# ScreenRGB.net
KiCad netlist of a schematic drawn in Altium Designer
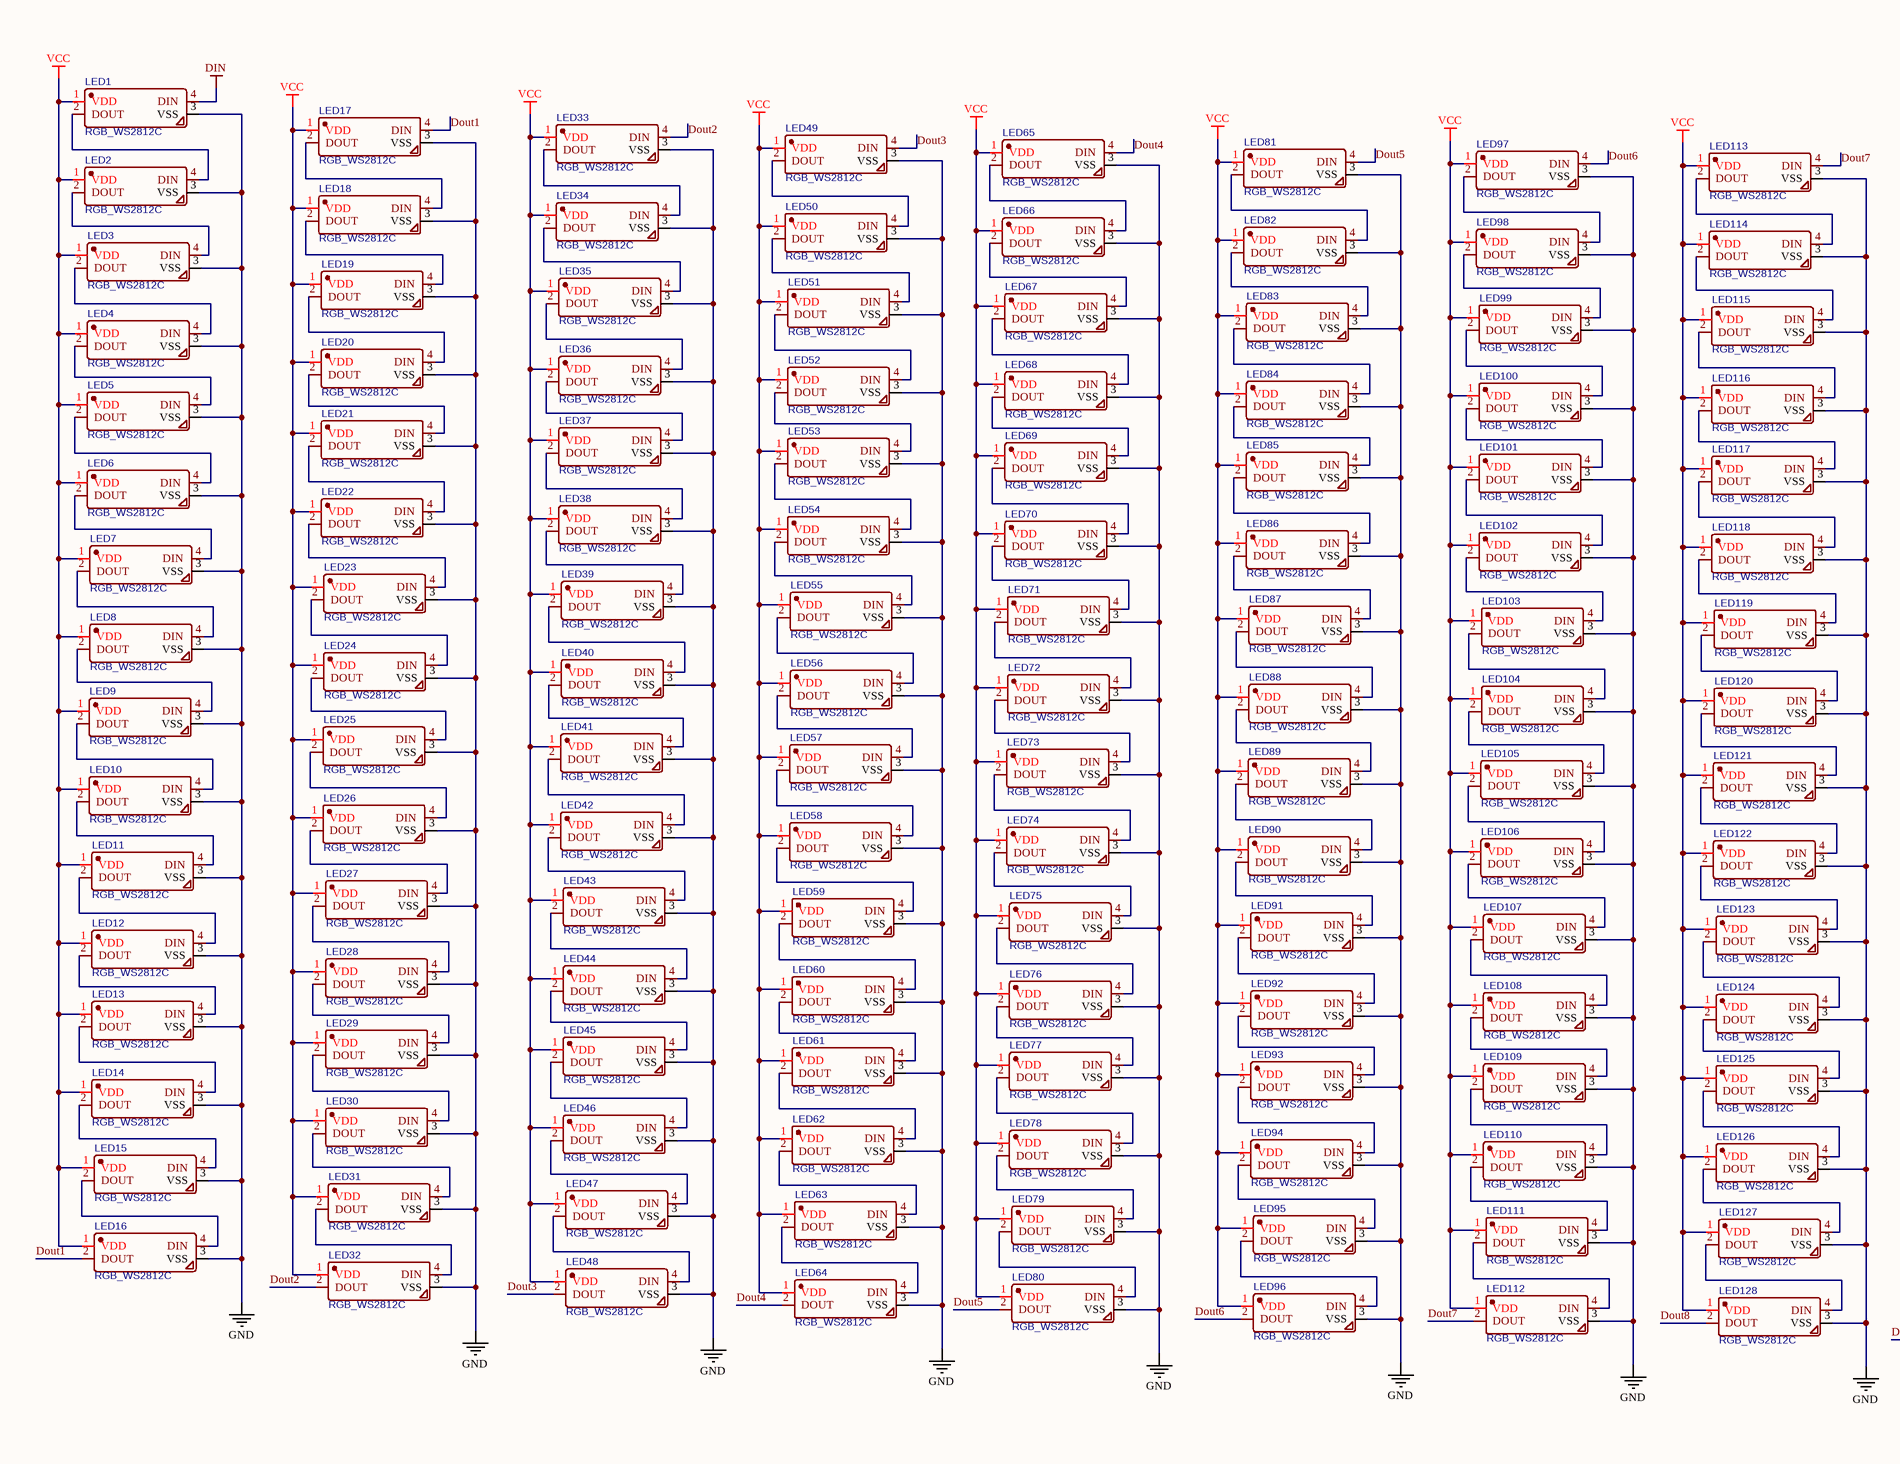
[diagram p0: ScreenRGB.SchDoc, left]
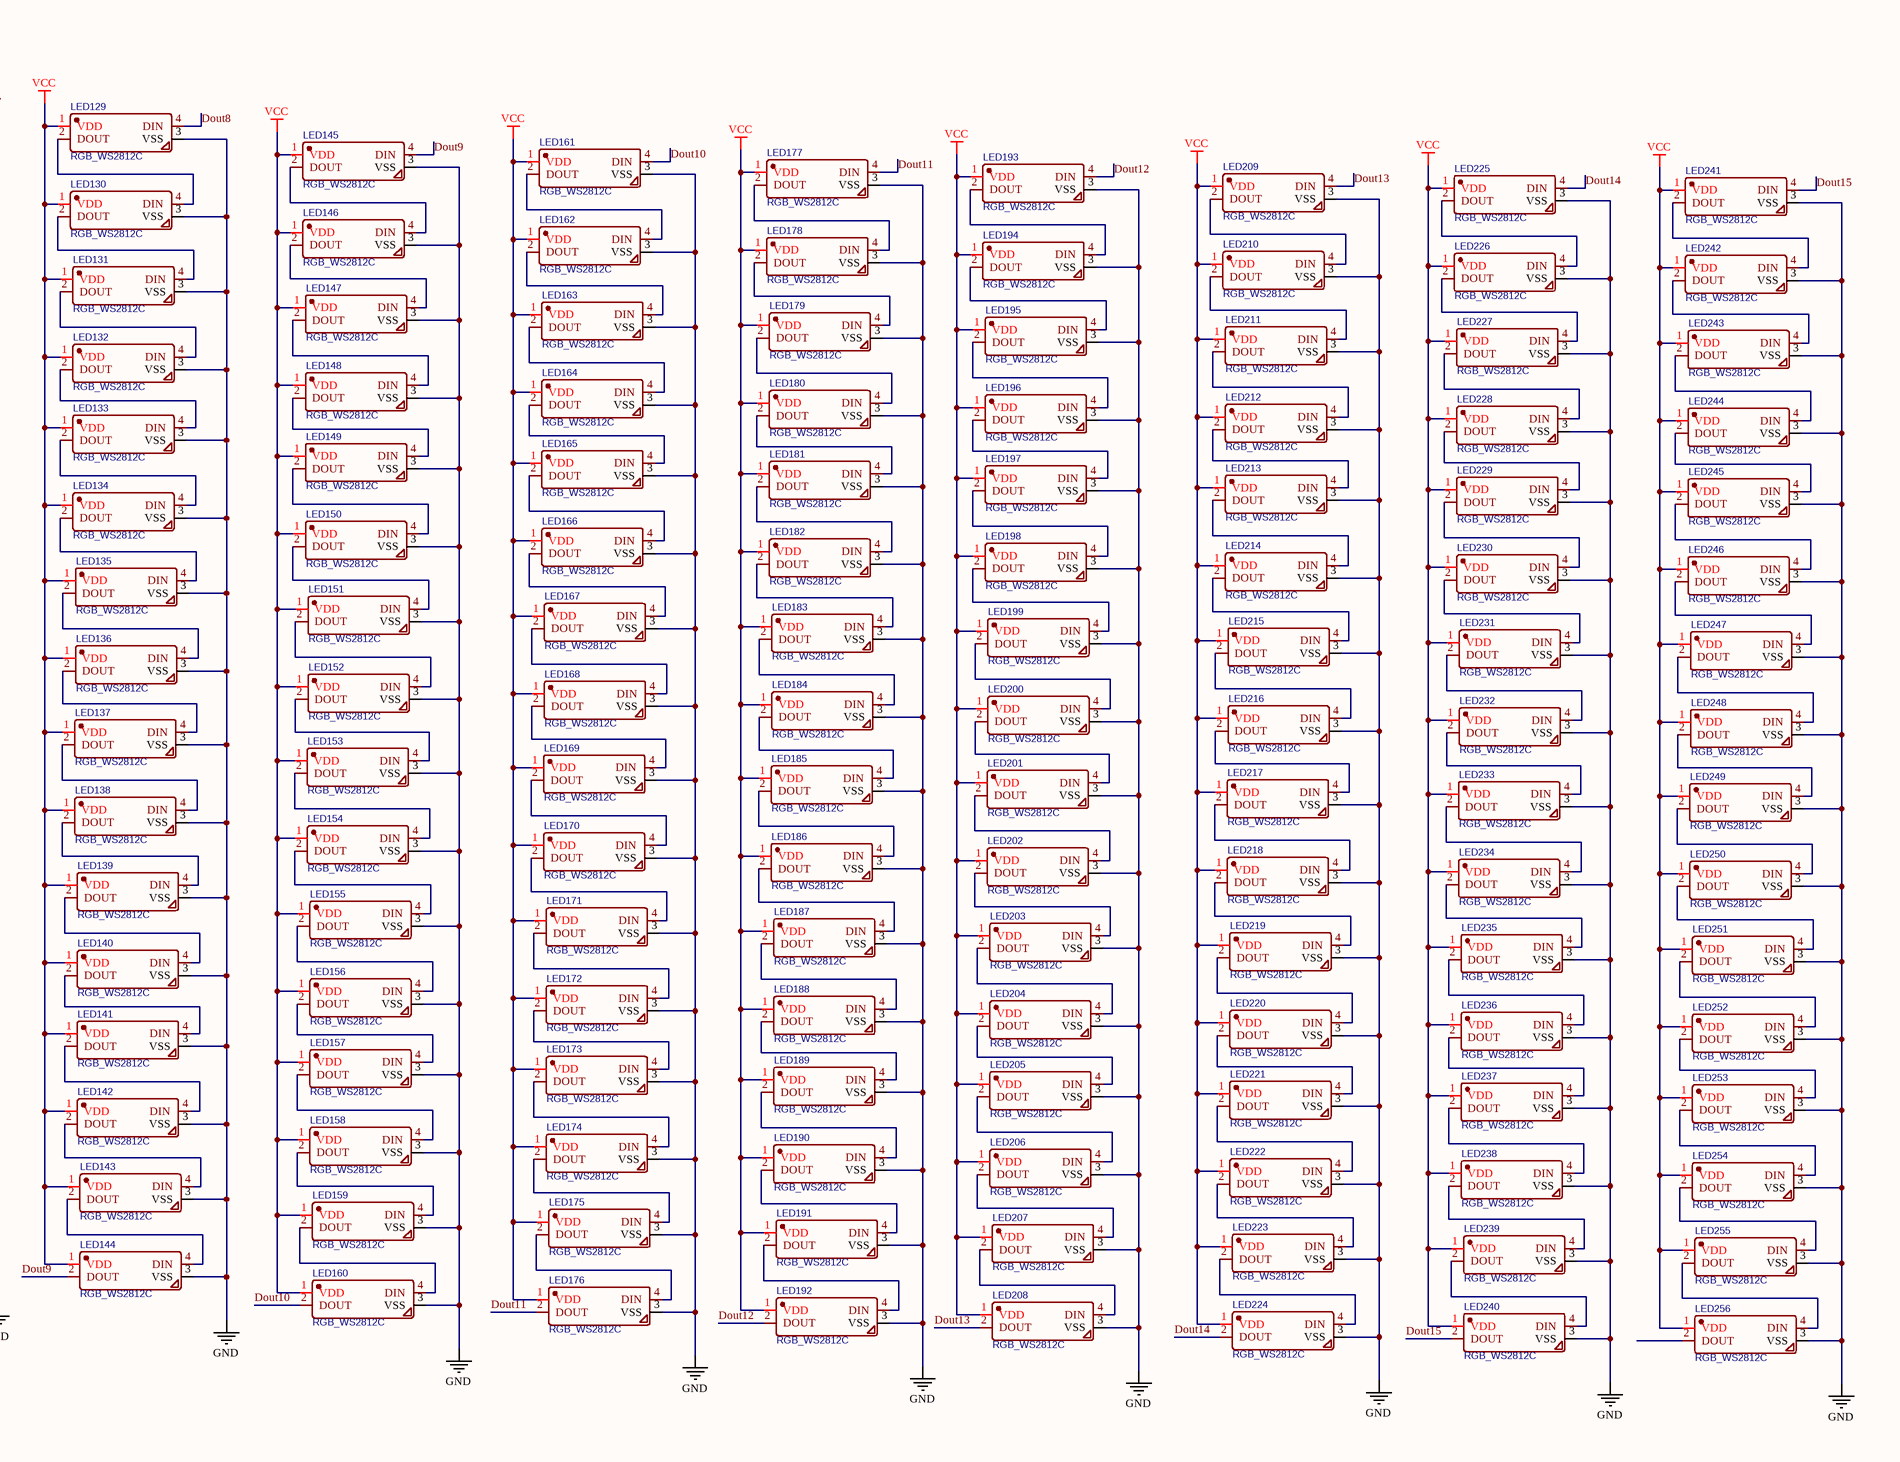
[diagram p1: ScreenRGB.SchDoc, right]

(export (version "E")
  (design (tool "Eeschema 10.0.6"))
  (components
    (comp (ref "LED1")
      (value "RGB_WS2812C")
      (footprint "LED_5050-SMD_4P-WS2812")
      (fields
        (field (name "BOM_MANUFACTURER PART") "WS2812C")
        (field (name "BOM_SUPPLIER PART") "C114587")
        (field (name "CONTRIBUTOR") "LCSC")
      )
      (libsource (lib "LTC_Library1") (part "RGB_WS2812C"))
    )
    (comp (ref "LED2")
      (value "RGB_WS2812C")
      (footprint "LED_5050-SMD_4P-WS2812")
      (fields
        (field (name "BOM_MANUFACTURER PART") "WS2812C")
        (field (name "BOM_SUPPLIER PART") "C114587")
        (field (name "CONTRIBUTOR") "LCSC")
      )
      (libsource (lib "LTC_Library1") (part "RGB_WS2812C"))
    )
    (comp (ref "LED3")
      (value "RGB_WS2812C")
      (footprint "LED_5050-SMD_4P-WS2812")
      (fields
        (field (name "BOM_MANUFACTURER PART") "WS2812C")
        (field (name "BOM_SUPPLIER PART") "C114587")
        (field (name "CONTRIBUTOR") "LCSC")
      )
      (libsource (lib "LTC_Library1") (part "RGB_WS2812C"))
    )
    (comp (ref "LED4")
      (value "RGB_WS2812C")
      (footprint "LED_5050-SMD_4P-WS2812")
      (fields
        (field (name "BOM_MANUFACTURER PART") "WS2812C")
        (field (name "BOM_SUPPLIER PART") "C114587")
        (field (name "CONTRIBUTOR") "LCSC")
      )
      (libsource (lib "LTC_Library1") (part "RGB_WS2812C"))
    )
    (comp (ref "LED5")
      (value "RGB_WS2812C")
      (footprint "LED_5050-SMD_4P-WS2812")
      (fields
        (field (name "BOM_MANUFACTURER PART") "WS2812C")
        (field (name "BOM_SUPPLIER PART") "C114587")
        (field (name "CONTRIBUTOR") "LCSC")
      )
      (libsource (lib "LTC_Library1") (part "RGB_WS2812C"))
    )
    (comp (ref "LED6")
      (value "RGB_WS2812C")
      (footprint "LED_5050-SMD_4P-WS2812")
      (fields
        (field (name "BOM_MANUFACTURER PART") "WS2812C")
        (field (name "BOM_SUPPLIER PART") "C114587")
        (field (name "CONTRIBUTOR") "LCSC")
      )
      (libsource (lib "LTC_Library1") (part "RGB_WS2812C"))
    )
    (comp (ref "LED7")
      (value "RGB_WS2812C")
      (footprint "LED_5050-SMD_4P-WS2812")
      (fields
        (field (name "BOM_MANUFACTURER PART") "WS2812C")
        (field (name "BOM_SUPPLIER PART") "C114587")
        (field (name "CONTRIBUTOR") "LCSC")
      )
      (libsource (lib "LTC_Library1") (part "RGB_WS2812C"))
    )
    (comp (ref "LED8")
      (value "RGB_WS2812C")
      (footprint "LED_5050-SMD_4P-WS2812")
      (fields
        (field (name "BOM_MANUFACTURER PART") "WS2812C")
        (field (name "BOM_SUPPLIER PART") "C114587")
        (field (name "CONTRIBUTOR") "LCSC")
      )
      (libsource (lib "LTC_Library1") (part "RGB_WS2812C"))
    )
    (comp (ref "LED9")
      (value "RGB_WS2812C")
      (footprint "LED_5050-SMD_4P-WS2812")
      (fields
        (field (name "BOM_MANUFACTURER PART") "WS2812C")
        (field (name "BOM_SUPPLIER PART") "C114587")
        (field (name "CONTRIBUTOR") "LCSC")
      )
      (libsource (lib "LTC_Library1") (part "RGB_WS2812C"))
    )
    (comp (ref "LED10")
      (value "RGB_WS2812C")
      (footprint "LED_5050-SMD_4P-WS2812")
      (fields
        (field (name "BOM_MANUFACTURER PART") "WS2812C")
        (field (name "BOM_SUPPLIER PART") "C114587")
        (field (name "CONTRIBUTOR") "LCSC")
      )
      (libsource (lib "LTC_Library1") (part "RGB_WS2812C"))
    )
    (comp (ref "LED11")
      (value "RGB_WS2812C")
      (footprint "LED_5050-SMD_4P-WS2812")
      (fields
        (field (name "BOM_MANUFACTURER PART") "WS2812C")
        (field (name "BOM_SUPPLIER PART") "C114587")
        (field (name "CONTRIBUTOR") "LCSC")
      )
      (libsource (lib "LTC_Library1") (part "RGB_WS2812C"))
    )
    (comp (ref "LED12")
      (value "RGB_WS2812C")
      (footprint "LED_5050-SMD_4P-WS2812")
      (fields
        (field (name "BOM_MANUFACTURER PART") "WS2812C")
        (field (name "BOM_SUPPLIER PART") "C114587")
        (field (name "CONTRIBUTOR") "LCSC")
      )
      (libsource (lib "LTC_Library1") (part "RGB_WS2812C"))
    )
    (comp (ref "LED13")
      (value "RGB_WS2812C")
      (footprint "LED_5050-SMD_4P-WS2812")
      (fields
        (field (name "BOM_MANUFACTURER PART") "WS2812C")
        (field (name "BOM_SUPPLIER PART") "C114587")
        (field (name "CONTRIBUTOR") "LCSC")
      )
      (libsource (lib "LTC_Library1") (part "RGB_WS2812C"))
    )
    (comp (ref "LED14")
      (value "RGB_WS2812C")
      (footprint "LED_5050-SMD_4P-WS2812")
      (fields
        (field (name "BOM_MANUFACTURER PART") "WS2812C")
        (field (name "BOM_SUPPLIER PART") "C114587")
        (field (name "CONTRIBUTOR") "LCSC")
      )
      (libsource (lib "LTC_Library1") (part "RGB_WS2812C"))
    )
    (comp (ref "LED15")
      (value "RGB_WS2812C")
      (footprint "LED_5050-SMD_4P-WS2812")
      (fields
        (field (name "BOM_MANUFACTURER PART") "WS2812C")
        (field (name "BOM_SUPPLIER PART") "C114587")
        (field (name "CONTRIBUTOR") "LCSC")
      )
      (libsource (lib "LTC_Library1") (part "RGB_WS2812C"))
    )
    (comp (ref "LED16")
      (value "RGB_WS2812C")
      (footprint "LED_5050-SMD_4P-WS2812")
      (fields
        (field (name "BOM_MANUFACTURER PART") "WS2812C")
        (field (name "BOM_SUPPLIER PART") "C114587")
        (field (name "CONTRIBUTOR") "LCSC")
      )
      (libsource (lib "LTC_Library1") (part "RGB_WS2812C"))
    )
    (comp (ref "LED17")
      (value "RGB_WS2812C")
      (footprint "LED_5050-SMD_4P-WS2812")
      (fields
        (field (name "BOM_MANUFACTURER PART") "WS2812C")
        (field (name "BOM_SUPPLIER PART") "C114587")
        (field (name "CONTRIBUTOR") "LCSC")
      )
      (libsource (lib "LTC_Library1") (part "RGB_WS2812C"))
    )
    (comp (ref "LED18")
      (value "RGB_WS2812C")
      (footprint "LED_5050-SMD_4P-WS2812")
      (fields
        (field (name "BOM_MANUFACTURER PART") "WS2812C")
        (field (name "BOM_SUPPLIER PART") "C114587")
        (field (name "CONTRIBUTOR") "LCSC")
      )
      (libsource (lib "LTC_Library1") (part "RGB_WS2812C"))
    )
    (comp (ref "LED19")
      (value "RGB_WS2812C")
      (footprint "LED_5050-SMD_4P-WS2812")
      (fields
        (field (name "BOM_MANUFACTURER PART") "WS2812C")
        (field (name "BOM_SUPPLIER PART") "C114587")
        (field (name "CONTRIBUTOR") "LCSC")
      )
      (libsource (lib "LTC_Library1") (part "RGB_WS2812C"))
    )
    (comp (ref "LED20")
      (value "RGB_WS2812C")
      (footprint "LED_5050-SMD_4P-WS2812")
      (fields
        (field (name "BOM_MANUFACTURER PART") "WS2812C")
        (field (name "BOM_SUPPLIER PART") "C114587")
        (field (name "CONTRIBUTOR") "LCSC")
      )
      (libsource (lib "LTC_Library1") (part "RGB_WS2812C"))
    )
    (comp (ref "LED21")
      (value "RGB_WS2812C")
      (footprint "LED_5050-SMD_4P-WS2812")
      (fields
        (field (name "BOM_MANUFACTURER PART") "WS2812C")
        (field (name "BOM_SUPPLIER PART") "C114587")
        (field (name "CONTRIBUTOR") "LCSC")
      )
      (libsource (lib "LTC_Library1") (part "RGB_WS2812C"))
    )
    (comp (ref "LED22")
      (value "RGB_WS2812C")
      (footprint "LED_5050-SMD_4P-WS2812")
      (fields
        (field (name "BOM_MANUFACTURER PART") "WS2812C")
        (field (name "BOM_SUPPLIER PART") "C114587")
        (field (name "CONTRIBUTOR") "LCSC")
      )
      (libsource (lib "LTC_Library1") (part "RGB_WS2812C"))
    )
    (comp (ref "LED23")
      (value "RGB_WS2812C")
      (footprint "LED_5050-SMD_4P-WS2812")
      (fields
        (field (name "BOM_MANUFACTURER PART") "WS2812C")
        (field (name "BOM_SUPPLIER PART") "C114587")
        (field (name "CONTRIBUTOR") "LCSC")
      )
      (libsource (lib "LTC_Library1") (part "RGB_WS2812C"))
    )
    (comp (ref "LED24")
      (value "RGB_WS2812C")
      (footprint "LED_5050-SMD_4P-WS2812")
      (fields
        (field (name "BOM_MANUFACTURER PART") "WS2812C")
        (field (name "BOM_SUPPLIER PART") "C114587")
        (field (name "CONTRIBUTOR") "LCSC")
      )
      (libsource (lib "LTC_Library1") (part "RGB_WS2812C"))
    )
    (comp (ref "LED25")
      (value "RGB_WS2812C")
      (footprint "LED_5050-SMD_4P-WS2812")
      (fields
        (field (name "BOM_MANUFACTURER PART") "WS2812C")
        (field (name "BOM_SUPPLIER PART") "C114587")
        (field (name "CONTRIBUTOR") "LCSC")
      )
      (libsource (lib "LTC_Library1") (part "RGB_WS2812C"))
    )
    (comp (ref "LED26")
      (value "RGB_WS2812C")
      (footprint "LED_5050-SMD_4P-WS2812")
      (fields
        (field (name "BOM_MANUFACTURER PART") "WS2812C")
        (field (name "BOM_SUPPLIER PART") "C114587")
        (field (name "CONTRIBUTOR") "LCSC")
      )
      (libsource (lib "LTC_Library1") (part "RGB_WS2812C"))
    )
    (comp (ref "LED27")
      (value "RGB_WS2812C")
      (footprint "LED_5050-SMD_4P-WS2812")
      (fields
        (field (name "BOM_MANUFACTURER PART") "WS2812C")
        (field (name "BOM_SUPPLIER PART") "C114587")
        (field (name "CONTRIBUTOR") "LCSC")
      )
      (libsource (lib "LTC_Library1") (part "RGB_WS2812C"))
    )
    (comp (ref "LED28")
      (value "RGB_WS2812C")
      (footprint "LED_5050-SMD_4P-WS2812")
      (fields
        (field (name "BOM_MANUFACTURER PART") "WS2812C")
        (field (name "BOM_SUPPLIER PART") "C114587")
        (field (name "CONTRIBUTOR") "LCSC")
      )
      (libsource (lib "LTC_Library1") (part "RGB_WS2812C"))
    )
    (comp (ref "LED29")
      (value "RGB_WS2812C")
      (footprint "LED_5050-SMD_4P-WS2812")
      (fields
        (field (name "BOM_MANUFACTURER PART") "WS2812C")
        (field (name "BOM_SUPPLIER PART") "C114587")
        (field (name "CONTRIBUTOR") "LCSC")
      )
      (libsource (lib "LTC_Library1") (part "RGB_WS2812C"))
    )
    (comp (ref "LED30")
      (value "RGB_WS2812C")
      (footprint "LED_5050-SMD_4P-WS2812")
      (fields
        (field (name "BOM_MANUFACTURER PART") "WS2812C")
        (field (name "BOM_SUPPLIER PART") "C114587")
        (field (name "CONTRIBUTOR") "LCSC")
      )
      (libsource (lib "LTC_Library1") (part "RGB_WS2812C"))
    )
    (comp (ref "LED31")
      (value "RGB_WS2812C")
      (footprint "LED_5050-SMD_4P-WS2812")
      (fields
        (field (name "BOM_MANUFACTURER PART") "WS2812C")
        (field (name "BOM_SUPPLIER PART") "C114587")
        (field (name "CONTRIBUTOR") "LCSC")
      )
      (libsource (lib "LTC_Library1") (part "RGB_WS2812C"))
    )
    (comp (ref "LED32")
      (value "RGB_WS2812C")
      (footprint "LED_5050-SMD_4P-WS2812")
      (fields
        (field (name "BOM_MANUFACTURER PART") "WS2812C")
        (field (name "BOM_SUPPLIER PART") "C114587")
        (field (name "CONTRIBUTOR") "LCSC")
      )
      (libsource (lib "LTC_Library1") (part "RGB_WS2812C"))
    )
    (comp (ref "LED33")
      (value "RGB_WS2812C")
      (footprint "LED_5050-SMD_4P-WS2812")
      (fields
        (field (name "BOM_MANUFACTURER PART") "WS2812C")
        (field (name "BOM_SUPPLIER PART") "C114587")
        (field (name "CONTRIBUTOR") "LCSC")
      )
      (libsource (lib "LTC_Library1") (part "RGB_WS2812C"))
    )
    (comp (ref "LED34")
      (value "RGB_WS2812C")
      (footprint "LED_5050-SMD_4P-WS2812")
      (fields
        (field (name "BOM_MANUFACTURER PART") "WS2812C")
        (field (name "BOM_SUPPLIER PART") "C114587")
        (field (name "CONTRIBUTOR") "LCSC")
      )
      (libsource (lib "LTC_Library1") (part "RGB_WS2812C"))
    )
    (comp (ref "LED35")
      (value "RGB_WS2812C")
      (footprint "LED_5050-SMD_4P-WS2812")
      (fields
        (field (name "BOM_MANUFACTURER PART") "WS2812C")
        (field (name "BOM_SUPPLIER PART") "C114587")
        (field (name "CONTRIBUTOR") "LCSC")
      )
      (libsource (lib "LTC_Library1") (part "RGB_WS2812C"))
    )
    (comp (ref "LED36")
      (value "RGB_WS2812C")
      (footprint "LED_5050-SMD_4P-WS2812")
      (fields
        (field (name "BOM_MANUFACTURER PART") "WS2812C")
        (field (name "BOM_SUPPLIER PART") "C114587")
        (field (name "CONTRIBUTOR") "LCSC")
      )
      (libsource (lib "LTC_Library1") (part "RGB_WS2812C"))
    )
    (comp (ref "LED37")
      (value "RGB_WS2812C")
      (footprint "LED_5050-SMD_4P-WS2812")
      (fields
        (field (name "BOM_MANUFACTURER PART") "WS2812C")
        (field (name "BOM_SUPPLIER PART") "C114587")
        (field (name "CONTRIBUTOR") "LCSC")
      )
      (libsource (lib "LTC_Library1") (part "RGB_WS2812C"))
    )
    (comp (ref "LED38")
      (value "RGB_WS2812C")
      (footprint "LED_5050-SMD_4P-WS2812")
      (fields
        (field (name "BOM_MANUFACTURER PART") "WS2812C")
        (field (name "BOM_SUPPLIER PART") "C114587")
        (field (name "CONTRIBUTOR") "LCSC")
      )
      (libsource (lib "LTC_Library1") (part "RGB_WS2812C"))
    )
    (comp (ref "LED39")
      (value "RGB_WS2812C")
      (footprint "LED_5050-SMD_4P-WS2812")
      (fields
        (field (name "BOM_MANUFACTURER PART") "WS2812C")
        (field (name "BOM_SUPPLIER PART") "C114587")
        (field (name "CONTRIBUTOR") "LCSC")
      )
      (libsource (lib "LTC_Library1") (part "RGB_WS2812C"))
    )
    (comp (ref "LED40")
      (value "RGB_WS2812C")
      (footprint "LED_5050-SMD_4P-WS2812")
      (fields
        (field (name "BOM_MANUFACTURER PART") "WS2812C")
        (field (name "BOM_SUPPLIER PART") "C114587")
        (field (name "CONTRIBUTOR") "LCSC")
      )
      (libsource (lib "LTC_Library1") (part "RGB_WS2812C"))
    )
    (comp (ref "LED41")
      (value "RGB_WS2812C")
      (footprint "LED_5050-SMD_4P-WS2812")
      (fields
        (field (name "BOM_MANUFACTURER PART") "WS2812C")
        (field (name "BOM_SUPPLIER PART") "C114587")
        (field (name "CONTRIBUTOR") "LCSC")
      )
      (libsource (lib "LTC_Library1") (part "RGB_WS2812C"))
    )
    (comp (ref "LED42")
      (value "RGB_WS2812C")
      (footprint "LED_5050-SMD_4P-WS2812")
      (fields
        (field (name "BOM_MANUFACTURER PART") "WS2812C")
        (field (name "BOM_SUPPLIER PART") "C114587")
        (field (name "CONTRIBUTOR") "LCSC")
      )
      (libsource (lib "LTC_Library1") (part "RGB_WS2812C"))
    )
    (comp (ref "LED43")
      (value "RGB_WS2812C")
      (footprint "LED_5050-SMD_4P-WS2812")
      (fields
        (field (name "BOM_MANUFACTURER PART") "WS2812C")
        (field (name "BOM_SUPPLIER PART") "C114587")
        (field (name "CONTRIBUTOR") "LCSC")
      )
      (libsource (lib "LTC_Library1") (part "RGB_WS2812C"))
    )
    (comp (ref "LED44")
      (value "RGB_WS2812C")
      (footprint "LED_5050-SMD_4P-WS2812")
      (fields
        (field (name "BOM_MANUFACTURER PART") "WS2812C")
        (field (name "BOM_SUPPLIER PART") "C114587")
        (field (name "CONTRIBUTOR") "LCSC")
      )
      (libsource (lib "LTC_Library1") (part "RGB_WS2812C"))
    )
    (comp (ref "LED45")
      (value "RGB_WS2812C")
      (footprint "LED_5050-SMD_4P-WS2812")
      (fields
        (field (name "BOM_MANUFACTURER PART") "WS2812C")
        (field (name "BOM_SUPPLIER PART") "C114587")
        (field (name "CONTRIBUTOR") "LCSC")
      )
      (libsource (lib "LTC_Library1") (part "RGB_WS2812C"))
    )
    (comp (ref "LED46")
      (value "RGB_WS2812C")
      (footprint "LED_5050-SMD_4P-WS2812")
      (fields
        (field (name "BOM_MANUFACTURER PART") "WS2812C")
        (field (name "BOM_SUPPLIER PART") "C114587")
        (field (name "CONTRIBUTOR") "LCSC")
      )
      (libsource (lib "LTC_Library1") (part "RGB_WS2812C"))
    )
    (comp (ref "LED47")
      (value "RGB_WS2812C")
      (footprint "LED_5050-SMD_4P-WS2812")
      (fields
        (field (name "BOM_MANUFACTURER PART") "WS2812C")
        (field (name "BOM_SUPPLIER PART") "C114587")
        (field (name "CONTRIBUTOR") "LCSC")
      )
      (libsource (lib "LTC_Library1") (part "RGB_WS2812C"))
    )
    (comp (ref "LED48")
      (value "RGB_WS2812C")
      (footprint "LED_5050-SMD_4P-WS2812")
      (fields
        (field (name "BOM_MANUFACTURER PART") "WS2812C")
        (field (name "BOM_SUPPLIER PART") "C114587")
        (field (name "CONTRIBUTOR") "LCSC")
      )
      (libsource (lib "LTC_Library1") (part "RGB_WS2812C"))
    )
    (comp (ref "LED49")
      (value "RGB_WS2812C")
      (footprint "LED_5050-SMD_4P-WS2812")
      (fields
        (field (name "BOM_MANUFACTURER PART") "WS2812C")
        (field (name "BOM_SUPPLIER PART") "C114587")
        (field (name "CONTRIBUTOR") "LCSC")
      )
      (libsource (lib "LTC_Library1") (part "RGB_WS2812C"))
    )
    (comp (ref "LED50")
      (value "RGB_WS2812C")
      (footprint "LED_5050-SMD_4P-WS2812")
      (fields
        (field (name "BOM_MANUFACTURER PART") "WS2812C")
        (field (name "BOM_SUPPLIER PART") "C114587")
        (field (name "CONTRIBUTOR") "LCSC")
      )
      (libsource (lib "LTC_Library1") (part "RGB_WS2812C"))
    )
    (comp (ref "LED51")
      (value "RGB_WS2812C")
      (footprint "LED_5050-SMD_4P-WS2812")
      (fields
        (field (name "BOM_MANUFACTURER PART") "WS2812C")
        (field (name "BOM_SUPPLIER PART") "C114587")
        (field (name "CONTRIBUTOR") "LCSC")
      )
      (libsource (lib "LTC_Library1") (part "RGB_WS2812C"))
    )
    (comp (ref "LED52")
      (value "RGB_WS2812C")
      (footprint "LED_5050-SMD_4P-WS2812")
      (fields
        (field (name "BOM_MANUFACTURER PART") "WS2812C")
        (field (name "BOM_SUPPLIER PART") "C114587")
        (field (name "CONTRIBUTOR") "LCSC")
      )
      (libsource (lib "LTC_Library1") (part "RGB_WS2812C"))
    )
    (comp (ref "LED53")
      (value "RGB_WS2812C")
      (footprint "LED_5050-SMD_4P-WS2812")
      (fields
        (field (name "BOM_MANUFACTURER PART") "WS2812C")
        (field (name "BOM_SUPPLIER PART") "C114587")
        (field (name "CONTRIBUTOR") "LCSC")
      )
      (libsource (lib "LTC_Library1") (part "RGB_WS2812C"))
    )
    (comp (ref "LED54")
      (value "RGB_WS2812C")
      (footprint "LED_5050-SMD_4P-WS2812")
      (fields
        (field (name "BOM_MANUFACTURER PART") "WS2812C")
        (field (name "BOM_SUPPLIER PART") "C114587")
        (field (name "CONTRIBUTOR") "LCSC")
      )
      (libsource (lib "LTC_Library1") (part "RGB_WS2812C"))
    )
    (comp (ref "LED55")
      (value "RGB_WS2812C")
      (footprint "LED_5050-SMD_4P-WS2812")
      (fields
        (field (name "BOM_MANUFACTURER PART") "WS2812C")
        (field (name "BOM_SUPPLIER PART") "C114587")
        (field (name "CONTRIBUTOR") "LCSC")
      )
      (libsource (lib "LTC_Library1") (part "RGB_WS2812C"))
    )
    (comp (ref "LED56")
      (value "RGB_WS2812C")
      (footprint "LED_5050-SMD_4P-WS2812")
      (fields
        (field (name "BOM_MANUFACTURER PART") "WS2812C")
        (field (name "BOM_SUPPLIER PART") "C114587")
        (field (name "CONTRIBUTOR") "LCSC")
      )
      (libsource (lib "LTC_Library1") (part "RGB_WS2812C"))
    )
    (comp (ref "LED57")
      (value "RGB_WS2812C")
      (footprint "LED_5050-SMD_4P-WS2812")
      (fields
        (field (name "BOM_MANUFACTURER PART") "WS2812C")
        (field (name "BOM_SUPPLIER PART") "C114587")
        (field (name "CONTRIBUTOR") "LCSC")
      )
      (libsource (lib "LTC_Library1") (part "RGB_WS2812C"))
    )
    (comp (ref "LED58")
      (value "RGB_WS2812C")
      (footprint "LED_5050-SMD_4P-WS2812")
      (fields
        (field (name "BOM_MANUFACTURER PART") "WS2812C")
        (field (name "BOM_SUPPLIER PART") "C114587")
        (field (name "CONTRIBUTOR") "LCSC")
      )
      (libsource (lib "LTC_Library1") (part "RGB_WS2812C"))
    )
    (comp (ref "LED59")
      (value "RGB_WS2812C")
      (footprint "LED_5050-SMD_4P-WS2812")
      (fields
        (field (name "BOM_MANUFACTURER PART") "WS2812C")
        (field (name "BOM_SUPPLIER PART") "C114587")
        (field (name "CONTRIBUTOR") "LCSC")
      )
      (libsource (lib "LTC_Library1") (part "RGB_WS2812C"))
    )
    (comp (ref "LED60")
      (value "RGB_WS2812C")
      (footprint "LED_5050-SMD_4P-WS2812")
      (fields
        (field (name "BOM_MANUFACTURER PART") "WS2812C")
        (field (name "BOM_SUPPLIER PART") "C114587")
        (field (name "CONTRIBUTOR") "LCSC")
      )
      (libsource (lib "LTC_Library1") (part "RGB_WS2812C"))
    )
    (comp (ref "LED61")
      (value "RGB_WS2812C")
      (footprint "LED_5050-SMD_4P-WS2812")
      (fields
        (field (name "BOM_MANUFACTURER PART") "WS2812C")
        (field (name "BOM_SUPPLIER PART") "C114587")
        (field (name "CONTRIBUTOR") "LCSC")
      )
      (libsource (lib "LTC_Library1") (part "RGB_WS2812C"))
    )
    (comp (ref "LED62")
      (value "RGB_WS2812C")
      (footprint "LED_5050-SMD_4P-WS2812")
      (fields
        (field (name "BOM_MANUFACTURER PART") "WS2812C")
        (field (name "BOM_SUPPLIER PART") "C114587")
        (field (name "CONTRIBUTOR") "LCSC")
      )
      (libsource (lib "LTC_Library1") (part "RGB_WS2812C"))
    )
    (comp (ref "LED63")
      (value "RGB_WS2812C")
      (footprint "LED_5050-SMD_4P-WS2812")
      (fields
        (field (name "BOM_MANUFACTURER PART") "WS2812C")
        (field (name "BOM_SUPPLIER PART") "C114587")
        (field (name "CONTRIBUTOR") "LCSC")
      )
      (libsource (lib "LTC_Library1") (part "RGB_WS2812C"))
    )
    (comp (ref "LED64")
      (value "RGB_WS2812C")
      (footprint "LED_5050-SMD_4P-WS2812")
      (fields
        (field (name "BOM_MANUFACTURER PART") "WS2812C")
        (field (name "BOM_SUPPLIER PART") "C114587")
        (field (name "CONTRIBUTOR") "LCSC")
      )
      (libsource (lib "LTC_Library1") (part "RGB_WS2812C"))
    )
    (comp (ref "LED65")
      (value "RGB_WS2812C")
      (footprint "LED_5050-SMD_4P-WS2812")
      (fields
        (field (name "BOM_MANUFACTURER PART") "WS2812C")
        (field (name "BOM_SUPPLIER PART") "C114587")
        (field (name "CONTRIBUTOR") "LCSC")
      )
      (libsource (lib "LTC_Library1") (part "RGB_WS2812C"))
    )
    (comp (ref "LED66")
      (value "RGB_WS2812C")
      (footprint "LED_5050-SMD_4P-WS2812")
      (fields
        (field (name "BOM_MANUFACTURER PART") "WS2812C")
        (field (name "BOM_SUPPLIER PART") "C114587")
        (field (name "CONTRIBUTOR") "LCSC")
      )
      (libsource (lib "LTC_Library1") (part "RGB_WS2812C"))
    )
    (comp (ref "LED67")
      (value "RGB_WS2812C")
      (footprint "LED_5050-SMD_4P-WS2812")
      (fields
        (field (name "BOM_MANUFACTURER PART") "WS2812C")
        (field (name "BOM_SUPPLIER PART") "C114587")
        (field (name "CONTRIBUTOR") "LCSC")
      )
      (libsource (lib "LTC_Library1") (part "RGB_WS2812C"))
    )
    (comp (ref "LED68")
      (value "RGB_WS2812C")
      (footprint "LED_5050-SMD_4P-WS2812")
      (fields
        (field (name "BOM_MANUFACTURER PART") "WS2812C")
        (field (name "BOM_SUPPLIER PART") "C114587")
        (field (name "CONTRIBUTOR") "LCSC")
      )
      (libsource (lib "LTC_Library1") (part "RGB_WS2812C"))
    )
    (comp (ref "LED69")
      (value "RGB_WS2812C")
      (footprint "LED_5050-SMD_4P-WS2812")
      (fields
        (field (name "BOM_MANUFACTURER PART") "WS2812C")
        (field (name "BOM_SUPPLIER PART") "C114587")
        (field (name "CONTRIBUTOR") "LCSC")
      )
      (libsource (lib "LTC_Library1") (part "RGB_WS2812C"))
    )
    (comp (ref "LED70")
      (value "RGB_WS2812C")
      (footprint "LED_5050-SMD_4P-WS2812")
      (fields
        (field (name "BOM_MANUFACTURER PART") "WS2812C")
        (field (name "BOM_SUPPLIER PART") "C114587")
        (field (name "CONTRIBUTOR") "LCSC")
      )
      (libsource (lib "LTC_Library1") (part "RGB_WS2812C"))
    )
    (comp (ref "LED71")
      (value "RGB_WS2812C")
      (footprint "LED_5050-SMD_4P-WS2812")
      (fields
        (field (name "BOM_MANUFACTURER PART") "WS2812C")
        (field (name "BOM_SUPPLIER PART") "C114587")
        (field (name "CONTRIBUTOR") "LCSC")
      )
      (libsource (lib "LTC_Library1") (part "RGB_WS2812C"))
    )
    (comp (ref "LED72")
      (value "RGB_WS2812C")
      (footprint "LED_5050-SMD_4P-WS2812")
      (fields
        (field (name "BOM_MANUFACTURER PART") "WS2812C")
        (field (name "BOM_SUPPLIER PART") "C114587")
        (field (name "CONTRIBUTOR") "LCSC")
      )
      (libsource (lib "LTC_Library1") (part "RGB_WS2812C"))
    )
    (comp (ref "LED73")
      (value "RGB_WS2812C")
      (footprint "LED_5050-SMD_4P-WS2812")
      (fields
        (field (name "BOM_MANUFACTURER PART") "WS2812C")
        (field (name "BOM_SUPPLIER PART") "C114587")
        (field (name "CONTRIBUTOR") "LCSC")
      )
      (libsource (lib "LTC_Library1") (part "RGB_WS2812C"))
    )
    (comp (ref "LED74")
      (value "RGB_WS2812C")
      (footprint "LED_5050-SMD_4P-WS2812")
      (fields
        (field (name "BOM_MANUFACTURER PART") "WS2812C")
        (field (name "BOM_SUPPLIER PART") "C114587")
        (field (name "CONTRIBUTOR") "LCSC")
      )
      (libsource (lib "LTC_Library1") (part "RGB_WS2812C"))
    )
    (comp (ref "LED75")
      (value "RGB_WS2812C")
      (footprint "LED_5050-SMD_4P-WS2812")
      (fields
        (field (name "BOM_MANUFACTURER PART") "WS2812C")
        (field (name "BOM_SUPPLIER PART") "C114587")
        (field (name "CONTRIBUTOR") "LCSC")
      )
      (libsource (lib "LTC_Library1") (part "RGB_WS2812C"))
    )
    (comp (ref "LED76")
      (value "RGB_WS2812C")
      (footprint "LED_5050-SMD_4P-WS2812")
      (fields
        (field (name "BOM_MANUFACTURER PART") "WS2812C")
        (field (name "BOM_SUPPLIER PART") "C114587")
        (field (name "CONTRIBUTOR") "LCSC")
      )
      (libsource (lib "LTC_Library1") (part "RGB_WS2812C"))
    )
    (comp (ref "LED77")
      (value "RGB_WS2812C")
      (footprint "LED_5050-SMD_4P-WS2812")
      (fields
        (field (name "BOM_MANUFACTURER PART") "WS2812C")
        (field (name "BOM_SUPPLIER PART") "C114587")
        (field (name "CONTRIBUTOR") "LCSC")
      )
      (libsource (lib "LTC_Library1") (part "RGB_WS2812C"))
    )
    (comp (ref "LED78")
      (value "RGB_WS2812C")
      (footprint "LED_5050-SMD_4P-WS2812")
      (fields
        (field (name "BOM_MANUFACTURER PART") "WS2812C")
        (field (name "BOM_SUPPLIER PART") "C114587")
        (field (name "CONTRIBUTOR") "LCSC")
      )
      (libsource (lib "LTC_Library1") (part "RGB_WS2812C"))
    )
    (comp (ref "LED79")
      (value "RGB_WS2812C")
      (footprint "LED_5050-SMD_4P-WS2812")
      (fields
        (field (name "BOM_MANUFACTURER PART") "WS2812C")
        (field (name "BOM_SUPPLIER PART") "C114587")
        (field (name "CONTRIBUTOR") "LCSC")
      )
      (libsource (lib "LTC_Library1") (part "RGB_WS2812C"))
    )
    (comp (ref "LED80")
      (value "RGB_WS2812C")
      (footprint "LED_5050-SMD_4P-WS2812")
      (fields
        (field (name "BOM_MANUFACTURER PART") "WS2812C")
        (field (name "BOM_SUPPLIER PART") "C114587")
        (field (name "CONTRIBUTOR") "LCSC")
      )
      (libsource (lib "LTC_Library1") (part "RGB_WS2812C"))
    )
    (comp (ref "LED81")
      (value "RGB_WS2812C")
      (footprint "LED_5050-SMD_4P-WS2812")
      (fields
        (field (name "BOM_MANUFACTURER PART") "WS2812C")
        (field (name "BOM_SUPPLIER PART") "C114587")
        (field (name "CONTRIBUTOR") "LCSC")
      )
      (libsource (lib "LTC_Library1") (part "RGB_WS2812C"))
    )
    (comp (ref "LED82")
      (value "RGB_WS2812C")
      (footprint "LED_5050-SMD_4P-WS2812")
      (fields
        (field (name "BOM_MANUFACTURER PART") "WS2812C")
        (field (name "BOM_SUPPLIER PART") "C114587")
        (field (name "CONTRIBUTOR") "LCSC")
      )
      (libsource (lib "LTC_Library1") (part "RGB_WS2812C"))
    )
    (comp (ref "LED83")
      (value "RGB_WS2812C")
      (footprint "LED_5050-SMD_4P-WS2812")
      (fields
        (field (name "BOM_MANUFACTURER PART") "WS2812C")
        (field (name "BOM_SUPPLIER PART") "C114587")
        (field (name "CONTRIBUTOR") "LCSC")
      )
      (libsource (lib "LTC_Library1") (part "RGB_WS2812C"))
    )
    (comp (ref "LED84")
      (value "RGB_WS2812C")
      (footprint "LED_5050-SMD_4P-WS2812")
      (fields
        (field (name "BOM_MANUFACTURER PART") "WS2812C")
        (field (name "BOM_SUPPLIER PART") "C114587")
        (field (name "CONTRIBUTOR") "LCSC")
      )
      (libsource (lib "LTC_Library1") (part "RGB_WS2812C"))
    )
    (comp (ref "LED85")
      (value "RGB_WS2812C")
      (footprint "LED_5050-SMD_4P-WS2812")
      (fields
        (field (name "BOM_MANUFACTURER PART") "WS2812C")
        (field (name "BOM_SUPPLIER PART") "C114587")
        (field (name "CONTRIBUTOR") "LCSC")
      )
      (libsource (lib "LTC_Library1") (part "RGB_WS2812C"))
    )
    (comp (ref "LED86")
      (value "RGB_WS2812C")
      (footprint "LED_5050-SMD_4P-WS2812")
      (fields
        (field (name "BOM_MANUFACTURER PART") "WS2812C")
        (field (name "BOM_SUPPLIER PART") "C114587")
        (field (name "CONTRIBUTOR") "LCSC")
      )
      (libsource (lib "LTC_Library1") (part "RGB_WS2812C"))
    )
    (comp (ref "LED87")
      (value "RGB_WS2812C")
      (footprint "LED_5050-SMD_4P-WS2812")
      (fields
        (field (name "BOM_MANUFACTURER PART") "WS2812C")
        (field (name "BOM_SUPPLIER PART") "C114587")
        (field (name "CONTRIBUTOR") "LCSC")
      )
      (libsource (lib "LTC_Library1") (part "RGB_WS2812C"))
    )
    (comp (ref "LED88")
      (value "RGB_WS2812C")
      (footprint "LED_5050-SMD_4P-WS2812")
      (fields
        (field (name "BOM_MANUFACTURER PART") "WS2812C")
        (field (name "BOM_SUPPLIER PART") "C114587")
        (field (name "CONTRIBUTOR") "LCSC")
      )
      (libsource (lib "LTC_Library1") (part "RGB_WS2812C"))
    )
    (comp (ref "LED89")
      (value "RGB_WS2812C")
      (footprint "LED_5050-SMD_4P-WS2812")
      (fields
        (field (name "BOM_MANUFACTURER PART") "WS2812C")
        (field (name "BOM_SUPPLIER PART") "C114587")
        (field (name "CONTRIBUTOR") "LCSC")
      )
      (libsource (lib "LTC_Library1") (part "RGB_WS2812C"))
    )
    (comp (ref "LED90")
      (value "RGB_WS2812C")
      (footprint "LED_5050-SMD_4P-WS2812")
      (fields
        (field (name "BOM_MANUFACTURER PART") "WS2812C")
        (field (name "BOM_SUPPLIER PART") "C114587")
        (field (name "CONTRIBUTOR") "LCSC")
      )
      (libsource (lib "LTC_Library1") (part "RGB_WS2812C"))
    )
    (comp (ref "LED91")
      (value "RGB_WS2812C")
      (footprint "LED_5050-SMD_4P-WS2812")
      (fields
        (field (name "BOM_MANUFACTURER PART") "WS2812C")
        (field (name "BOM_SUPPLIER PART") "C114587")
        (field (name "CONTRIBUTOR") "LCSC")
      )
      (libsource (lib "LTC_Library1") (part "RGB_WS2812C"))
    )
    (comp (ref "LED92")
      (value "RGB_WS2812C")
      (footprint "LED_5050-SMD_4P-WS2812")
      (fields
        (field (name "BOM_MANUFACTURER PART") "WS2812C")
        (field (name "BOM_SUPPLIER PART") "C114587")
        (field (name "CONTRIBUTOR") "LCSC")
      )
      (libsource (lib "LTC_Library1") (part "RGB_WS2812C"))
    )
    (comp (ref "LED93")
      (value "RGB_WS2812C")
      (footprint "LED_5050-SMD_4P-WS2812")
      (fields
        (field (name "BOM_MANUFACTURER PART") "WS2812C")
        (field (name "BOM_SUPPLIER PART") "C114587")
        (field (name "CONTRIBUTOR") "LCSC")
      )
      (libsource (lib "LTC_Library1") (part "RGB_WS2812C"))
    )
    (comp (ref "LED94")
      (value "RGB_WS2812C")
      (footprint "LED_5050-SMD_4P-WS2812")
      (fields
        (field (name "BOM_MANUFACTURER PART") "WS2812C")
        (field (name "BOM_SUPPLIER PART") "C114587")
        (field (name "CONTRIBUTOR") "LCSC")
      )
      (libsource (lib "LTC_Library1") (part "RGB_WS2812C"))
    )
    (comp (ref "LED95")
      (value "RGB_WS2812C")
      (footprint "LED_5050-SMD_4P-WS2812")
      (fields
        (field (name "BOM_MANUFACTURER PART") "WS2812C")
        (field (name "BOM_SUPPLIER PART") "C114587")
        (field (name "CONTRIBUTOR") "LCSC")
      )
      (libsource (lib "LTC_Library1") (part "RGB_WS2812C"))
    )
    (comp (ref "LED96")
      (value "RGB_WS2812C")
      (footprint "LED_5050-SMD_4P-WS2812")
      (fields
        (field (name "BOM_MANUFACTURER PART") "WS2812C")
        (field (name "BOM_SUPPLIER PART") "C114587")
        (field (name "CONTRIBUTOR") "LCSC")
      )
      (libsource (lib "LTC_Library1") (part "RGB_WS2812C"))
    )
    (comp (ref "LED97")
      (value "RGB_WS2812C")
      (footprint "LED_5050-SMD_4P-WS2812")
      (fields
        (field (name "BOM_MANUFACTURER PART") "WS2812C")
        (field (name "BOM_SUPPLIER PART") "C114587")
        (field (name "CONTRIBUTOR") "LCSC")
      )
      (libsource (lib "LTC_Library1") (part "RGB_WS2812C"))
    )
    (comp (ref "LED98")
      (value "RGB_WS2812C")
      (footprint "LED_5050-SMD_4P-WS2812")
      (fields
        (field (name "BOM_MANUFACTURER PART") "WS2812C")
        (field (name "BOM_SUPPLIER PART") "C114587")
        (field (name "CONTRIBUTOR") "LCSC")
      )
      (libsource (lib "LTC_Library1") (part "RGB_WS2812C"))
    )
    (comp (ref "LED99")
      (value "RGB_WS2812C")
      (footprint "LED_5050-SMD_4P-WS2812")
      (fields
        (field (name "BOM_MANUFACTURER PART") "WS2812C")
        (field (name "BOM_SUPPLIER PART") "C114587")
        (field (name "CONTRIBUTOR") "LCSC")
      )
      (libsource (lib "LTC_Library1") (part "RGB_WS2812C"))
    )
    (comp (ref "LED100")
      (value "RGB_WS2812C")
      (footprint "LED_5050-SMD_4P-WS2812")
      (fields
        (field (name "BOM_MANUFACTURER PART") "WS2812C")
        (field (name "BOM_SUPPLIER PART") "C114587")
        (field (name "CONTRIBUTOR") "LCSC")
      )
      (libsource (lib "LTC_Library1") (part "RGB_WS2812C"))
    )
    (comp (ref "LED101")
      (value "RGB_WS2812C")
      (footprint "LED_5050-SMD_4P-WS2812")
      (fields
        (field (name "BOM_MANUFACTURER PART") "WS2812C")
        (field (name "BOM_SUPPLIER PART") "C114587")
        (field (name "CONTRIBUTOR") "LCSC")
      )
      (libsource (lib "LTC_Library1") (part "RGB_WS2812C"))
    )
    (comp (ref "LED102")
      (value "RGB_WS2812C")
      (footprint "LED_5050-SMD_4P-WS2812")
      (fields
        (field (name "BOM_MANUFACTURER PART") "WS2812C")
        (field (name "BOM_SUPPLIER PART") "C114587")
        (field (name "CONTRIBUTOR") "LCSC")
      )
      (libsource (lib "LTC_Library1") (part "RGB_WS2812C"))
    )
    (comp (ref "LED103")
      (value "RGB_WS2812C")
      (footprint "LED_5050-SMD_4P-WS2812")
      (fields
        (field (name "BOM_MANUFACTURER PART") "WS2812C")
        (field (name "BOM_SUPPLIER PART") "C114587")
        (field (name "CONTRIBUTOR") "LCSC")
      )
      (libsource (lib "LTC_Library1") (part "RGB_WS2812C"))
    )
    (comp (ref "LED104")
      (value "RGB_WS2812C")
      (footprint "LED_5050-SMD_4P-WS2812")
      (fields
        (field (name "BOM_MANUFACTURER PART") "WS2812C")
        (field (name "BOM_SUPPLIER PART") "C114587")
        (field (name "CONTRIBUTOR") "LCSC")
      )
      (libsource (lib "LTC_Library1") (part "RGB_WS2812C"))
    )
    (comp (ref "LED105")
      (value "RGB_WS2812C")
      (footprint "LED_5050-SMD_4P-WS2812")
      (fields
        (field (name "BOM_MANUFACTURER PART") "WS2812C")
        (field (name "BOM_SUPPLIER PART") "C114587")
        (field (name "CONTRIBUTOR") "LCSC")
      )
      (libsource (lib "LTC_Library1") (part "RGB_WS2812C"))
    )
    (comp (ref "LED106")
      (value "RGB_WS2812C")
      (footprint "LED_5050-SMD_4P-WS2812")
      (fields
        (field (name "BOM_MANUFACTURER PART") "WS2812C")
        (field (name "BOM_SUPPLIER PART") "C114587")
        (field (name "CONTRIBUTOR") "LCSC")
      )
      (libsource (lib "LTC_Library1") (part "RGB_WS2812C"))
    )
    (comp (ref "LED107")
      (value "RGB_WS2812C")
      (footprint "LED_5050-SMD_4P-WS2812")
      (fields
        (field (name "BOM_MANUFACTURER PART") "WS2812C")
        (field (name "BOM_SUPPLIER PART") "C114587")
        (field (name "CONTRIBUTOR") "LCSC")
      )
      (libsource (lib "LTC_Library1") (part "RGB_WS2812C"))
    )
    (comp (ref "LED108")
      (value "RGB_WS2812C")
      (footprint "LED_5050-SMD_4P-WS2812")
      (fields
        (field (name "BOM_MANUFACTURER PART") "WS2812C")
        (field (name "BOM_SUPPLIER PART") "C114587")
        (field (name "CONTRIBUTOR") "LCSC")
      )
      (libsource (lib "LTC_Library1") (part "RGB_WS2812C"))
    )
    (comp (ref "LED109")
      (value "RGB_WS2812C")
      (footprint "LED_5050-SMD_4P-WS2812")
      (fields
        (field (name "BOM_MANUFACTURER PART") "WS2812C")
        (field (name "BOM_SUPPLIER PART") "C114587")
        (field (name "CONTRIBUTOR") "LCSC")
      )
      (libsource (lib "LTC_Library1") (part "RGB_WS2812C"))
    )
    (comp (ref "LED110")
      (value "RGB_WS2812C")
      (footprint "LED_5050-SMD_4P-WS2812")
      (fields
        (field (name "BOM_MANUFACTURER PART") "WS2812C")
        (field (name "BOM_SUPPLIER PART") "C114587")
        (field (name "CONTRIBUTOR") "LCSC")
      )
      (libsource (lib "LTC_Library1") (part "RGB_WS2812C"))
    )
    (comp (ref "LED111")
      (value "RGB_WS2812C")
      (footprint "LED_5050-SMD_4P-WS2812")
      (fields
        (field (name "BOM_MANUFACTURER PART") "WS2812C")
        (field (name "BOM_SUPPLIER PART") "C114587")
        (field (name "CONTRIBUTOR") "LCSC")
      )
      (libsource (lib "LTC_Library1") (part "RGB_WS2812C"))
    )
    (comp (ref "LED112")
      (value "RGB_WS2812C")
      (footprint "LED_5050-SMD_4P-WS2812")
      (fields
        (field (name "BOM_MANUFACTURER PART") "WS2812C")
        (field (name "BOM_SUPPLIER PART") "C114587")
        (field (name "CONTRIBUTOR") "LCSC")
      )
      (libsource (lib "LTC_Library1") (part "RGB_WS2812C"))
    )
    (comp (ref "LED113")
      (value "RGB_WS2812C")
      (footprint "LED_5050-SMD_4P-WS2812")
      (fields
        (field (name "BOM_MANUFACTURER PART") "WS2812C")
        (field (name "BOM_SUPPLIER PART") "C114587")
        (field (name "CONTRIBUTOR") "LCSC")
      )
      (libsource (lib "LTC_Library1") (part "RGB_WS2812C"))
    )
    (comp (ref "LED114")
      (value "RGB_WS2812C")
      (footprint "LED_5050-SMD_4P-WS2812")
      (fields
        (field (name "BOM_MANUFACTURER PART") "WS2812C")
        (field (name "BOM_SUPPLIER PART") "C114587")
        (field (name "CONTRIBUTOR") "LCSC")
      )
      (libsource (lib "LTC_Library1") (part "RGB_WS2812C"))
    )
    (comp (ref "LED115")
      (value "RGB_WS2812C")
      (footprint "LED_5050-SMD_4P-WS2812")
      (fields
        (field (name "BOM_MANUFACTURER PART") "WS2812C")
        (field (name "BOM_SUPPLIER PART") "C114587")
        (field (name "CONTRIBUTOR") "LCSC")
      )
      (libsource (lib "LTC_Library1") (part "RGB_WS2812C"))
    )
    (comp (ref "LED116")
      (value "RGB_WS2812C")
      (footprint "LED_5050-SMD_4P-WS2812")
      (fields
        (field (name "BOM_MANUFACTURER PART") "WS2812C")
        (field (name "BOM_SUPPLIER PART") "C114587")
        (field (name "CONTRIBUTOR") "LCSC")
      )
      (libsource (lib "LTC_Library1") (part "RGB_WS2812C"))
    )
    (comp (ref "LED117")
      (value "RGB_WS2812C")
      (footprint "LED_5050-SMD_4P-WS2812")
      (fields
        (field (name "BOM_MANUFACTURER PART") "WS2812C")
        (field (name "BOM_SUPPLIER PART") "C114587")
        (field (name "CONTRIBUTOR") "LCSC")
      )
      (libsource (lib "LTC_Library1") (part "RGB_WS2812C"))
    )
    (comp (ref "LED118")
      (value "RGB_WS2812C")
      (footprint "LED_5050-SMD_4P-WS2812")
      (fields
        (field (name "BOM_MANUFACTURER PART") "WS2812C")
        (field (name "BOM_SUPPLIER PART") "C114587")
        (field (name "CONTRIBUTOR") "LCSC")
      )
      (libsource (lib "LTC_Library1") (part "RGB_WS2812C"))
    )
    (comp (ref "LED119")
      (value "RGB_WS2812C")
      (footprint "LED_5050-SMD_4P-WS2812")
      (fields
        (field (name "BOM_MANUFACTURER PART") "WS2812C")
        (field (name "BOM_SUPPLIER PART") "C114587")
        (field (name "CONTRIBUTOR") "LCSC")
      )
      (libsource (lib "LTC_Library1") (part "RGB_WS2812C"))
    )
    (comp (ref "LED120")
      (value "RGB_WS2812C")
      (footprint "LED_5050-SMD_4P-WS2812")
      (fields
        (field (name "BOM_MANUFACTURER PART") "WS2812C")
        (field (name "BOM_SUPPLIER PART") "C114587")
        (field (name "CONTRIBUTOR") "LCSC")
      )
      (libsource (lib "LTC_Library1") (part "RGB_WS2812C"))
    )
    (comp (ref "LED121")
      (value "RGB_WS2812C")
      (footprint "LED_5050-SMD_4P-WS2812")
      (fields
        (field (name "BOM_MANUFACTURER PART") "WS2812C")
        (field (name "BOM_SUPPLIER PART") "C114587")
        (field (name "CONTRIBUTOR") "LCSC")
      )
      (libsource (lib "LTC_Library1") (part "RGB_WS2812C"))
    )
    (comp (ref "LED122")
      (value "RGB_WS2812C")
      (footprint "LED_5050-SMD_4P-WS2812")
      (fields
        (field (name "BOM_MANUFACTURER PART") "WS2812C")
        (field (name "BOM_SUPPLIER PART") "C114587")
        (field (name "CONTRIBUTOR") "LCSC")
      )
      (libsource (lib "LTC_Library1") (part "RGB_WS2812C"))
    )
    (comp (ref "LED123")
      (value "RGB_WS2812C")
      (footprint "LED_5050-SMD_4P-WS2812")
      (fields
        (field (name "BOM_MANUFACTURER PART") "WS2812C")
        (field (name "BOM_SUPPLIER PART") "C114587")
        (field (name "CONTRIBUTOR") "LCSC")
      )
      (libsource (lib "LTC_Library1") (part "RGB_WS2812C"))
    )
    (comp (ref "LED124")
      (value "RGB_WS2812C")
      (footprint "LED_5050-SMD_4P-WS2812")
      (fields
        (field (name "BOM_MANUFACTURER PART") "WS2812C")
        (field (name "BOM_SUPPLIER PART") "C114587")
        (field (name "CONTRIBUTOR") "LCSC")
      )
      (libsource (lib "LTC_Library1") (part "RGB_WS2812C"))
    )
    (comp (ref "LED125")
      (value "RGB_WS2812C")
      (footprint "LED_5050-SMD_4P-WS2812")
      (fields
        (field (name "BOM_MANUFACTURER PART") "WS2812C")
        (field (name "BOM_SUPPLIER PART") "C114587")
        (field (name "CONTRIBUTOR") "LCSC")
      )
      (libsource (lib "LTC_Library1") (part "RGB_WS2812C"))
    )
    (comp (ref "LED126")
      (value "RGB_WS2812C")
      (footprint "LED_5050-SMD_4P-WS2812")
      (fields
        (field (name "BOM_MANUFACTURER PART") "WS2812C")
        (field (name "BOM_SUPPLIER PART") "C114587")
        (field (name "CONTRIBUTOR") "LCSC")
      )
      (libsource (lib "LTC_Library1") (part "RGB_WS2812C"))
    )
    (comp (ref "LED127")
      (value "RGB_WS2812C")
      (footprint "LED_5050-SMD_4P-WS2812")
      (fields
        (field (name "BOM_MANUFACTURER PART") "WS2812C")
        (field (name "BOM_SUPPLIER PART") "C114587")
        (field (name "CONTRIBUTOR") "LCSC")
      )
      (libsource (lib "LTC_Library1") (part "RGB_WS2812C"))
    )
    (comp (ref "LED128")
      (value "RGB_WS2812C")
      (footprint "LED_5050-SMD_4P-WS2812")
      (fields
        (field (name "BOM_MANUFACTURER PART") "WS2812C")
        (field (name "BOM_SUPPLIER PART") "C114587")
        (field (name "CONTRIBUTOR") "LCSC")
      )
      (libsource (lib "LTC_Library1") (part "RGB_WS2812C"))
    )
    (comp (ref "LED129")
      (value "RGB_WS2812C")
      (footprint "LED_5050-SMD_4P-WS2812")
      (fields
        (field (name "BOM_MANUFACTURER PART") "WS2812C")
        (field (name "BOM_SUPPLIER PART") "C114587")
        (field (name "CONTRIBUTOR") "LCSC")
      )
      (libsource (lib "LTC_Library1") (part "RGB_WS2812C"))
    )
    (comp (ref "LED130")
      (value "RGB_WS2812C")
      (footprint "LED_5050-SMD_4P-WS2812")
      (fields
        (field (name "BOM_MANUFACTURER PART") "WS2812C")
        (field (name "BOM_SUPPLIER PART") "C114587")
        (field (name "CONTRIBUTOR") "LCSC")
      )
      (libsource (lib "LTC_Library1") (part "RGB_WS2812C"))
    )
    (comp (ref "LED131")
      (value "RGB_WS2812C")
      (footprint "LED_5050-SMD_4P-WS2812")
      (fields
        (field (name "BOM_MANUFACTURER PART") "WS2812C")
        (field (name "BOM_SUPPLIER PART") "C114587")
        (field (name "CONTRIBUTOR") "LCSC")
      )
      (libsource (lib "LTC_Library1") (part "RGB_WS2812C"))
    )
    (comp (ref "LED132")
      (value "RGB_WS2812C")
      (footprint "LED_5050-SMD_4P-WS2812")
      (fields
        (field (name "BOM_MANUFACTURER PART") "WS2812C")
        (field (name "BOM_SUPPLIER PART") "C114587")
        (field (name "CONTRIBUTOR") "LCSC")
      )
      (libsource (lib "LTC_Library1") (part "RGB_WS2812C"))
    )
    (comp (ref "LED133")
      (value "RGB_WS2812C")
      (footprint "LED_5050-SMD_4P-WS2812")
      (fields
        (field (name "BOM_MANUFACTURER PART") "WS2812C")
        (field (name "BOM_SUPPLIER PART") "C114587")
        (field (name "CONTRIBUTOR") "LCSC")
      )
      (libsource (lib "LTC_Library1") (part "RGB_WS2812C"))
    )
    (comp (ref "LED134")
      (value "RGB_WS2812C")
      (footprint "LED_5050-SMD_4P-WS2812")
      (fields
        (field (name "BOM_MANUFACTURER PART") "WS2812C")
        (field (name "BOM_SUPPLIER PART") "C114587")
        (field (name "CONTRIBUTOR") "LCSC")
      )
      (libsource (lib "LTC_Library1") (part "RGB_WS2812C"))
    )
    (comp (ref "LED135")
      (value "RGB_WS2812C")
      (footprint "LED_5050-SMD_4P-WS2812")
      (fields
        (field (name "BOM_MANUFACTURER PART") "WS2812C")
        (field (name "BOM_SUPPLIER PART") "C114587")
        (field (name "CONTRIBUTOR") "LCSC")
      )
      (libsource (lib "LTC_Library1") (part "RGB_WS2812C"))
    )
    (comp (ref "LED136")
      (value "RGB_WS2812C")
      (footprint "LED_5050-SMD_4P-WS2812")
      (fields
        (field (name "BOM_MANUFACTURER PART") "WS2812C")
        (field (name "BOM_SUPPLIER PART") "C114587")
        (field (name "CONTRIBUTOR") "LCSC")
      )
      (libsource (lib "LTC_Library1") (part "RGB_WS2812C"))
    )
    (comp (ref "LED137")
      (value "RGB_WS2812C")
      (footprint "LED_5050-SMD_4P-WS2812")
      (fields
        (field (name "BOM_MANUFACTURER PART") "WS2812C")
        (field (name "BOM_SUPPLIER PART") "C114587")
        (field (name "CONTRIBUTOR") "LCSC")
      )
      (libsource (lib "LTC_Library1") (part "RGB_WS2812C"))
    )
    (comp (ref "LED138")
      (value "RGB_WS2812C")
      (footprint "LED_5050-SMD_4P-WS2812")
      (fields
        (field (name "BOM_MANUFACTURER PART") "WS2812C")
        (field (name "BOM_SUPPLIER PART") "C114587")
        (field (name "CONTRIBUTOR") "LCSC")
      )
      (libsource (lib "LTC_Library1") (part "RGB_WS2812C"))
    )
    (comp (ref "LED139")
      (value "RGB_WS2812C")
      (footprint "LED_5050-SMD_4P-WS2812")
      (fields
        (field (name "BOM_MANUFACTURER PART") "WS2812C")
        (field (name "BOM_SUPPLIER PART") "C114587")
        (field (name "CONTRIBUTOR") "LCSC")
      )
      (libsource (lib "LTC_Library1") (part "RGB_WS2812C"))
    )
    (comp (ref "LED140")
      (value "RGB_WS2812C")
      (footprint "LED_5050-SMD_4P-WS2812")
      (fields
        (field (name "BOM_MANUFACTURER PART") "WS2812C")
        (field (name "BOM_SUPPLIER PART") "C114587")
        (field (name "CONTRIBUTOR") "LCSC")
      )
      (libsource (lib "LTC_Library1") (part "RGB_WS2812C"))
    )
    (comp (ref "LED141")
      (value "RGB_WS2812C")
      (footprint "LED_5050-SMD_4P-WS2812")
      (fields
        (field (name "BOM_MANUFACTURER PART") "WS2812C")
        (field (name "BOM_SUPPLIER PART") "C114587")
        (field (name "CONTRIBUTOR") "LCSC")
      )
      (libsource (lib "LTC_Library1") (part "RGB_WS2812C"))
    )
    (comp (ref "LED142")
      (value "RGB_WS2812C")
      (footprint "LED_5050-SMD_4P-WS2812")
      (fields
        (field (name "BOM_MANUFACTURER PART") "WS2812C")
        (field (name "BOM_SUPPLIER PART") "C114587")
        (field (name "CONTRIBUTOR") "LCSC")
      )
      (libsource (lib "LTC_Library1") (part "RGB_WS2812C"))
    )
    (comp (ref "LED143")
      (value "RGB_WS2812C")
      (footprint "LED_5050-SMD_4P-WS2812")
      (fields
        (field (name "BOM_MANUFACTURER PART") "WS2812C")
        (field (name "BOM_SUPPLIER PART") "C114587")
        (field (name "CONTRIBUTOR") "LCSC")
      )
      (libsource (lib "LTC_Library1") (part "RGB_WS2812C"))
    )
    (comp (ref "LED144")
      (value "RGB_WS2812C")
      (footprint "LED_5050-SMD_4P-WS2812")
      (fields
        (field (name "BOM_MANUFACTURER PART") "WS2812C")
        (field (name "BOM_SUPPLIER PART") "C114587")
        (field (name "CONTRIBUTOR") "LCSC")
      )
      (libsource (lib "LTC_Library1") (part "RGB_WS2812C"))
    )
    (comp (ref "LED145")
      (value "RGB_WS2812C")
      (footprint "LED_5050-SMD_4P-WS2812")
      (fields
        (field (name "BOM_MANUFACTURER PART") "WS2812C")
        (field (name "BOM_SUPPLIER PART") "C114587")
        (field (name "CONTRIBUTOR") "LCSC")
      )
      (libsource (lib "LTC_Library1") (part "RGB_WS2812C"))
    )
    (comp (ref "LED146")
      (value "RGB_WS2812C")
      (footprint "LED_5050-SMD_4P-WS2812")
      (fields
        (field (name "BOM_MANUFACTURER PART") "WS2812C")
        (field (name "BOM_SUPPLIER PART") "C114587")
        (field (name "CONTRIBUTOR") "LCSC")
      )
      (libsource (lib "LTC_Library1") (part "RGB_WS2812C"))
    )
    (comp (ref "LED147")
      (value "RGB_WS2812C")
      (footprint "LED_5050-SMD_4P-WS2812")
      (fields
        (field (name "BOM_MANUFACTURER PART") "WS2812C")
        (field (name "BOM_SUPPLIER PART") "C114587")
        (field (name "CONTRIBUTOR") "LCSC")
      )
      (libsource (lib "LTC_Library1") (part "RGB_WS2812C"))
    )
    (comp (ref "LED148")
      (value "RGB_WS2812C")
      (footprint "LED_5050-SMD_4P-WS2812")
      (fields
        (field (name "BOM_MANUFACTURER PART") "WS2812C")
        (field (name "BOM_SUPPLIER PART") "C114587")
        (field (name "CONTRIBUTOR") "LCSC")
      )
      (libsource (lib "LTC_Library1") (part "RGB_WS2812C"))
    )
    (comp (ref "LED149")
      (value "RGB_WS2812C")
      (footprint "LED_5050-SMD_4P-WS2812")
      (fields
        (field (name "BOM_MANUFACTURER PART") "WS2812C")
        (field (name "BOM_SUPPLIER PART") "C114587")
        (field (name "CONTRIBUTOR") "LCSC")
      )
      (libsource (lib "LTC_Library1") (part "RGB_WS2812C"))
    )
    (comp (ref "LED150")
      (value "RGB_WS2812C")
      (footprint "LED_5050-SMD_4P-WS2812")
      (fields
        (field (name "BOM_MANUFACTURER PART") "WS2812C")
        (field (name "BOM_SUPPLIER PART") "C114587")
        (field (name "CONTRIBUTOR") "LCSC")
      )
      (libsource (lib "LTC_Library1") (part "RGB_WS2812C"))
    )
    (comp (ref "LED151")
      (value "RGB_WS2812C")
      (footprint "LED_5050-SMD_4P-WS2812")
      (fields
        (field (name "BOM_MANUFACTURER PART") "WS2812C")
        (field (name "BOM_SUPPLIER PART") "C114587")
        (field (name "CONTRIBUTOR") "LCSC")
      )
      (libsource (lib "LTC_Library1") (part "RGB_WS2812C"))
    )
    (comp (ref "LED152")
      (value "RGB_WS2812C")
      (footprint "LED_5050-SMD_4P-WS2812")
      (fields
        (field (name "BOM_MANUFACTURER PART") "WS2812C")
        (field (name "BOM_SUPPLIER PART") "C114587")
        (field (name "CONTRIBUTOR") "LCSC")
      )
      (libsource (lib "LTC_Library1") (part "RGB_WS2812C"))
    )
    (comp (ref "LED153")
      (value "RGB_WS2812C")
      (footprint "LED_5050-SMD_4P-WS2812")
      (fields
        (field (name "BOM_MANUFACTURER PART") "WS2812C")
        (field (name "BOM_SUPPLIER PART") "C114587")
        (field (name "CONTRIBUTOR") "LCSC")
      )
      (libsource (lib "LTC_Library1") (part "RGB_WS2812C"))
    )
    (comp (ref "LED154")
      (value "RGB_WS2812C")
      (footprint "LED_5050-SMD_4P-WS2812")
      (fields
        (field (name "BOM_MANUFACTURER PART") "WS2812C")
        (field (name "BOM_SUPPLIER PART") "C114587")
        (field (name "CONTRIBUTOR") "LCSC")
      )
      (libsource (lib "LTC_Library1") (part "RGB_WS2812C"))
    )
    (comp (ref "LED155")
      (value "RGB_WS2812C")
      (footprint "LED_5050-SMD_4P-WS2812")
      (fields
        (field (name "BOM_MANUFACTURER PART") "WS2812C")
        (field (name "BOM_SUPPLIER PART") "C114587")
        (field (name "CONTRIBUTOR") "LCSC")
      )
      (libsource (lib "LTC_Library1") (part "RGB_WS2812C"))
    )
    (comp (ref "LED156")
      (value "RGB_WS2812C")
      (footprint "LED_5050-SMD_4P-WS2812")
      (fields
        (field (name "BOM_MANUFACTURER PART") "WS2812C")
        (field (name "BOM_SUPPLIER PART") "C114587")
        (field (name "CONTRIBUTOR") "LCSC")
      )
      (libsource (lib "LTC_Library1") (part "RGB_WS2812C"))
    )
    (comp (ref "LED157")
      (value "RGB_WS2812C")
      (footprint "LED_5050-SMD_4P-WS2812")
      (fields
        (field (name "BOM_MANUFACTURER PART") "WS2812C")
        (field (name "BOM_SUPPLIER PART") "C114587")
        (field (name "CONTRIBUTOR") "LCSC")
      )
      (libsource (lib "LTC_Library1") (part "RGB_WS2812C"))
    )
    (comp (ref "LED158")
      (value "RGB_WS2812C")
      (footprint "LED_5050-SMD_4P-WS2812")
      (fields
        (field (name "BOM_MANUFACTURER PART") "WS2812C")
        (field (name "BOM_SUPPLIER PART") "C114587")
        (field (name "CONTRIBUTOR") "LCSC")
      )
      (libsource (lib "LTC_Library1") (part "RGB_WS2812C"))
    )
    (comp (ref "LED159")
      (value "RGB_WS2812C")
      (footprint "LED_5050-SMD_4P-WS2812")
      (fields
        (field (name "BOM_MANUFACTURER PART") "WS2812C")
        (field (name "BOM_SUPPLIER PART") "C114587")
        (field (name "CONTRIBUTOR") "LCSC")
      )
      (libsource (lib "LTC_Library1") (part "RGB_WS2812C"))
    )
    (comp (ref "LED160")
      (value "RGB_WS2812C")
      (footprint "LED_5050-SMD_4P-WS2812")
      (fields
        (field (name "BOM_MANUFACTURER PART") "WS2812C")
        (field (name "BOM_SUPPLIER PART") "C114587")
        (field (name "CONTRIBUTOR") "LCSC")
      )
      (libsource (lib "LTC_Library1") (part "RGB_WS2812C"))
    )
    (comp (ref "LED161")
      (value "RGB_WS2812C")
      (footprint "LED_5050-SMD_4P-WS2812")
      (fields
        (field (name "BOM_MANUFACTURER PART") "WS2812C")
        (field (name "BOM_SUPPLIER PART") "C114587")
        (field (name "CONTRIBUTOR") "LCSC")
      )
      (libsource (lib "LTC_Library1") (part "RGB_WS2812C"))
    )
    (comp (ref "LED162")
      (value "RGB_WS2812C")
      (footprint "LED_5050-SMD_4P-WS2812")
      (fields
        (field (name "BOM_MANUFACTURER PART") "WS2812C")
        (field (name "BOM_SUPPLIER PART") "C114587")
        (field (name "CONTRIBUTOR") "LCSC")
      )
      (libsource (lib "LTC_Library1") (part "RGB_WS2812C"))
    )
    (comp (ref "LED163")
      (value "RGB_WS2812C")
      (footprint "LED_5050-SMD_4P-WS2812")
      (fields
        (field (name "BOM_MANUFACTURER PART") "WS2812C")
        (field (name "BOM_SUPPLIER PART") "C114587")
        (field (name "CONTRIBUTOR") "LCSC")
      )
      (libsource (lib "LTC_Library1") (part "RGB_WS2812C"))
    )
    (comp (ref "LED164")
      (value "RGB_WS2812C")
      (footprint "LED_5050-SMD_4P-WS2812")
      (fields
        (field (name "BOM_MANUFACTURER PART") "WS2812C")
        (field (name "BOM_SUPPLIER PART") "C114587")
        (field (name "CONTRIBUTOR") "LCSC")
      )
      (libsource (lib "LTC_Library1") (part "RGB_WS2812C"))
    )
    (comp (ref "LED165")
      (value "RGB_WS2812C")
      (footprint "LED_5050-SMD_4P-WS2812")
      (fields
        (field (name "BOM_MANUFACTURER PART") "WS2812C")
        (field (name "BOM_SUPPLIER PART") "C114587")
        (field (name "CONTRIBUTOR") "LCSC")
      )
      (libsource (lib "LTC_Library1") (part "RGB_WS2812C"))
    )
    (comp (ref "LED166")
      (value "RGB_WS2812C")
      (footprint "LED_5050-SMD_4P-WS2812")
      (fields
        (field (name "BOM_MANUFACTURER PART") "WS2812C")
        (field (name "BOM_SUPPLIER PART") "C114587")
        (field (name "CONTRIBUTOR") "LCSC")
      )
      (libsource (lib "LTC_Library1") (part "RGB_WS2812C"))
    )
    (comp (ref "LED167")
      (value "RGB_WS2812C")
      (footprint "LED_5050-SMD_4P-WS2812")
      (fields
        (field (name "BOM_MANUFACTURER PART") "WS2812C")
        (field (name "BOM_SUPPLIER PART") "C114587")
        (field (name "CONTRIBUTOR") "LCSC")
      )
      (libsource (lib "LTC_Library1") (part "RGB_WS2812C"))
    )
    (comp (ref "LED168")
      (value "RGB_WS2812C")
      (footprint "LED_5050-SMD_4P-WS2812")
      (fields
        (field (name "BOM_MANUFACTURER PART") "WS2812C")
        (field (name "BOM_SUPPLIER PART") "C114587")
        (field (name "CONTRIBUTOR") "LCSC")
      )
      (libsource (lib "LTC_Library1") (part "RGB_WS2812C"))
    )
    (comp (ref "LED169")
      (value "RGB_WS2812C")
      (footprint "LED_5050-SMD_4P-WS2812")
      (fields
        (field (name "BOM_MANUFACTURER PART") "WS2812C")
        (field (name "BOM_SUPPLIER PART") "C114587")
        (field (name "CONTRIBUTOR") "LCSC")
      )
      (libsource (lib "LTC_Library1") (part "RGB_WS2812C"))
    )
    (comp (ref "LED170")
      (value "RGB_WS2812C")
      (footprint "LED_5050-SMD_4P-WS2812")
      (fields
        (field (name "BOM_MANUFACTURER PART") "WS2812C")
        (field (name "BOM_SUPPLIER PART") "C114587")
        (field (name "CONTRIBUTOR") "LCSC")
      )
      (libsource (lib "LTC_Library1") (part "RGB_WS2812C"))
    )
    (comp (ref "LED171")
      (value "RGB_WS2812C")
      (footprint "LED_5050-SMD_4P-WS2812")
      (fields
        (field (name "BOM_MANUFACTURER PART") "WS2812C")
        (field (name "BOM_SUPPLIER PART") "C114587")
        (field (name "CONTRIBUTOR") "LCSC")
      )
      (libsource (lib "LTC_Library1") (part "RGB_WS2812C"))
    )
    (comp (ref "LED172")
      (value "RGB_WS2812C")
      (footprint "LED_5050-SMD_4P-WS2812")
      (fields
        (field (name "BOM_MANUFACTURER PART") "WS2812C")
        (field (name "BOM_SUPPLIER PART") "C114587")
        (field (name "CONTRIBUTOR") "LCSC")
      )
      (libsource (lib "LTC_Library1") (part "RGB_WS2812C"))
    )
    (comp (ref "LED173")
      (value "RGB_WS2812C")
      (footprint "LED_5050-SMD_4P-WS2812")
      (fields
        (field (name "BOM_MANUFACTURER PART") "WS2812C")
        (field (name "BOM_SUPPLIER PART") "C114587")
        (field (name "CONTRIBUTOR") "LCSC")
      )
      (libsource (lib "LTC_Library1") (part "RGB_WS2812C"))
    )
    (comp (ref "LED174")
      (value "RGB_WS2812C")
      (footprint "LED_5050-SMD_4P-WS2812")
      (fields
        (field (name "BOM_MANUFACTURER PART") "WS2812C")
        (field (name "BOM_SUPPLIER PART") "C114587")
        (field (name "CONTRIBUTOR") "LCSC")
      )
      (libsource (lib "LTC_Library1") (part "RGB_WS2812C"))
    )
    (comp (ref "LED175")
      (value "RGB_WS2812C")
      (footprint "LED_5050-SMD_4P-WS2812")
      (fields
        (field (name "BOM_MANUFACTURER PART") "WS2812C")
        (field (name "BOM_SUPPLIER PART") "C114587")
        (field (name "CONTRIBUTOR") "LCSC")
      )
      (libsource (lib "LTC_Library1") (part "RGB_WS2812C"))
    )
    (comp (ref "LED176")
      (value "RGB_WS2812C")
      (footprint "LED_5050-SMD_4P-WS2812")
      (fields
        (field (name "BOM_MANUFACTURER PART") "WS2812C")
        (field (name "BOM_SUPPLIER PART") "C114587")
        (field (name "CONTRIBUTOR") "LCSC")
      )
      (libsource (lib "LTC_Library1") (part "RGB_WS2812C"))
    )
    (comp (ref "LED177")
      (value "RGB_WS2812C")
      (footprint "LED_5050-SMD_4P-WS2812")
      (fields
        (field (name "BOM_MANUFACTURER PART") "WS2812C")
        (field (name "BOM_SUPPLIER PART") "C114587")
        (field (name "CONTRIBUTOR") "LCSC")
      )
      (libsource (lib "LTC_Library1") (part "RGB_WS2812C"))
    )
    (comp (ref "LED178")
      (value "RGB_WS2812C")
      (footprint "LED_5050-SMD_4P-WS2812")
      (fields
        (field (name "BOM_MANUFACTURER PART") "WS2812C")
        (field (name "BOM_SUPPLIER PART") "C114587")
        (field (name "CONTRIBUTOR") "LCSC")
      )
      (libsource (lib "LTC_Library1") (part "RGB_WS2812C"))
    )
    (comp (ref "LED179")
      (value "RGB_WS2812C")
      (footprint "LED_5050-SMD_4P-WS2812")
      (fields
        (field (name "BOM_MANUFACTURER PART") "WS2812C")
        (field (name "BOM_SUPPLIER PART") "C114587")
        (field (name "CONTRIBUTOR") "LCSC")
      )
      (libsource (lib "LTC_Library1") (part "RGB_WS2812C"))
    )
    (comp (ref "LED180")
      (value "RGB_WS2812C")
      (footprint "LED_5050-SMD_4P-WS2812")
      (fields
        (field (name "BOM_MANUFACTURER PART") "WS2812C")
        (field (name "BOM_SUPPLIER PART") "C114587")
        (field (name "CONTRIBUTOR") "LCSC")
      )
      (libsource (lib "LTC_Library1") (part "RGB_WS2812C"))
    )
    (comp (ref "LED181")
      (value "RGB_WS2812C")
      (footprint "LED_5050-SMD_4P-WS2812")
      (fields
        (field (name "BOM_MANUFACTURER PART") "WS2812C")
        (field (name "BOM_SUPPLIER PART") "C114587")
        (field (name "CONTRIBUTOR") "LCSC")
      )
      (libsource (lib "LTC_Library1") (part "RGB_WS2812C"))
    )
    (comp (ref "LED182")
      (value "RGB_WS2812C")
      (footprint "LED_5050-SMD_4P-WS2812")
      (fields
        (field (name "BOM_MANUFACTURER PART") "WS2812C")
        (field (name "BOM_SUPPLIER PART") "C114587")
        (field (name "CONTRIBUTOR") "LCSC")
      )
      (libsource (lib "LTC_Library1") (part "RGB_WS2812C"))
    )
    (comp (ref "LED183")
      (value "RGB_WS2812C")
      (footprint "LED_5050-SMD_4P-WS2812")
      (fields
        (field (name "BOM_MANUFACTURER PART") "WS2812C")
        (field (name "BOM_SUPPLIER PART") "C114587")
        (field (name "CONTRIBUTOR") "LCSC")
      )
      (libsource (lib "LTC_Library1") (part "RGB_WS2812C"))
    )
    (comp (ref "LED184")
      (value "RGB_WS2812C")
      (footprint "LED_5050-SMD_4P-WS2812")
      (fields
        (field (name "BOM_MANUFACTURER PART") "WS2812C")
        (field (name "BOM_SUPPLIER PART") "C114587")
        (field (name "CONTRIBUTOR") "LCSC")
      )
      (libsource (lib "LTC_Library1") (part "RGB_WS2812C"))
    )
    (comp (ref "LED185")
      (value "RGB_WS2812C")
      (footprint "LED_5050-SMD_4P-WS2812")
      (fields
        (field (name "BOM_MANUFACTURER PART") "WS2812C")
        (field (name "BOM_SUPPLIER PART") "C114587")
        (field (name "CONTRIBUTOR") "LCSC")
      )
      (libsource (lib "LTC_Library1") (part "RGB_WS2812C"))
    )
    (comp (ref "LED186")
      (value "RGB_WS2812C")
      (footprint "LED_5050-SMD_4P-WS2812")
      (fields
        (field (name "BOM_MANUFACTURER PART") "WS2812C")
        (field (name "BOM_SUPPLIER PART") "C114587")
        (field (name "CONTRIBUTOR") "LCSC")
      )
      (libsource (lib "LTC_Library1") (part "RGB_WS2812C"))
    )
    (comp (ref "LED187")
      (value "RGB_WS2812C")
      (footprint "LED_5050-SMD_4P-WS2812")
      (fields
        (field (name "BOM_MANUFACTURER PART") "WS2812C")
        (field (name "BOM_SUPPLIER PART") "C114587")
        (field (name "CONTRIBUTOR") "LCSC")
      )
      (libsource (lib "LTC_Library1") (part "RGB_WS2812C"))
    )
    (comp (ref "LED188")
      (value "RGB_WS2812C")
      (footprint "LED_5050-SMD_4P-WS2812")
      (fields
        (field (name "BOM_MANUFACTURER PART") "WS2812C")
        (field (name "BOM_SUPPLIER PART") "C114587")
        (field (name "CONTRIBUTOR") "LCSC")
      )
      (libsource (lib "LTC_Library1") (part "RGB_WS2812C"))
    )
    (comp (ref "LED189")
      (value "RGB_WS2812C")
      (footprint "LED_5050-SMD_4P-WS2812")
      (fields
        (field (name "BOM_MANUFACTURER PART") "WS2812C")
        (field (name "BOM_SUPPLIER PART") "C114587")
        (field (name "CONTRIBUTOR") "LCSC")
      )
      (libsource (lib "LTC_Library1") (part "RGB_WS2812C"))
    )
    (comp (ref "LED190")
      (value "RGB_WS2812C")
      (footprint "LED_5050-SMD_4P-WS2812")
      (fields
        (field (name "BOM_MANUFACTURER PART") "WS2812C")
        (field (name "BOM_SUPPLIER PART") "C114587")
        (field (name "CONTRIBUTOR") "LCSC")
      )
      (libsource (lib "LTC_Library1") (part "RGB_WS2812C"))
    )
    (comp (ref "LED191")
      (value "RGB_WS2812C")
      (footprint "LED_5050-SMD_4P-WS2812")
      (fields
        (field (name "BOM_MANUFACTURER PART") "WS2812C")
        (field (name "BOM_SUPPLIER PART") "C114587")
        (field (name "CONTRIBUTOR") "LCSC")
      )
      (libsource (lib "LTC_Library1") (part "RGB_WS2812C"))
    )
    (comp (ref "LED192")
      (value "RGB_WS2812C")
      (footprint "LED_5050-SMD_4P-WS2812")
      (fields
        (field (name "BOM_MANUFACTURER PART") "WS2812C")
        (field (name "BOM_SUPPLIER PART") "C114587")
        (field (name "CONTRIBUTOR") "LCSC")
      )
      (libsource (lib "LTC_Library1") (part "RGB_WS2812C"))
    )
    (comp (ref "LED193")
      (value "RGB_WS2812C")
      (footprint "LED_5050-SMD_4P-WS2812")
      (fields
        (field (name "BOM_MANUFACTURER PART") "WS2812C")
        (field (name "BOM_SUPPLIER PART") "C114587")
        (field (name "CONTRIBUTOR") "LCSC")
      )
      (libsource (lib "LTC_Library1") (part "RGB_WS2812C"))
    )
    (comp (ref "LED194")
      (value "RGB_WS2812C")
      (footprint "LED_5050-SMD_4P-WS2812")
      (fields
        (field (name "BOM_MANUFACTURER PART") "WS2812C")
        (field (name "BOM_SUPPLIER PART") "C114587")
        (field (name "CONTRIBUTOR") "LCSC")
      )
      (libsource (lib "LTC_Library1") (part "RGB_WS2812C"))
    )
    (comp (ref "LED195")
      (value "RGB_WS2812C")
      (footprint "LED_5050-SMD_4P-WS2812")
      (fields
        (field (name "BOM_MANUFACTURER PART") "WS2812C")
        (field (name "BOM_SUPPLIER PART") "C114587")
        (field (name "CONTRIBUTOR") "LCSC")
      )
      (libsource (lib "LTC_Library1") (part "RGB_WS2812C"))
    )
    (comp (ref "LED196")
      (value "RGB_WS2812C")
      (footprint "LED_5050-SMD_4P-WS2812")
      (fields
        (field (name "BOM_MANUFACTURER PART") "WS2812C")
        (field (name "BOM_SUPPLIER PART") "C114587")
        (field (name "CONTRIBUTOR") "LCSC")
      )
      (libsource (lib "LTC_Library1") (part "RGB_WS2812C"))
    )
    (comp (ref "LED197")
      (value "RGB_WS2812C")
      (footprint "LED_5050-SMD_4P-WS2812")
      (fields
        (field (name "BOM_MANUFACTURER PART") "WS2812C")
        (field (name "BOM_SUPPLIER PART") "C114587")
        (field (name "CONTRIBUTOR") "LCSC")
      )
      (libsource (lib "LTC_Library1") (part "RGB_WS2812C"))
    )
    (comp (ref "LED198")
      (value "RGB_WS2812C")
      (footprint "LED_5050-SMD_4P-WS2812")
      (fields
        (field (name "BOM_MANUFACTURER PART") "WS2812C")
        (field (name "BOM_SUPPLIER PART") "C114587")
        (field (name "CONTRIBUTOR") "LCSC")
      )
      (libsource (lib "LTC_Library1") (part "RGB_WS2812C"))
    )
    (comp (ref "LED199")
      (value "RGB_WS2812C")
      (footprint "LED_5050-SMD_4P-WS2812")
      (fields
        (field (name "BOM_MANUFACTURER PART") "WS2812C")
        (field (name "BOM_SUPPLIER PART") "C114587")
        (field (name "CONTRIBUTOR") "LCSC")
      )
      (libsource (lib "LTC_Library1") (part "RGB_WS2812C"))
    )
    (comp (ref "LED200")
      (value "RGB_WS2812C")
      (footprint "LED_5050-SMD_4P-WS2812")
      (fields
        (field (name "BOM_MANUFACTURER PART") "WS2812C")
        (field (name "BOM_SUPPLIER PART") "C114587")
        (field (name "CONTRIBUTOR") "LCSC")
      )
      (libsource (lib "LTC_Library1") (part "RGB_WS2812C"))
    )
    (comp (ref "LED201")
      (value "RGB_WS2812C")
      (footprint "LED_5050-SMD_4P-WS2812")
      (fields
        (field (name "BOM_MANUFACTURER PART") "WS2812C")
        (field (name "BOM_SUPPLIER PART") "C114587")
        (field (name "CONTRIBUTOR") "LCSC")
      )
      (libsource (lib "LTC_Library1") (part "RGB_WS2812C"))
    )
    (comp (ref "LED202")
      (value "RGB_WS2812C")
      (footprint "LED_5050-SMD_4P-WS2812")
      (fields
        (field (name "BOM_MANUFACTURER PART") "WS2812C")
        (field (name "BOM_SUPPLIER PART") "C114587")
        (field (name "CONTRIBUTOR") "LCSC")
      )
      (libsource (lib "LTC_Library1") (part "RGB_WS2812C"))
    )
    (comp (ref "LED203")
      (value "RGB_WS2812C")
      (footprint "LED_5050-SMD_4P-WS2812")
      (fields
        (field (name "BOM_MANUFACTURER PART") "WS2812C")
        (field (name "BOM_SUPPLIER PART") "C114587")
        (field (name "CONTRIBUTOR") "LCSC")
      )
      (libsource (lib "LTC_Library1") (part "RGB_WS2812C"))
    )
    (comp (ref "LED204")
      (value "RGB_WS2812C")
      (footprint "LED_5050-SMD_4P-WS2812")
      (fields
        (field (name "BOM_MANUFACTURER PART") "WS2812C")
        (field (name "BOM_SUPPLIER PART") "C114587")
        (field (name "CONTRIBUTOR") "LCSC")
      )
      (libsource (lib "LTC_Library1") (part "RGB_WS2812C"))
    )
    (comp (ref "LED205")
      (value "RGB_WS2812C")
      (footprint "LED_5050-SMD_4P-WS2812")
      (fields
        (field (name "BOM_MANUFACTURER PART") "WS2812C")
        (field (name "BOM_SUPPLIER PART") "C114587")
        (field (name "CONTRIBUTOR") "LCSC")
      )
      (libsource (lib "LTC_Library1") (part "RGB_WS2812C"))
    )
    (comp (ref "LED206")
      (value "RGB_WS2812C")
      (footprint "LED_5050-SMD_4P-WS2812")
      (fields
        (field (name "BOM_MANUFACTURER PART") "WS2812C")
        (field (name "BOM_SUPPLIER PART") "C114587")
        (field (name "CONTRIBUTOR") "LCSC")
      )
      (libsource (lib "LTC_Library1") (part "RGB_WS2812C"))
    )
    (comp (ref "LED207")
      (value "RGB_WS2812C")
      (footprint "LED_5050-SMD_4P-WS2812")
      (fields
        (field (name "BOM_MANUFACTURER PART") "WS2812C")
        (field (name "BOM_SUPPLIER PART") "C114587")
        (field (name "CONTRIBUTOR") "LCSC")
      )
      (libsource (lib "LTC_Library1") (part "RGB_WS2812C"))
    )
    (comp (ref "LED208")
      (value "RGB_WS2812C")
      (footprint "LED_5050-SMD_4P-WS2812")
      (fields
        (field (name "BOM_MANUFACTURER PART") "WS2812C")
        (field (name "BOM_SUPPLIER PART") "C114587")
        (field (name "CONTRIBUTOR") "LCSC")
      )
      (libsource (lib "LTC_Library1") (part "RGB_WS2812C"))
    )
    (comp (ref "LED209")
      (value "RGB_WS2812C")
      (footprint "LED_5050-SMD_4P-WS2812")
      (fields
        (field (name "BOM_MANUFACTURER PART") "WS2812C")
        (field (name "BOM_SUPPLIER PART") "C114587")
        (field (name "CONTRIBUTOR") "LCSC")
      )
      (libsource (lib "LTC_Library1") (part "RGB_WS2812C"))
    )
    (comp (ref "LED210")
      (value "RGB_WS2812C")
      (footprint "LED_5050-SMD_4P-WS2812")
      (fields
        (field (name "BOM_MANUFACTURER PART") "WS2812C")
        (field (name "BOM_SUPPLIER PART") "C114587")
        (field (name "CONTRIBUTOR") "LCSC")
      )
      (libsource (lib "LTC_Library1") (part "RGB_WS2812C"))
    )
    (comp (ref "LED211")
      (value "RGB_WS2812C")
      (footprint "LED_5050-SMD_4P-WS2812")
      (fields
        (field (name "BOM_MANUFACTURER PART") "WS2812C")
        (field (name "BOM_SUPPLIER PART") "C114587")
        (field (name "CONTRIBUTOR") "LCSC")
      )
      (libsource (lib "LTC_Library1") (part "RGB_WS2812C"))
    )
    (comp (ref "LED212")
      (value "RGB_WS2812C")
      (footprint "LED_5050-SMD_4P-WS2812")
      (fields
        (field (name "BOM_MANUFACTURER PART") "WS2812C")
        (field (name "BOM_SUPPLIER PART") "C114587")
        (field (name "CONTRIBUTOR") "LCSC")
      )
      (libsource (lib "LTC_Library1") (part "RGB_WS2812C"))
    )
    (comp (ref "LED213")
      (value "RGB_WS2812C")
      (footprint "LED_5050-SMD_4P-WS2812")
      (fields
        (field (name "BOM_MANUFACTURER PART") "WS2812C")
        (field (name "BOM_SUPPLIER PART") "C114587")
        (field (name "CONTRIBUTOR") "LCSC")
      )
      (libsource (lib "LTC_Library1") (part "RGB_WS2812C"))
    )
    (comp (ref "LED214")
      (value "RGB_WS2812C")
      (footprint "LED_5050-SMD_4P-WS2812")
      (fields
        (field (name "BOM_MANUFACTURER PART") "WS2812C")
        (field (name "BOM_SUPPLIER PART") "C114587")
        (field (name "CONTRIBUTOR") "LCSC")
      )
      (libsource (lib "LTC_Library1") (part "RGB_WS2812C"))
    )
    (comp (ref "LED215")
      (value "RGB_WS2812C")
      (footprint "LED_5050-SMD_4P-WS2812")
      (fields
        (field (name "BOM_MANUFACTURER PART") "WS2812C")
        (field (name "BOM_SUPPLIER PART") "C114587")
        (field (name "CONTRIBUTOR") "LCSC")
      )
      (libsource (lib "LTC_Library1") (part "RGB_WS2812C"))
    )
    (comp (ref "LED216")
      (value "RGB_WS2812C")
      (footprint "LED_5050-SMD_4P-WS2812")
      (fields
        (field (name "BOM_MANUFACTURER PART") "WS2812C")
        (field (name "BOM_SUPPLIER PART") "C114587")
        (field (name "CONTRIBUTOR") "LCSC")
      )
      (libsource (lib "LTC_Library1") (part "RGB_WS2812C"))
    )
    (comp (ref "LED217")
      (value "RGB_WS2812C")
      (footprint "LED_5050-SMD_4P-WS2812")
      (fields
        (field (name "BOM_MANUFACTURER PART") "WS2812C")
        (field (name "BOM_SUPPLIER PART") "C114587")
        (field (name "CONTRIBUTOR") "LCSC")
      )
      (libsource (lib "LTC_Library1") (part "RGB_WS2812C"))
    )
    (comp (ref "LED218")
      (value "RGB_WS2812C")
      (footprint "LED_5050-SMD_4P-WS2812")
      (fields
        (field (name "BOM_MANUFACTURER PART") "WS2812C")
        (field (name "BOM_SUPPLIER PART") "C114587")
        (field (name "CONTRIBUTOR") "LCSC")
      )
      (libsource (lib "LTC_Library1") (part "RGB_WS2812C"))
    )
    (comp (ref "LED219")
      (value "RGB_WS2812C")
      (footprint "LED_5050-SMD_4P-WS2812")
      (fields
        (field (name "BOM_MANUFACTURER PART") "WS2812C")
        (field (name "BOM_SUPPLIER PART") "C114587")
        (field (name "CONTRIBUTOR") "LCSC")
      )
      (libsource (lib "LTC_Library1") (part "RGB_WS2812C"))
    )
    (comp (ref "LED220")
      (value "RGB_WS2812C")
      (footprint "LED_5050-SMD_4P-WS2812")
      (fields
        (field (name "BOM_MANUFACTURER PART") "WS2812C")
        (field (name "BOM_SUPPLIER PART") "C114587")
        (field (name "CONTRIBUTOR") "LCSC")
      )
      (libsource (lib "LTC_Library1") (part "RGB_WS2812C"))
    )
    (comp (ref "LED221")
      (value "RGB_WS2812C")
      (footprint "LED_5050-SMD_4P-WS2812")
      (fields
        (field (name "BOM_MANUFACTURER PART") "WS2812C")
        (field (name "BOM_SUPPLIER PART") "C114587")
        (field (name "CONTRIBUTOR") "LCSC")
      )
      (libsource (lib "LTC_Library1") (part "RGB_WS2812C"))
    )
    (comp (ref "LED222")
      (value "RGB_WS2812C")
      (footprint "LED_5050-SMD_4P-WS2812")
      (fields
        (field (name "BOM_MANUFACTURER PART") "WS2812C")
        (field (name "BOM_SUPPLIER PART") "C114587")
        (field (name "CONTRIBUTOR") "LCSC")
      )
      (libsource (lib "LTC_Library1") (part "RGB_WS2812C"))
    )
    (comp (ref "LED223")
      (value "RGB_WS2812C")
      (footprint "LED_5050-SMD_4P-WS2812")
      (fields
        (field (name "BOM_MANUFACTURER PART") "WS2812C")
        (field (name "BOM_SUPPLIER PART") "C114587")
        (field (name "CONTRIBUTOR") "LCSC")
      )
      (libsource (lib "LTC_Library1") (part "RGB_WS2812C"))
    )
    (comp (ref "LED224")
      (value "RGB_WS2812C")
      (footprint "LED_5050-SMD_4P-WS2812")
      (fields
        (field (name "BOM_MANUFACTURER PART") "WS2812C")
        (field (name "BOM_SUPPLIER PART") "C114587")
        (field (name "CONTRIBUTOR") "LCSC")
      )
      (libsource (lib "LTC_Library1") (part "RGB_WS2812C"))
    )
    (comp (ref "LED225")
      (value "RGB_WS2812C")
      (footprint "LED_5050-SMD_4P-WS2812")
      (fields
        (field (name "BOM_MANUFACTURER PART") "WS2812C")
        (field (name "BOM_SUPPLIER PART") "C114587")
        (field (name "CONTRIBUTOR") "LCSC")
      )
      (libsource (lib "LTC_Library1") (part "RGB_WS2812C"))
    )
    (comp (ref "LED226")
      (value "RGB_WS2812C")
      (footprint "LED_5050-SMD_4P-WS2812")
      (fields
        (field (name "BOM_MANUFACTURER PART") "WS2812C")
        (field (name "BOM_SUPPLIER PART") "C114587")
        (field (name "CONTRIBUTOR") "LCSC")
      )
      (libsource (lib "LTC_Library1") (part "RGB_WS2812C"))
    )
    (comp (ref "LED227")
      (value "RGB_WS2812C")
      (footprint "LED_5050-SMD_4P-WS2812")
      (fields
        (field (name "BOM_MANUFACTURER PART") "WS2812C")
        (field (name "BOM_SUPPLIER PART") "C114587")
        (field (name "CONTRIBUTOR") "LCSC")
      )
      (libsource (lib "LTC_Library1") (part "RGB_WS2812C"))
    )
    (comp (ref "LED228")
      (value "RGB_WS2812C")
      (footprint "LED_5050-SMD_4P-WS2812")
      (fields
        (field (name "BOM_MANUFACTURER PART") "WS2812C")
        (field (name "BOM_SUPPLIER PART") "C114587")
        (field (name "CONTRIBUTOR") "LCSC")
      )
      (libsource (lib "LTC_Library1") (part "RGB_WS2812C"))
    )
    (comp (ref "LED229")
      (value "RGB_WS2812C")
      (footprint "LED_5050-SMD_4P-WS2812")
      (fields
        (field (name "BOM_MANUFACTURER PART") "WS2812C")
        (field (name "BOM_SUPPLIER PART") "C114587")
        (field (name "CONTRIBUTOR") "LCSC")
      )
      (libsource (lib "LTC_Library1") (part "RGB_WS2812C"))
    )
    (comp (ref "LED230")
      (value "RGB_WS2812C")
      (footprint "LED_5050-SMD_4P-WS2812")
      (fields
        (field (name "BOM_MANUFACTURER PART") "WS2812C")
        (field (name "BOM_SUPPLIER PART") "C114587")
        (field (name "CONTRIBUTOR") "LCSC")
      )
      (libsource (lib "LTC_Library1") (part "RGB_WS2812C"))
    )
    (comp (ref "LED231")
      (value "RGB_WS2812C")
      (footprint "LED_5050-SMD_4P-WS2812")
      (fields
        (field (name "BOM_MANUFACTURER PART") "WS2812C")
        (field (name "BOM_SUPPLIER PART") "C114587")
        (field (name "CONTRIBUTOR") "LCSC")
      )
      (libsource (lib "LTC_Library1") (part "RGB_WS2812C"))
    )
    (comp (ref "LED232")
      (value "RGB_WS2812C")
      (footprint "LED_5050-SMD_4P-WS2812")
      (fields
        (field (name "BOM_MANUFACTURER PART") "WS2812C")
        (field (name "BOM_SUPPLIER PART") "C114587")
        (field (name "CONTRIBUTOR") "LCSC")
      )
      (libsource (lib "LTC_Library1") (part "RGB_WS2812C"))
    )
    (comp (ref "LED233")
      (value "RGB_WS2812C")
      (footprint "LED_5050-SMD_4P-WS2812")
      (fields
        (field (name "BOM_MANUFACTURER PART") "WS2812C")
        (field (name "BOM_SUPPLIER PART") "C114587")
        (field (name "CONTRIBUTOR") "LCSC")
      )
      (libsource (lib "LTC_Library1") (part "RGB_WS2812C"))
    )
    (comp (ref "LED234")
      (value "RGB_WS2812C")
      (footprint "LED_5050-SMD_4P-WS2812")
      (fields
        (field (name "BOM_MANUFACTURER PART") "WS2812C")
        (field (name "BOM_SUPPLIER PART") "C114587")
        (field (name "CONTRIBUTOR") "LCSC")
      )
      (libsource (lib "LTC_Library1") (part "RGB_WS2812C"))
    )
    (comp (ref "LED235")
      (value "RGB_WS2812C")
      (footprint "LED_5050-SMD_4P-WS2812")
      (fields
        (field (name "BOM_MANUFACTURER PART") "WS2812C")
        (field (name "BOM_SUPPLIER PART") "C114587")
        (field (name "CONTRIBUTOR") "LCSC")
      )
      (libsource (lib "LTC_Library1") (part "RGB_WS2812C"))
    )
    (comp (ref "LED236")
      (value "RGB_WS2812C")
      (footprint "LED_5050-SMD_4P-WS2812")
      (fields
        (field (name "BOM_MANUFACTURER PART") "WS2812C")
        (field (name "BOM_SUPPLIER PART") "C114587")
        (field (name "CONTRIBUTOR") "LCSC")
      )
      (libsource (lib "LTC_Library1") (part "RGB_WS2812C"))
    )
    (comp (ref "LED237")
      (value "RGB_WS2812C")
      (footprint "LED_5050-SMD_4P-WS2812")
      (fields
        (field (name "BOM_MANUFACTURER PART") "WS2812C")
        (field (name "BOM_SUPPLIER PART") "C114587")
        (field (name "CONTRIBUTOR") "LCSC")
      )
      (libsource (lib "LTC_Library1") (part "RGB_WS2812C"))
    )
    (comp (ref "LED238")
      (value "RGB_WS2812C")
      (footprint "LED_5050-SMD_4P-WS2812")
      (fields
        (field (name "BOM_MANUFACTURER PART") "WS2812C")
        (field (name "BOM_SUPPLIER PART") "C114587")
        (field (name "CONTRIBUTOR") "LCSC")
      )
      (libsource (lib "LTC_Library1") (part "RGB_WS2812C"))
    )
    (comp (ref "LED239")
      (value "RGB_WS2812C")
      (footprint "LED_5050-SMD_4P-WS2812")
      (fields
        (field (name "BOM_MANUFACTURER PART") "WS2812C")
        (field (name "BOM_SUPPLIER PART") "C114587")
        (field (name "CONTRIBUTOR") "LCSC")
      )
      (libsource (lib "LTC_Library1") (part "RGB_WS2812C"))
    )
    (comp (ref "LED240")
      (value "RGB_WS2812C")
      (footprint "LED_5050-SMD_4P-WS2812")
      (fields
        (field (name "BOM_MANUFACTURER PART") "WS2812C")
        (field (name "BOM_SUPPLIER PART") "C114587")
        (field (name "CONTRIBUTOR") "LCSC")
      )
      (libsource (lib "LTC_Library1") (part "RGB_WS2812C"))
    )
    (comp (ref "LED241")
      (value "RGB_WS2812C")
      (footprint "LED_5050-SMD_4P-WS2812")
      (fields
        (field (name "BOM_MANUFACTURER PART") "WS2812C")
        (field (name "BOM_SUPPLIER PART") "C114587")
        (field (name "CONTRIBUTOR") "LCSC")
      )
      (libsource (lib "LTC_Library1") (part "RGB_WS2812C"))
    )
    (comp (ref "LED242")
      (value "RGB_WS2812C")
      (footprint "LED_5050-SMD_4P-WS2812")
      (fields
        (field (name "BOM_MANUFACTURER PART") "WS2812C")
        (field (name "BOM_SUPPLIER PART") "C114587")
        (field (name "CONTRIBUTOR") "LCSC")
      )
      (libsource (lib "LTC_Library1") (part "RGB_WS2812C"))
    )
    (comp (ref "LED243")
      (value "RGB_WS2812C")
      (footprint "LED_5050-SMD_4P-WS2812")
      (fields
        (field (name "BOM_MANUFACTURER PART") "WS2812C")
        (field (name "BOM_SUPPLIER PART") "C114587")
        (field (name "CONTRIBUTOR") "LCSC")
      )
      (libsource (lib "LTC_Library1") (part "RGB_WS2812C"))
    )
    (comp (ref "LED244")
      (value "RGB_WS2812C")
      (footprint "LED_5050-SMD_4P-WS2812")
      (fields
        (field (name "BOM_MANUFACTURER PART") "WS2812C")
        (field (name "BOM_SUPPLIER PART") "C114587")
        (field (name "CONTRIBUTOR") "LCSC")
      )
      (libsource (lib "LTC_Library1") (part "RGB_WS2812C"))
    )
    (comp (ref "LED245")
      (value "RGB_WS2812C")
      (footprint "LED_5050-SMD_4P-WS2812")
      (fields
        (field (name "BOM_MANUFACTURER PART") "WS2812C")
        (field (name "BOM_SUPPLIER PART") "C114587")
        (field (name "CONTRIBUTOR") "LCSC")
      )
      (libsource (lib "LTC_Library1") (part "RGB_WS2812C"))
    )
    (comp (ref "LED246")
      (value "RGB_WS2812C")
      (footprint "LED_5050-SMD_4P-WS2812")
      (fields
        (field (name "BOM_MANUFACTURER PART") "WS2812C")
        (field (name "BOM_SUPPLIER PART") "C114587")
        (field (name "CONTRIBUTOR") "LCSC")
      )
      (libsource (lib "LTC_Library1") (part "RGB_WS2812C"))
    )
    (comp (ref "LED247")
      (value "RGB_WS2812C")
      (footprint "LED_5050-SMD_4P-WS2812")
      (fields
        (field (name "BOM_MANUFACTURER PART") "WS2812C")
        (field (name "BOM_SUPPLIER PART") "C114587")
        (field (name "CONTRIBUTOR") "LCSC")
      )
      (libsource (lib "LTC_Library1") (part "RGB_WS2812C"))
    )
    (comp (ref "LED248")
      (value "RGB_WS2812C")
      (footprint "LED_5050-SMD_4P-WS2812")
      (fields
        (field (name "BOM_MANUFACTURER PART") "WS2812C")
        (field (name "BOM_SUPPLIER PART") "C114587")
        (field (name "CONTRIBUTOR") "LCSC")
      )
      (libsource (lib "LTC_Library1") (part "RGB_WS2812C"))
    )
    (comp (ref "LED249")
      (value "RGB_WS2812C")
      (footprint "LED_5050-SMD_4P-WS2812")
      (fields
        (field (name "BOM_MANUFACTURER PART") "WS2812C")
        (field (name "BOM_SUPPLIER PART") "C114587")
        (field (name "CONTRIBUTOR") "LCSC")
      )
      (libsource (lib "LTC_Library1") (part "RGB_WS2812C"))
    )
    (comp (ref "LED250")
      (value "RGB_WS2812C")
      (footprint "LED_5050-SMD_4P-WS2812")
      (fields
        (field (name "BOM_MANUFACTURER PART") "WS2812C")
        (field (name "BOM_SUPPLIER PART") "C114587")
        (field (name "CONTRIBUTOR") "LCSC")
      )
      (libsource (lib "LTC_Library1") (part "RGB_WS2812C"))
    )
    (comp (ref "LED251")
      (value "RGB_WS2812C")
      (footprint "LED_5050-SMD_4P-WS2812")
      (fields
        (field (name "BOM_MANUFACTURER PART") "WS2812C")
        (field (name "BOM_SUPPLIER PART") "C114587")
        (field (name "CONTRIBUTOR") "LCSC")
      )
      (libsource (lib "LTC_Library1") (part "RGB_WS2812C"))
    )
    (comp (ref "LED252")
      (value "RGB_WS2812C")
      (footprint "LED_5050-SMD_4P-WS2812")
      (fields
        (field (name "BOM_MANUFACTURER PART") "WS2812C")
        (field (name "BOM_SUPPLIER PART") "C114587")
        (field (name "CONTRIBUTOR") "LCSC")
      )
      (libsource (lib "LTC_Library1") (part "RGB_WS2812C"))
    )
    (comp (ref "LED253")
      (value "RGB_WS2812C")
      (footprint "LED_5050-SMD_4P-WS2812")
      (fields
        (field (name "BOM_MANUFACTURER PART") "WS2812C")
        (field (name "BOM_SUPPLIER PART") "C114587")
        (field (name "CONTRIBUTOR") "LCSC")
      )
      (libsource (lib "LTC_Library1") (part "RGB_WS2812C"))
    )
    (comp (ref "LED254")
      (value "RGB_WS2812C")
      (footprint "LED_5050-SMD_4P-WS2812")
      (fields
        (field (name "BOM_MANUFACTURER PART") "WS2812C")
        (field (name "BOM_SUPPLIER PART") "C114587")
        (field (name "CONTRIBUTOR") "LCSC")
      )
      (libsource (lib "LTC_Library1") (part "RGB_WS2812C"))
    )
    (comp (ref "LED255")
      (value "RGB_WS2812C")
      (footprint "LED_5050-SMD_4P-WS2812")
      (fields
        (field (name "BOM_MANUFACTURER PART") "WS2812C")
        (field (name "BOM_SUPPLIER PART") "C114587")
        (field (name "CONTRIBUTOR") "LCSC")
      )
      (libsource (lib "LTC_Library1") (part "RGB_WS2812C"))
    )
    (comp (ref "LED256")
      (value "RGB_WS2812C")
      (footprint "LED_5050-SMD_4P-WS2812")
      (fields
        (field (name "BOM_MANUFACTURER PART") "WS2812C")
        (field (name "BOM_SUPPLIER PART") "C114587")
        (field (name "CONTRIBUTOR") "LCSC")
      )
      (libsource (lib "LTC_Library1") (part "RGB_WS2812C"))
    )
  )
  (nets
    (net (code "1") (name "/Dout1") (class "Default")
      (node (ref "LED16") (pin "2") (pinfunction "DOUT_2") (pintype "passive"))
      (node (ref "LED17") (pin "4") (pinfunction "DIN_4") (pintype "passive"))
    )
    (net (code "2") (name "/Dout2") (class "Default")
      (node (ref "LED32") (pin "2") (pinfunction "DOUT_2") (pintype "passive"))
      (node (ref "LED33") (pin "4") (pinfunction "DIN_4") (pintype "passive"))
    )
    (net (code "3") (name "/Dout3") (class "Default")
      (node (ref "LED48") (pin "2") (pinfunction "DOUT_2") (pintype "passive"))
      (node (ref "LED49") (pin "4") (pinfunction "DIN_4") (pintype "passive"))
    )
    (net (code "4") (name "/Dout4") (class "Default")
      (node (ref "LED64") (pin "2") (pinfunction "DOUT_2") (pintype "passive"))
      (node (ref "LED65") (pin "4") (pinfunction "DIN_4") (pintype "passive"))
    )
    (net (code "5") (name "/Dout5") (class "Default")
      (node (ref "LED80") (pin "2") (pinfunction "DOUT_2") (pintype "passive"))
      (node (ref "LED81") (pin "4") (pinfunction "DIN_4") (pintype "passive"))
    )
    (net (code "6") (name "/Dout6") (class "Default")
      (node (ref "LED96") (pin "2") (pinfunction "DOUT_2") (pintype "passive"))
      (node (ref "LED97") (pin "4") (pinfunction "DIN_4") (pintype "passive"))
    )
    (net (code "7") (name "/Dout7") (class "Default")
      (node (ref "LED112") (pin "2") (pinfunction "DOUT_2") (pintype "passive"))
      (node (ref "LED113") (pin "4") (pinfunction "DIN_4") (pintype "passive"))
    )
    (net (code "8") (name "/Dout8") (class "Default")
      (node (ref "LED128") (pin "2") (pinfunction "DOUT_2") (pintype "passive"))
      (node (ref "LED129") (pin "4") (pinfunction "DIN_4") (pintype "passive"))
    )
    (net (code "9") (name "/Dout9") (class "Default")
      (node (ref "LED144") (pin "2") (pinfunction "DOUT_2") (pintype "passive"))
      (node (ref "LED145") (pin "4") (pinfunction "DIN_4") (pintype "passive"))
    )
    (net (code "10") (name "/Dout10") (class "Default")
      (node (ref "LED160") (pin "2") (pinfunction "DOUT_2") (pintype "passive"))
      (node (ref "LED161") (pin "4") (pinfunction "DIN_4") (pintype "passive"))
    )
    (net (code "11") (name "/Dout11") (class "Default")
      (node (ref "LED176") (pin "2") (pinfunction "DOUT_2") (pintype "passive"))
      (node (ref "LED177") (pin "4") (pinfunction "DIN_4") (pintype "passive"))
    )
    (net (code "12") (name "/Dout12") (class "Default")
      (node (ref "LED192") (pin "2") (pinfunction "DOUT_2") (pintype "passive"))
      (node (ref "LED193") (pin "4") (pinfunction "DIN_4") (pintype "passive"))
    )
    (net (code "13") (name "/Dout13") (class "Default")
      (node (ref "LED208") (pin "2") (pinfunction "DOUT_2") (pintype "passive"))
      (node (ref "LED209") (pin "4") (pinfunction "DIN_4") (pintype "passive"))
    )
    (net (code "14") (name "/Dout14") (class "Default")
      (node (ref "LED224") (pin "2") (pinfunction "DOUT_2") (pintype "passive"))
      (node (ref "LED225") (pin "4") (pinfunction "DIN_4") (pintype "passive"))
    )
    (net (code "15") (name "/Dout15") (class "Default")
      (node (ref "LED240") (pin "2") (pinfunction "DOUT_2") (pintype "passive"))
      (node (ref "LED241") (pin "4") (pinfunction "DIN_4") (pintype "passive"))
    )
    (net (code "16") (name "DIN") (class "Default")
      (node (ref "LED1") (pin "4") (pinfunction "DIN_4") (pintype "passive"))
    )
    (net (code "17") (name "GND") (class "Default")
      (node (ref "LED1") (pin "3") (pinfunction "VSS_3") (pintype "passive"))
      (node (ref "LED10") (pin "3") (pinfunction "VSS_3") (pintype "passive"))
      (node (ref "LED100") (pin "3") (pinfunction "VSS_3") (pintype "passive"))
      (node (ref "LED101") (pin "3") (pinfunction "VSS_3") (pintype "passive"))
      (node (ref "LED102") (pin "3") (pinfunction "VSS_3") (pintype "passive"))
      (node (ref "LED103") (pin "3") (pinfunction "VSS_3") (pintype "passive"))
      (node (ref "LED104") (pin "3") (pinfunction "VSS_3") (pintype "passive"))
      (node (ref "LED105") (pin "3") (pinfunction "VSS_3") (pintype "passive"))
      (node (ref "LED106") (pin "3") (pinfunction "VSS_3") (pintype "passive"))
      (node (ref "LED107") (pin "3") (pinfunction "VSS_3") (pintype "passive"))
      (node (ref "LED108") (pin "3") (pinfunction "VSS_3") (pintype "passive"))
      (node (ref "LED109") (pin "3") (pinfunction "VSS_3") (pintype "passive"))
      (node (ref "LED11") (pin "3") (pinfunction "VSS_3") (pintype "passive"))
      (node (ref "LED110") (pin "3") (pinfunction "VSS_3") (pintype "passive"))
      (node (ref "LED111") (pin "3") (pinfunction "VSS_3") (pintype "passive"))
      (node (ref "LED112") (pin "3") (pinfunction "VSS_3") (pintype "passive"))
      (node (ref "LED113") (pin "3") (pinfunction "VSS_3") (pintype "passive"))
      (node (ref "LED114") (pin "3") (pinfunction "VSS_3") (pintype "passive"))
      (node (ref "LED115") (pin "3") (pinfunction "VSS_3") (pintype "passive"))
      (node (ref "LED116") (pin "3") (pinfunction "VSS_3") (pintype "passive"))
      (node (ref "LED117") (pin "3") (pinfunction "VSS_3") (pintype "passive"))
      (node (ref "LED118") (pin "3") (pinfunction "VSS_3") (pintype "passive"))
      (node (ref "LED119") (pin "3") (pinfunction "VSS_3") (pintype "passive"))
      (node (ref "LED12") (pin "3") (pinfunction "VSS_3") (pintype "passive"))
      (node (ref "LED120") (pin "3") (pinfunction "VSS_3") (pintype "passive"))
      (node (ref "LED121") (pin "3") (pinfunction "VSS_3") (pintype "passive"))
      (node (ref "LED122") (pin "3") (pinfunction "VSS_3") (pintype "passive"))
      (node (ref "LED123") (pin "3") (pinfunction "VSS_3") (pintype "passive"))
      (node (ref "LED124") (pin "3") (pinfunction "VSS_3") (pintype "passive"))
      (node (ref "LED125") (pin "3") (pinfunction "VSS_3") (pintype "passive"))
      (node (ref "LED126") (pin "3") (pinfunction "VSS_3") (pintype "passive"))
      (node (ref "LED127") (pin "3") (pinfunction "VSS_3") (pintype "passive"))
      (node (ref "LED128") (pin "3") (pinfunction "VSS_3") (pintype "passive"))
      (node (ref "LED129") (pin "3") (pinfunction "VSS_3") (pintype "passive"))
      (node (ref "LED13") (pin "3") (pinfunction "VSS_3") (pintype "passive"))
      (node (ref "LED130") (pin "3") (pinfunction "VSS_3") (pintype "passive"))
      (node (ref "LED131") (pin "3") (pinfunction "VSS_3") (pintype "passive"))
      (node (ref "LED132") (pin "3") (pinfunction "VSS_3") (pintype "passive"))
      (node (ref "LED133") (pin "3") (pinfunction "VSS_3") (pintype "passive"))
      (node (ref "LED134") (pin "3") (pinfunction "VSS_3") (pintype "passive"))
      (node (ref "LED135") (pin "3") (pinfunction "VSS_3") (pintype "passive"))
      (node (ref "LED136") (pin "3") (pinfunction "VSS_3") (pintype "passive"))
      (node (ref "LED137") (pin "3") (pinfunction "VSS_3") (pintype "passive"))
      (node (ref "LED138") (pin "3") (pinfunction "VSS_3") (pintype "passive"))
      (node (ref "LED139") (pin "3") (pinfunction "VSS_3") (pintype "passive"))
      (node (ref "LED14") (pin "3") (pinfunction "VSS_3") (pintype "passive"))
      (node (ref "LED140") (pin "3") (pinfunction "VSS_3") (pintype "passive"))
      (node (ref "LED141") (pin "3") (pinfunction "VSS_3") (pintype "passive"))
      (node (ref "LED142") (pin "3") (pinfunction "VSS_3") (pintype "passive"))
      (node (ref "LED143") (pin "3") (pinfunction "VSS_3") (pintype "passive"))
      (node (ref "LED144") (pin "3") (pinfunction "VSS_3") (pintype "passive"))
      (node (ref "LED145") (pin "3") (pinfunction "VSS_3") (pintype "passive"))
      (node (ref "LED146") (pin "3") (pinfunction "VSS_3") (pintype "passive"))
      (node (ref "LED147") (pin "3") (pinfunction "VSS_3") (pintype "passive"))
      (node (ref "LED148") (pin "3") (pinfunction "VSS_3") (pintype "passive"))
      (node (ref "LED149") (pin "3") (pinfunction "VSS_3") (pintype "passive"))
      (node (ref "LED15") (pin "3") (pinfunction "VSS_3") (pintype "passive"))
      (node (ref "LED150") (pin "3") (pinfunction "VSS_3") (pintype "passive"))
      (node (ref "LED151") (pin "3") (pinfunction "VSS_3") (pintype "passive"))
      (node (ref "LED152") (pin "3") (pinfunction "VSS_3") (pintype "passive"))
      (node (ref "LED153") (pin "3") (pinfunction "VSS_3") (pintype "passive"))
      (node (ref "LED154") (pin "3") (pinfunction "VSS_3") (pintype "passive"))
      (node (ref "LED155") (pin "3") (pinfunction "VSS_3") (pintype "passive"))
      (node (ref "LED156") (pin "3") (pinfunction "VSS_3") (pintype "passive"))
      (node (ref "LED157") (pin "3") (pinfunction "VSS_3") (pintype "passive"))
      (node (ref "LED158") (pin "3") (pinfunction "VSS_3") (pintype "passive"))
      (node (ref "LED159") (pin "3") (pinfunction "VSS_3") (pintype "passive"))
      (node (ref "LED16") (pin "3") (pinfunction "VSS_3") (pintype "passive"))
      (node (ref "LED160") (pin "3") (pinfunction "VSS_3") (pintype "passive"))
      (node (ref "LED161") (pin "3") (pinfunction "VSS_3") (pintype "passive"))
      (node (ref "LED162") (pin "3") (pinfunction "VSS_3") (pintype "passive"))
      (node (ref "LED163") (pin "3") (pinfunction "VSS_3") (pintype "passive"))
      (node (ref "LED164") (pin "3") (pinfunction "VSS_3") (pintype "passive"))
      (node (ref "LED165") (pin "3") (pinfunction "VSS_3") (pintype "passive"))
      (node (ref "LED166") (pin "3") (pinfunction "VSS_3") (pintype "passive"))
      (node (ref "LED167") (pin "3") (pinfunction "VSS_3") (pintype "passive"))
      (node (ref "LED168") (pin "3") (pinfunction "VSS_3") (pintype "passive"))
      (node (ref "LED169") (pin "3") (pinfunction "VSS_3") (pintype "passive"))
      (node (ref "LED17") (pin "3") (pinfunction "VSS_3") (pintype "passive"))
      (node (ref "LED170") (pin "3") (pinfunction "VSS_3") (pintype "passive"))
      (node (ref "LED171") (pin "3") (pinfunction "VSS_3") (pintype "passive"))
      (node (ref "LED172") (pin "3") (pinfunction "VSS_3") (pintype "passive"))
      (node (ref "LED173") (pin "3") (pinfunction "VSS_3") (pintype "passive"))
      (node (ref "LED174") (pin "3") (pinfunction "VSS_3") (pintype "passive"))
      (node (ref "LED175") (pin "3") (pinfunction "VSS_3") (pintype "passive"))
      (node (ref "LED176") (pin "3") (pinfunction "VSS_3") (pintype "passive"))
      (node (ref "LED177") (pin "3") (pinfunction "VSS_3") (pintype "passive"))
      (node (ref "LED178") (pin "3") (pinfunction "VSS_3") (pintype "passive"))
      (node (ref "LED179") (pin "3") (pinfunction "VSS_3") (pintype "passive"))
      (node (ref "LED18") (pin "3") (pinfunction "VSS_3") (pintype "passive"))
      (node (ref "LED180") (pin "3") (pinfunction "VSS_3") (pintype "passive"))
      (node (ref "LED181") (pin "3") (pinfunction "VSS_3") (pintype "passive"))
      (node (ref "LED182") (pin "3") (pinfunction "VSS_3") (pintype "passive"))
      (node (ref "LED183") (pin "3") (pinfunction "VSS_3") (pintype "passive"))
      (node (ref "LED184") (pin "3") (pinfunction "VSS_3") (pintype "passive"))
      (node (ref "LED185") (pin "3") (pinfunction "VSS_3") (pintype "passive"))
      (node (ref "LED186") (pin "3") (pinfunction "VSS_3") (pintype "passive"))
      (node (ref "LED187") (pin "3") (pinfunction "VSS_3") (pintype "passive"))
      (node (ref "LED188") (pin "3") (pinfunction "VSS_3") (pintype "passive"))
      (node (ref "LED189") (pin "3") (pinfunction "VSS_3") (pintype "passive"))
      (node (ref "LED19") (pin "3") (pinfunction "VSS_3") (pintype "passive"))
      (node (ref "LED190") (pin "3") (pinfunction "VSS_3") (pintype "passive"))
      (node (ref "LED191") (pin "3") (pinfunction "VSS_3") (pintype "passive"))
      (node (ref "LED192") (pin "3") (pinfunction "VSS_3") (pintype "passive"))
      (node (ref "LED193") (pin "3") (pinfunction "VSS_3") (pintype "passive"))
      (node (ref "LED194") (pin "3") (pinfunction "VSS_3") (pintype "passive"))
      (node (ref "LED195") (pin "3") (pinfunction "VSS_3") (pintype "passive"))
      (node (ref "LED196") (pin "3") (pinfunction "VSS_3") (pintype "passive"))
      (node (ref "LED197") (pin "3") (pinfunction "VSS_3") (pintype "passive"))
      (node (ref "LED198") (pin "3") (pinfunction "VSS_3") (pintype "passive"))
      (node (ref "LED199") (pin "3") (pinfunction "VSS_3") (pintype "passive"))
      (node (ref "LED2") (pin "3") (pinfunction "VSS_3") (pintype "passive"))
      (node (ref "LED20") (pin "3") (pinfunction "VSS_3") (pintype "passive"))
      (node (ref "LED200") (pin "3") (pinfunction "VSS_3") (pintype "passive"))
      (node (ref "LED201") (pin "3") (pinfunction "VSS_3") (pintype "passive"))
      (node (ref "LED202") (pin "3") (pinfunction "VSS_3") (pintype "passive"))
      (node (ref "LED203") (pin "3") (pinfunction "VSS_3") (pintype "passive"))
      (node (ref "LED204") (pin "3") (pinfunction "VSS_3") (pintype "passive"))
      (node (ref "LED205") (pin "3") (pinfunction "VSS_3") (pintype "passive"))
      (node (ref "LED206") (pin "3") (pinfunction "VSS_3") (pintype "passive"))
      (node (ref "LED207") (pin "3") (pinfunction "VSS_3") (pintype "passive"))
      (node (ref "LED208") (pin "3") (pinfunction "VSS_3") (pintype "passive"))
      (node (ref "LED209") (pin "3") (pinfunction "VSS_3") (pintype "passive"))
      (node (ref "LED21") (pin "3") (pinfunction "VSS_3") (pintype "passive"))
      (node (ref "LED210") (pin "3") (pinfunction "VSS_3") (pintype "passive"))
      (node (ref "LED211") (pin "3") (pinfunction "VSS_3") (pintype "passive"))
      (node (ref "LED212") (pin "3") (pinfunction "VSS_3") (pintype "passive"))
      (node (ref "LED213") (pin "3") (pinfunction "VSS_3") (pintype "passive"))
      (node (ref "LED214") (pin "3") (pinfunction "VSS_3") (pintype "passive"))
      (node (ref "LED215") (pin "3") (pinfunction "VSS_3") (pintype "passive"))
      (node (ref "LED216") (pin "3") (pinfunction "VSS_3") (pintype "passive"))
      (node (ref "LED217") (pin "3") (pinfunction "VSS_3") (pintype "passive"))
      (node (ref "LED218") (pin "3") (pinfunction "VSS_3") (pintype "passive"))
      (node (ref "LED219") (pin "3") (pinfunction "VSS_3") (pintype "passive"))
      (node (ref "LED22") (pin "3") (pinfunction "VSS_3") (pintype "passive"))
      (node (ref "LED220") (pin "3") (pinfunction "VSS_3") (pintype "passive"))
      (node (ref "LED221") (pin "3") (pinfunction "VSS_3") (pintype "passive"))
      (node (ref "LED222") (pin "3") (pinfunction "VSS_3") (pintype "passive"))
      (node (ref "LED223") (pin "3") (pinfunction "VSS_3") (pintype "passive"))
      (node (ref "LED224") (pin "3") (pinfunction "VSS_3") (pintype "passive"))
      (node (ref "LED225") (pin "3") (pinfunction "VSS_3") (pintype "passive"))
      (node (ref "LED226") (pin "3") (pinfunction "VSS_3") (pintype "passive"))
      (node (ref "LED227") (pin "3") (pinfunction "VSS_3") (pintype "passive"))
      (node (ref "LED228") (pin "3") (pinfunction "VSS_3") (pintype "passive"))
      (node (ref "LED229") (pin "3") (pinfunction "VSS_3") (pintype "passive"))
      (node (ref "LED23") (pin "3") (pinfunction "VSS_3") (pintype "passive"))
      (node (ref "LED230") (pin "3") (pinfunction "VSS_3") (pintype "passive"))
      (node (ref "LED231") (pin "3") (pinfunction "VSS_3") (pintype "passive"))
      (node (ref "LED232") (pin "3") (pinfunction "VSS_3") (pintype "passive"))
      (node (ref "LED233") (pin "3") (pinfunction "VSS_3") (pintype "passive"))
      (node (ref "LED234") (pin "3") (pinfunction "VSS_3") (pintype "passive"))
      (node (ref "LED235") (pin "3") (pinfunction "VSS_3") (pintype "passive"))
      (node (ref "LED236") (pin "3") (pinfunction "VSS_3") (pintype "passive"))
      (node (ref "LED237") (pin "3") (pinfunction "VSS_3") (pintype "passive"))
      (node (ref "LED238") (pin "3") (pinfunction "VSS_3") (pintype "passive"))
      (node (ref "LED239") (pin "3") (pinfunction "VSS_3") (pintype "passive"))
      (node (ref "LED24") (pin "3") (pinfunction "VSS_3") (pintype "passive"))
      (node (ref "LED240") (pin "3") (pinfunction "VSS_3") (pintype "passive"))
      (node (ref "LED241") (pin "3") (pinfunction "VSS_3") (pintype "passive"))
      (node (ref "LED242") (pin "3") (pinfunction "VSS_3") (pintype "passive"))
      (node (ref "LED243") (pin "3") (pinfunction "VSS_3") (pintype "passive"))
      (node (ref "LED244") (pin "3") (pinfunction "VSS_3") (pintype "passive"))
      (node (ref "LED245") (pin "3") (pinfunction "VSS_3") (pintype "passive"))
      (node (ref "LED246") (pin "3") (pinfunction "VSS_3") (pintype "passive"))
      (node (ref "LED247") (pin "3") (pinfunction "VSS_3") (pintype "passive"))
      (node (ref "LED248") (pin "3") (pinfunction "VSS_3") (pintype "passive"))
      (node (ref "LED249") (pin "3") (pinfunction "VSS_3") (pintype "passive"))
      (node (ref "LED25") (pin "3") (pinfunction "VSS_3") (pintype "passive"))
      (node (ref "LED250") (pin "3") (pinfunction "VSS_3") (pintype "passive"))
      (node (ref "LED251") (pin "3") (pinfunction "VSS_3") (pintype "passive"))
      (node (ref "LED252") (pin "3") (pinfunction "VSS_3") (pintype "passive"))
      (node (ref "LED253") (pin "3") (pinfunction "VSS_3") (pintype "passive"))
      (node (ref "LED254") (pin "3") (pinfunction "VSS_3") (pintype "passive"))
      (node (ref "LED255") (pin "3") (pinfunction "VSS_3") (pintype "passive"))
      (node (ref "LED256") (pin "3") (pinfunction "VSS_3") (pintype "passive"))
      (node (ref "LED26") (pin "3") (pinfunction "VSS_3") (pintype "passive"))
      (node (ref "LED27") (pin "3") (pinfunction "VSS_3") (pintype "passive"))
      (node (ref "LED28") (pin "3") (pinfunction "VSS_3") (pintype "passive"))
      (node (ref "LED29") (pin "3") (pinfunction "VSS_3") (pintype "passive"))
      (node (ref "LED3") (pin "3") (pinfunction "VSS_3") (pintype "passive"))
      (node (ref "LED30") (pin "3") (pinfunction "VSS_3") (pintype "passive"))
      (node (ref "LED31") (pin "3") (pinfunction "VSS_3") (pintype "passive"))
      (node (ref "LED32") (pin "3") (pinfunction "VSS_3") (pintype "passive"))
      (node (ref "LED33") (pin "3") (pinfunction "VSS_3") (pintype "passive"))
      (node (ref "LED34") (pin "3") (pinfunction "VSS_3") (pintype "passive"))
      (node (ref "LED35") (pin "3") (pinfunction "VSS_3") (pintype "passive"))
      (node (ref "LED36") (pin "3") (pinfunction "VSS_3") (pintype "passive"))
      (node (ref "LED37") (pin "3") (pinfunction "VSS_3") (pintype "passive"))
      (node (ref "LED38") (pin "3") (pinfunction "VSS_3") (pintype "passive"))
      (node (ref "LED39") (pin "3") (pinfunction "VSS_3") (pintype "passive"))
      (node (ref "LED4") (pin "3") (pinfunction "VSS_3") (pintype "passive"))
      (node (ref "LED40") (pin "3") (pinfunction "VSS_3") (pintype "passive"))
      (node (ref "LED41") (pin "3") (pinfunction "VSS_3") (pintype "passive"))
      (node (ref "LED42") (pin "3") (pinfunction "VSS_3") (pintype "passive"))
      (node (ref "LED43") (pin "3") (pinfunction "VSS_3") (pintype "passive"))
      (node (ref "LED44") (pin "3") (pinfunction "VSS_3") (pintype "passive"))
      (node (ref "LED45") (pin "3") (pinfunction "VSS_3") (pintype "passive"))
      (node (ref "LED46") (pin "3") (pinfunction "VSS_3") (pintype "passive"))
      (node (ref "LED47") (pin "3") (pinfunction "VSS_3") (pintype "passive"))
      (node (ref "LED48") (pin "3") (pinfunction "VSS_3") (pintype "passive"))
      (node (ref "LED49") (pin "3") (pinfunction "VSS_3") (pintype "passive"))
      (node (ref "LED5") (pin "3") (pinfunction "VSS_3") (pintype "passive"))
      (node (ref "LED50") (pin "3") (pinfunction "VSS_3") (pintype "passive"))
      (node (ref "LED51") (pin "3") (pinfunction "VSS_3") (pintype "passive"))
      (node (ref "LED52") (pin "3") (pinfunction "VSS_3") (pintype "passive"))
      (node (ref "LED53") (pin "3") (pinfunction "VSS_3") (pintype "passive"))
      (node (ref "LED54") (pin "3") (pinfunction "VSS_3") (pintype "passive"))
      (node (ref "LED55") (pin "3") (pinfunction "VSS_3") (pintype "passive"))
      (node (ref "LED56") (pin "3") (pinfunction "VSS_3") (pintype "passive"))
      (node (ref "LED57") (pin "3") (pinfunction "VSS_3") (pintype "passive"))
      (node (ref "LED58") (pin "3") (pinfunction "VSS_3") (pintype "passive"))
      (node (ref "LED59") (pin "3") (pinfunction "VSS_3") (pintype "passive"))
      (node (ref "LED6") (pin "3") (pinfunction "VSS_3") (pintype "passive"))
      (node (ref "LED60") (pin "3") (pinfunction "VSS_3") (pintype "passive"))
      (node (ref "LED61") (pin "3") (pinfunction "VSS_3") (pintype "passive"))
      (node (ref "LED62") (pin "3") (pinfunction "VSS_3") (pintype "passive"))
      (node (ref "LED63") (pin "3") (pinfunction "VSS_3") (pintype "passive"))
      (node (ref "LED64") (pin "3") (pinfunction "VSS_3") (pintype "passive"))
      (node (ref "LED65") (pin "3") (pinfunction "VSS_3") (pintype "passive"))
      (node (ref "LED66") (pin "3") (pinfunction "VSS_3") (pintype "passive"))
      (node (ref "LED67") (pin "3") (pinfunction "VSS_3") (pintype "passive"))
      (node (ref "LED68") (pin "3") (pinfunction "VSS_3") (pintype "passive"))
      (node (ref "LED69") (pin "3") (pinfunction "VSS_3") (pintype "passive"))
      (node (ref "LED7") (pin "3") (pinfunction "VSS_3") (pintype "passive"))
      (node (ref "LED70") (pin "3") (pinfunction "VSS_3") (pintype "passive"))
      (node (ref "LED71") (pin "3") (pinfunction "VSS_3") (pintype "passive"))
      (node (ref "LED72") (pin "3") (pinfunction "VSS_3") (pintype "passive"))
      (node (ref "LED73") (pin "3") (pinfunction "VSS_3") (pintype "passive"))
      (node (ref "LED74") (pin "3") (pinfunction "VSS_3") (pintype "passive"))
      (node (ref "LED75") (pin "3") (pinfunction "VSS_3") (pintype "passive"))
      (node (ref "LED76") (pin "3") (pinfunction "VSS_3") (pintype "passive"))
      (node (ref "LED77") (pin "3") (pinfunction "VSS_3") (pintype "passive"))
      (node (ref "LED78") (pin "3") (pinfunction "VSS_3") (pintype "passive"))
      (node (ref "LED79") (pin "3") (pinfunction "VSS_3") (pintype "passive"))
      (node (ref "LED8") (pin "3") (pinfunction "VSS_3") (pintype "passive"))
      (node (ref "LED80") (pin "3") (pinfunction "VSS_3") (pintype "passive"))
      (node (ref "LED81") (pin "3") (pinfunction "VSS_3") (pintype "passive"))
      (node (ref "LED82") (pin "3") (pinfunction "VSS_3") (pintype "passive"))
      (node (ref "LED83") (pin "3") (pinfunction "VSS_3") (pintype "passive"))
      (node (ref "LED84") (pin "3") (pinfunction "VSS_3") (pintype "passive"))
      (node (ref "LED85") (pin "3") (pinfunction "VSS_3") (pintype "passive"))
      (node (ref "LED86") (pin "3") (pinfunction "VSS_3") (pintype "passive"))
      (node (ref "LED87") (pin "3") (pinfunction "VSS_3") (pintype "passive"))
      (node (ref "LED88") (pin "3") (pinfunction "VSS_3") (pintype "passive"))
      (node (ref "LED89") (pin "3") (pinfunction "VSS_3") (pintype "passive"))
      (node (ref "LED9") (pin "3") (pinfunction "VSS_3") (pintype "passive"))
      (node (ref "LED90") (pin "3") (pinfunction "VSS_3") (pintype "passive"))
      (node (ref "LED91") (pin "3") (pinfunction "VSS_3") (pintype "passive"))
      (node (ref "LED92") (pin "3") (pinfunction "VSS_3") (pintype "passive"))
      (node (ref "LED93") (pin "3") (pinfunction "VSS_3") (pintype "passive"))
      (node (ref "LED94") (pin "3") (pinfunction "VSS_3") (pintype "passive"))
      (node (ref "LED95") (pin "3") (pinfunction "VSS_3") (pintype "passive"))
      (node (ref "LED96") (pin "3") (pinfunction "VSS_3") (pintype "passive"))
      (node (ref "LED97") (pin "3") (pinfunction "VSS_3") (pintype "passive"))
      (node (ref "LED98") (pin "3") (pinfunction "VSS_3") (pintype "passive"))
      (node (ref "LED99") (pin "3") (pinfunction "VSS_3") (pintype "passive"))
    )
    (net (code "18") (name "Net-(LED1-DOUT)") (class "Default")
      (node (ref "LED1") (pin "2") (pinfunction "DOUT_2") (pintype "passive"))
      (node (ref "LED2") (pin "4") (pinfunction "DIN_4") (pintype "passive"))
    )
    (net (code "19") (name "Net-(LED2-DOUT)") (class "Default")
      (node (ref "LED2") (pin "2") (pinfunction "DOUT_2") (pintype "passive"))
      (node (ref "LED3") (pin "4") (pinfunction "DIN_4") (pintype "passive"))
    )
    (net (code "20") (name "Net-(LED3-DOUT)") (class "Default")
      (node (ref "LED3") (pin "2") (pinfunction "DOUT_2") (pintype "passive"))
      (node (ref "LED4") (pin "4") (pinfunction "DIN_4") (pintype "passive"))
    )
    (net (code "21") (name "Net-(LED4-DOUT)") (class "Default")
      (node (ref "LED4") (pin "2") (pinfunction "DOUT_2") (pintype "passive"))
      (node (ref "LED5") (pin "4") (pinfunction "DIN_4") (pintype "passive"))
    )
    (net (code "22") (name "Net-(LED5-DOUT)") (class "Default")
      (node (ref "LED5") (pin "2") (pinfunction "DOUT_2") (pintype "passive"))
      (node (ref "LED6") (pin "4") (pinfunction "DIN_4") (pintype "passive"))
    )
    (net (code "23") (name "Net-(LED6-DOUT)") (class "Default")
      (node (ref "LED6") (pin "2") (pinfunction "DOUT_2") (pintype "passive"))
      (node (ref "LED7") (pin "4") (pinfunction "DIN_4") (pintype "passive"))
    )
    (net (code "24") (name "Net-(LED7-DOUT)") (class "Default")
      (node (ref "LED7") (pin "2") (pinfunction "DOUT_2") (pintype "passive"))
      (node (ref "LED8") (pin "4") (pinfunction "DIN_4") (pintype "passive"))
    )
    (net (code "25") (name "Net-(LED8-DOUT)") (class "Default")
      (node (ref "LED8") (pin "2") (pinfunction "DOUT_2") (pintype "passive"))
      (node (ref "LED9") (pin "4") (pinfunction "DIN_4") (pintype "passive"))
    )
    (net (code "26") (name "Net-(LED10-DIN)") (class "Default")
      (node (ref "LED10") (pin "4") (pinfunction "DIN_4") (pintype "passive"))
      (node (ref "LED9") (pin "2") (pinfunction "DOUT_2") (pintype "passive"))
    )
    (net (code "27") (name "Net-(LED10-DOUT)") (class "Default")
      (node (ref "LED10") (pin "2") (pinfunction "DOUT_2") (pintype "passive"))
      (node (ref "LED11") (pin "4") (pinfunction "DIN_4") (pintype "passive"))
    )
    (net (code "28") (name "Net-(LED11-DOUT)") (class "Default")
      (node (ref "LED11") (pin "2") (pinfunction "DOUT_2") (pintype "passive"))
      (node (ref "LED12") (pin "4") (pinfunction "DIN_4") (pintype "passive"))
    )
    (net (code "29") (name "Net-(LED12-DOUT)") (class "Default")
      (node (ref "LED12") (pin "2") (pinfunction "DOUT_2") (pintype "passive"))
      (node (ref "LED13") (pin "4") (pinfunction "DIN_4") (pintype "passive"))
    )
    (net (code "30") (name "Net-(LED13-DOUT)") (class "Default")
      (node (ref "LED13") (pin "2") (pinfunction "DOUT_2") (pintype "passive"))
      (node (ref "LED14") (pin "4") (pinfunction "DIN_4") (pintype "passive"))
    )
    (net (code "31") (name "Net-(LED14-DOUT)") (class "Default")
      (node (ref "LED14") (pin "2") (pinfunction "DOUT_2") (pintype "passive"))
      (node (ref "LED15") (pin "4") (pinfunction "DIN_4") (pintype "passive"))
    )
    (net (code "32") (name "Net-(LED15-DOUT)") (class "Default")
      (node (ref "LED15") (pin "2") (pinfunction "DOUT_2") (pintype "passive"))
      (node (ref "LED16") (pin "4") (pinfunction "DIN_4") (pintype "passive"))
    )
    (net (code "33") (name "Net-(LED17-DOUT)") (class "Default")
      (node (ref "LED17") (pin "2") (pinfunction "DOUT_2") (pintype "passive"))
      (node (ref "LED18") (pin "4") (pinfunction "DIN_4") (pintype "passive"))
    )
    (net (code "34") (name "Net-(LED18-DOUT)") (class "Default")
      (node (ref "LED18") (pin "2") (pinfunction "DOUT_2") (pintype "passive"))
      (node (ref "LED19") (pin "4") (pinfunction "DIN_4") (pintype "passive"))
    )
    (net (code "35") (name "Net-(LED19-DOUT)") (class "Default")
      (node (ref "LED19") (pin "2") (pinfunction "DOUT_2") (pintype "passive"))
      (node (ref "LED20") (pin "4") (pinfunction "DIN_4") (pintype "passive"))
    )
    (net (code "36") (name "Net-(LED20-DOUT)") (class "Default")
      (node (ref "LED20") (pin "2") (pinfunction "DOUT_2") (pintype "passive"))
      (node (ref "LED21") (pin "4") (pinfunction "DIN_4") (pintype "passive"))
    )
    (net (code "37") (name "Net-(LED21-DOUT)") (class "Default")
      (node (ref "LED21") (pin "2") (pinfunction "DOUT_2") (pintype "passive"))
      (node (ref "LED22") (pin "4") (pinfunction "DIN_4") (pintype "passive"))
    )
    (net (code "38") (name "Net-(LED22-DOUT)") (class "Default")
      (node (ref "LED22") (pin "2") (pinfunction "DOUT_2") (pintype "passive"))
      (node (ref "LED23") (pin "4") (pinfunction "DIN_4") (pintype "passive"))
    )
    (net (code "39") (name "Net-(LED23-DOUT)") (class "Default")
      (node (ref "LED23") (pin "2") (pinfunction "DOUT_2") (pintype "passive"))
      (node (ref "LED24") (pin "4") (pinfunction "DIN_4") (pintype "passive"))
    )
    (net (code "40") (name "Net-(LED24-DOUT)") (class "Default")
      (node (ref "LED24") (pin "2") (pinfunction "DOUT_2") (pintype "passive"))
      (node (ref "LED25") (pin "4") (pinfunction "DIN_4") (pintype "passive"))
    )
    (net (code "41") (name "Net-(LED25-DOUT)") (class "Default")
      (node (ref "LED25") (pin "2") (pinfunction "DOUT_2") (pintype "passive"))
      (node (ref "LED26") (pin "4") (pinfunction "DIN_4") (pintype "passive"))
    )
    (net (code "42") (name "Net-(LED26-DOUT)") (class "Default")
      (node (ref "LED26") (pin "2") (pinfunction "DOUT_2") (pintype "passive"))
      (node (ref "LED27") (pin "4") (pinfunction "DIN_4") (pintype "passive"))
    )
    (net (code "43") (name "Net-(LED27-DOUT)") (class "Default")
      (node (ref "LED27") (pin "2") (pinfunction "DOUT_2") (pintype "passive"))
      (node (ref "LED28") (pin "4") (pinfunction "DIN_4") (pintype "passive"))
    )
    (net (code "44") (name "Net-(LED28-DOUT)") (class "Default")
      (node (ref "LED28") (pin "2") (pinfunction "DOUT_2") (pintype "passive"))
      (node (ref "LED29") (pin "4") (pinfunction "DIN_4") (pintype "passive"))
    )
    (net (code "45") (name "Net-(LED29-DOUT)") (class "Default")
      (node (ref "LED29") (pin "2") (pinfunction "DOUT_2") (pintype "passive"))
      (node (ref "LED30") (pin "4") (pinfunction "DIN_4") (pintype "passive"))
    )
    (net (code "46") (name "Net-(LED30-DOUT)") (class "Default")
      (node (ref "LED30") (pin "2") (pinfunction "DOUT_2") (pintype "passive"))
      (node (ref "LED31") (pin "4") (pinfunction "DIN_4") (pintype "passive"))
    )
    (net (code "47") (name "Net-(LED31-DOUT)") (class "Default")
      (node (ref "LED31") (pin "2") (pinfunction "DOUT_2") (pintype "passive"))
      (node (ref "LED32") (pin "4") (pinfunction "DIN_4") (pintype "passive"))
    )
    (net (code "48") (name "Net-(LED33-DOUT)") (class "Default")
      (node (ref "LED33") (pin "2") (pinfunction "DOUT_2") (pintype "passive"))
      (node (ref "LED34") (pin "4") (pinfunction "DIN_4") (pintype "passive"))
    )
    (net (code "49") (name "Net-(LED34-DOUT)") (class "Default")
      (node (ref "LED34") (pin "2") (pinfunction "DOUT_2") (pintype "passive"))
      (node (ref "LED35") (pin "4") (pinfunction "DIN_4") (pintype "passive"))
    )
    (net (code "50") (name "Net-(LED35-DOUT)") (class "Default")
      (node (ref "LED35") (pin "2") (pinfunction "DOUT_2") (pintype "passive"))
      (node (ref "LED36") (pin "4") (pinfunction "DIN_4") (pintype "passive"))
    )
    (net (code "51") (name "Net-(LED36-DOUT)") (class "Default")
      (node (ref "LED36") (pin "2") (pinfunction "DOUT_2") (pintype "passive"))
      (node (ref "LED37") (pin "4") (pinfunction "DIN_4") (pintype "passive"))
    )
    (net (code "52") (name "Net-(LED37-DOUT)") (class "Default")
      (node (ref "LED37") (pin "2") (pinfunction "DOUT_2") (pintype "passive"))
      (node (ref "LED38") (pin "4") (pinfunction "DIN_4") (pintype "passive"))
    )
    (net (code "53") (name "Net-(LED38-DOUT)") (class "Default")
      (node (ref "LED38") (pin "2") (pinfunction "DOUT_2") (pintype "passive"))
      (node (ref "LED39") (pin "4") (pinfunction "DIN_4") (pintype "passive"))
    )
    (net (code "54") (name "Net-(LED39-DOUT)") (class "Default")
      (node (ref "LED39") (pin "2") (pinfunction "DOUT_2") (pintype "passive"))
      (node (ref "LED40") (pin "4") (pinfunction "DIN_4") (pintype "passive"))
    )
    (net (code "55") (name "Net-(LED40-DOUT)") (class "Default")
      (node (ref "LED40") (pin "2") (pinfunction "DOUT_2") (pintype "passive"))
      (node (ref "LED41") (pin "4") (pinfunction "DIN_4") (pintype "passive"))
    )
    (net (code "56") (name "Net-(LED41-DOUT)") (class "Default")
      (node (ref "LED41") (pin "2") (pinfunction "DOUT_2") (pintype "passive"))
      (node (ref "LED42") (pin "4") (pinfunction "DIN_4") (pintype "passive"))
    )
    (net (code "57") (name "Net-(LED42-DOUT)") (class "Default")
      (node (ref "LED42") (pin "2") (pinfunction "DOUT_2") (pintype "passive"))
      (node (ref "LED43") (pin "4") (pinfunction "DIN_4") (pintype "passive"))
    )
    (net (code "58") (name "Net-(LED43-DOUT)") (class "Default")
      (node (ref "LED43") (pin "2") (pinfunction "DOUT_2") (pintype "passive"))
      (node (ref "LED44") (pin "4") (pinfunction "DIN_4") (pintype "passive"))
    )
    (net (code "59") (name "Net-(LED44-DOUT)") (class "Default")
      (node (ref "LED44") (pin "2") (pinfunction "DOUT_2") (pintype "passive"))
      (node (ref "LED45") (pin "4") (pinfunction "DIN_4") (pintype "passive"))
    )
    (net (code "60") (name "Net-(LED45-DOUT)") (class "Default")
      (node (ref "LED45") (pin "2") (pinfunction "DOUT_2") (pintype "passive"))
      (node (ref "LED46") (pin "4") (pinfunction "DIN_4") (pintype "passive"))
    )
    (net (code "61") (name "Net-(LED46-DOUT)") (class "Default")
      (node (ref "LED46") (pin "2") (pinfunction "DOUT_2") (pintype "passive"))
      (node (ref "LED47") (pin "4") (pinfunction "DIN_4") (pintype "passive"))
    )
    (net (code "62") (name "Net-(LED47-DOUT)") (class "Default")
      (node (ref "LED47") (pin "2") (pinfunction "DOUT_2") (pintype "passive"))
      (node (ref "LED48") (pin "4") (pinfunction "DIN_4") (pintype "passive"))
    )
    (net (code "63") (name "Net-(LED49-DOUT)") (class "Default")
      (node (ref "LED49") (pin "2") (pinfunction "DOUT_2") (pintype "passive"))
      (node (ref "LED50") (pin "4") (pinfunction "DIN_4") (pintype "passive"))
    )
    (net (code "64") (name "Net-(LED50-DOUT)") (class "Default")
      (node (ref "LED50") (pin "2") (pinfunction "DOUT_2") (pintype "passive"))
      (node (ref "LED51") (pin "4") (pinfunction "DIN_4") (pintype "passive"))
    )
    (net (code "65") (name "Net-(LED51-DOUT)") (class "Default")
      (node (ref "LED51") (pin "2") (pinfunction "DOUT_2") (pintype "passive"))
      (node (ref "LED52") (pin "4") (pinfunction "DIN_4") (pintype "passive"))
    )
    (net (code "66") (name "Net-(LED52-DOUT)") (class "Default")
      (node (ref "LED52") (pin "2") (pinfunction "DOUT_2") (pintype "passive"))
      (node (ref "LED53") (pin "4") (pinfunction "DIN_4") (pintype "passive"))
    )
    (net (code "67") (name "Net-(LED53-DOUT)") (class "Default")
      (node (ref "LED53") (pin "2") (pinfunction "DOUT_2") (pintype "passive"))
      (node (ref "LED54") (pin "4") (pinfunction "DIN_4") (pintype "passive"))
    )
    (net (code "68") (name "Net-(LED54-DOUT)") (class "Default")
      (node (ref "LED54") (pin "2") (pinfunction "DOUT_2") (pintype "passive"))
      (node (ref "LED55") (pin "4") (pinfunction "DIN_4") (pintype "passive"))
    )
    (net (code "69") (name "Net-(LED55-DOUT)") (class "Default")
      (node (ref "LED55") (pin "2") (pinfunction "DOUT_2") (pintype "passive"))
      (node (ref "LED56") (pin "4") (pinfunction "DIN_4") (pintype "passive"))
    )
    (net (code "70") (name "Net-(LED56-DOUT)") (class "Default")
      (node (ref "LED56") (pin "2") (pinfunction "DOUT_2") (pintype "passive"))
      (node (ref "LED57") (pin "4") (pinfunction "DIN_4") (pintype "passive"))
    )
    (net (code "71") (name "Net-(LED57-DOUT)") (class "Default")
      (node (ref "LED57") (pin "2") (pinfunction "DOUT_2") (pintype "passive"))
      (node (ref "LED58") (pin "4") (pinfunction "DIN_4") (pintype "passive"))
    )
    (net (code "72") (name "Net-(LED58-DOUT)") (class "Default")
      (node (ref "LED58") (pin "2") (pinfunction "DOUT_2") (pintype "passive"))
      (node (ref "LED59") (pin "4") (pinfunction "DIN_4") (pintype "passive"))
    )
    (net (code "73") (name "Net-(LED59-DOUT)") (class "Default")
      (node (ref "LED59") (pin "2") (pinfunction "DOUT_2") (pintype "passive"))
      (node (ref "LED60") (pin "4") (pinfunction "DIN_4") (pintype "passive"))
    )
    (net (code "74") (name "Net-(LED60-DOUT)") (class "Default")
      (node (ref "LED60") (pin "2") (pinfunction "DOUT_2") (pintype "passive"))
      (node (ref "LED61") (pin "4") (pinfunction "DIN_4") (pintype "passive"))
    )
    (net (code "75") (name "Net-(LED61-DOUT)") (class "Default")
      (node (ref "LED61") (pin "2") (pinfunction "DOUT_2") (pintype "passive"))
      (node (ref "LED62") (pin "4") (pinfunction "DIN_4") (pintype "passive"))
    )
    (net (code "76") (name "Net-(LED62-DOUT)") (class "Default")
      (node (ref "LED62") (pin "2") (pinfunction "DOUT_2") (pintype "passive"))
      (node (ref "LED63") (pin "4") (pinfunction "DIN_4") (pintype "passive"))
    )
    (net (code "77") (name "Net-(LED63-DOUT)") (class "Default")
      (node (ref "LED63") (pin "2") (pinfunction "DOUT_2") (pintype "passive"))
      (node (ref "LED64") (pin "4") (pinfunction "DIN_4") (pintype "passive"))
    )
    (net (code "78") (name "Net-(LED65-DOUT)") (class "Default")
      (node (ref "LED65") (pin "2") (pinfunction "DOUT_2") (pintype "passive"))
      (node (ref "LED66") (pin "4") (pinfunction "DIN_4") (pintype "passive"))
    )
    (net (code "79") (name "Net-(LED66-DOUT)") (class "Default")
      (node (ref "LED66") (pin "2") (pinfunction "DOUT_2") (pintype "passive"))
      (node (ref "LED67") (pin "4") (pinfunction "DIN_4") (pintype "passive"))
    )
    (net (code "80") (name "Net-(LED67-DOUT)") (class "Default")
      (node (ref "LED67") (pin "2") (pinfunction "DOUT_2") (pintype "passive"))
      (node (ref "LED68") (pin "4") (pinfunction "DIN_4") (pintype "passive"))
    )
    (net (code "81") (name "Net-(LED68-DOUT)") (class "Default")
      (node (ref "LED68") (pin "2") (pinfunction "DOUT_2") (pintype "passive"))
      (node (ref "LED69") (pin "4") (pinfunction "DIN_4") (pintype "passive"))
    )
    (net (code "82") (name "Net-(LED69-DOUT)") (class "Default")
      (node (ref "LED69") (pin "2") (pinfunction "DOUT_2") (pintype "passive"))
      (node (ref "LED70") (pin "4") (pinfunction "DIN_4") (pintype "passive"))
    )
    (net (code "83") (name "Net-(LED70-DOUT)") (class "Default")
      (node (ref "LED70") (pin "2") (pinfunction "DOUT_2") (pintype "passive"))
      (node (ref "LED71") (pin "4") (pinfunction "DIN_4") (pintype "passive"))
    )
    (net (code "84") (name "Net-(LED71-DOUT)") (class "Default")
      (node (ref "LED71") (pin "2") (pinfunction "DOUT_2") (pintype "passive"))
      (node (ref "LED72") (pin "4") (pinfunction "DIN_4") (pintype "passive"))
    )
    (net (code "85") (name "Net-(LED72-DOUT)") (class "Default")
      (node (ref "LED72") (pin "2") (pinfunction "DOUT_2") (pintype "passive"))
      (node (ref "LED73") (pin "4") (pinfunction "DIN_4") (pintype "passive"))
    )
    (net (code "86") (name "Net-(LED73-DOUT)") (class "Default")
      (node (ref "LED73") (pin "2") (pinfunction "DOUT_2") (pintype "passive"))
      (node (ref "LED74") (pin "4") (pinfunction "DIN_4") (pintype "passive"))
    )
    (net (code "87") (name "Net-(LED74-DOUT)") (class "Default")
      (node (ref "LED74") (pin "2") (pinfunction "DOUT_2") (pintype "passive"))
      (node (ref "LED75") (pin "4") (pinfunction "DIN_4") (pintype "passive"))
    )
    (net (code "88") (name "Net-(LED75-DOUT)") (class "Default")
      (node (ref "LED75") (pin "2") (pinfunction "DOUT_2") (pintype "passive"))
      (node (ref "LED76") (pin "4") (pinfunction "DIN_4") (pintype "passive"))
    )
    (net (code "89") (name "Net-(LED76-DOUT)") (class "Default")
      (node (ref "LED76") (pin "2") (pinfunction "DOUT_2") (pintype "passive"))
      (node (ref "LED77") (pin "4") (pinfunction "DIN_4") (pintype "passive"))
    )
    (net (code "90") (name "Net-(LED77-DOUT)") (class "Default")
      (node (ref "LED77") (pin "2") (pinfunction "DOUT_2") (pintype "passive"))
      (node (ref "LED78") (pin "4") (pinfunction "DIN_4") (pintype "passive"))
    )
    (net (code "91") (name "Net-(LED78-DOUT)") (class "Default")
      (node (ref "LED78") (pin "2") (pinfunction "DOUT_2") (pintype "passive"))
      (node (ref "LED79") (pin "4") (pinfunction "DIN_4") (pintype "passive"))
    )
    (net (code "92") (name "Net-(LED79-DOUT)") (class "Default")
      (node (ref "LED79") (pin "2") (pinfunction "DOUT_2") (pintype "passive"))
      (node (ref "LED80") (pin "4") (pinfunction "DIN_4") (pintype "passive"))
    )
    (net (code "93") (name "Net-(LED81-DOUT)") (class "Default")
      (node (ref "LED81") (pin "2") (pinfunction "DOUT_2") (pintype "passive"))
      (node (ref "LED82") (pin "4") (pinfunction "DIN_4") (pintype "passive"))
    )
    (net (code "94") (name "Net-(LED82-DOUT)") (class "Default")
      (node (ref "LED82") (pin "2") (pinfunction "DOUT_2") (pintype "passive"))
      (node (ref "LED83") (pin "4") (pinfunction "DIN_4") (pintype "passive"))
    )
    (net (code "95") (name "Net-(LED83-DOUT)") (class "Default")
      (node (ref "LED83") (pin "2") (pinfunction "DOUT_2") (pintype "passive"))
      (node (ref "LED84") (pin "4") (pinfunction "DIN_4") (pintype "passive"))
    )
    (net (code "96") (name "Net-(LED84-DOUT)") (class "Default")
      (node (ref "LED84") (pin "2") (pinfunction "DOUT_2") (pintype "passive"))
      (node (ref "LED85") (pin "4") (pinfunction "DIN_4") (pintype "passive"))
    )
    (net (code "97") (name "Net-(LED85-DOUT)") (class "Default")
      (node (ref "LED85") (pin "2") (pinfunction "DOUT_2") (pintype "passive"))
      (node (ref "LED86") (pin "4") (pinfunction "DIN_4") (pintype "passive"))
    )
    (net (code "98") (name "Net-(LED86-DOUT)") (class "Default")
      (node (ref "LED86") (pin "2") (pinfunction "DOUT_2") (pintype "passive"))
      (node (ref "LED87") (pin "4") (pinfunction "DIN_4") (pintype "passive"))
    )
    (net (code "99") (name "Net-(LED87-DOUT)") (class "Default")
      (node (ref "LED87") (pin "2") (pinfunction "DOUT_2") (pintype "passive"))
      (node (ref "LED88") (pin "4") (pinfunction "DIN_4") (pintype "passive"))
    )
    (net (code "100") (name "Net-(LED88-DOUT)") (class "Default")
      (node (ref "LED88") (pin "2") (pinfunction "DOUT_2") (pintype "passive"))
      (node (ref "LED89") (pin "4") (pinfunction "DIN_4") (pintype "passive"))
    )
    (net (code "101") (name "Net-(LED89-DOUT)") (class "Default")
      (node (ref "LED89") (pin "2") (pinfunction "DOUT_2") (pintype "passive"))
      (node (ref "LED90") (pin "4") (pinfunction "DIN_4") (pintype "passive"))
    )
    (net (code "102") (name "Net-(LED90-DOUT)") (class "Default")
      (node (ref "LED90") (pin "2") (pinfunction "DOUT_2") (pintype "passive"))
      (node (ref "LED91") (pin "4") (pinfunction "DIN_4") (pintype "passive"))
    )
    (net (code "103") (name "Net-(LED91-DOUT)") (class "Default")
      (node (ref "LED91") (pin "2") (pinfunction "DOUT_2") (pintype "passive"))
      (node (ref "LED92") (pin "4") (pinfunction "DIN_4") (pintype "passive"))
    )
    (net (code "104") (name "Net-(LED92-DOUT)") (class "Default")
      (node (ref "LED92") (pin "2") (pinfunction "DOUT_2") (pintype "passive"))
      (node (ref "LED93") (pin "4") (pinfunction "DIN_4") (pintype "passive"))
    )
    (net (code "105") (name "Net-(LED93-DOUT)") (class "Default")
      (node (ref "LED93") (pin "2") (pinfunction "DOUT_2") (pintype "passive"))
      (node (ref "LED94") (pin "4") (pinfunction "DIN_4") (pintype "passive"))
    )
    (net (code "106") (name "Net-(LED94-DOUT)") (class "Default")
      (node (ref "LED94") (pin "2") (pinfunction "DOUT_2") (pintype "passive"))
      (node (ref "LED95") (pin "4") (pinfunction "DIN_4") (pintype "passive"))
    )
    (net (code "107") (name "Net-(LED95-DOUT)") (class "Default")
      (node (ref "LED95") (pin "2") (pinfunction "DOUT_2") (pintype "passive"))
      (node (ref "LED96") (pin "4") (pinfunction "DIN_4") (pintype "passive"))
    )
    (net (code "108") (name "Net-(LED97-DOUT)") (class "Default")
      (node (ref "LED97") (pin "2") (pinfunction "DOUT_2") (pintype "passive"))
      (node (ref "LED98") (pin "4") (pinfunction "DIN_4") (pintype "passive"))
    )
    (net (code "109") (name "Net-(LED98-DOUT)") (class "Default")
      (node (ref "LED98") (pin "2") (pinfunction "DOUT_2") (pintype "passive"))
      (node (ref "LED99") (pin "4") (pinfunction "DIN_4") (pintype "passive"))
    )
    (net (code "110") (name "Net-(LED100-DIN)") (class "Default")
      (node (ref "LED100") (pin "4") (pinfunction "DIN_4") (pintype "passive"))
      (node (ref "LED99") (pin "2") (pinfunction "DOUT_2") (pintype "passive"))
    )
    (net (code "111") (name "Net-(LED100-DOUT)") (class "Default")
      (node (ref "LED100") (pin "2") (pinfunction "DOUT_2") (pintype "passive"))
      (node (ref "LED101") (pin "4") (pinfunction "DIN_4") (pintype "passive"))
    )
    (net (code "112") (name "Net-(LED101-DOUT)") (class "Default")
      (node (ref "LED101") (pin "2") (pinfunction "DOUT_2") (pintype "passive"))
      (node (ref "LED102") (pin "4") (pinfunction "DIN_4") (pintype "passive"))
    )
    (net (code "113") (name "Net-(LED102-DOUT)") (class "Default")
      (node (ref "LED102") (pin "2") (pinfunction "DOUT_2") (pintype "passive"))
      (node (ref "LED103") (pin "4") (pinfunction "DIN_4") (pintype "passive"))
    )
    (net (code "114") (name "Net-(LED103-DOUT)") (class "Default")
      (node (ref "LED103") (pin "2") (pinfunction "DOUT_2") (pintype "passive"))
      (node (ref "LED104") (pin "4") (pinfunction "DIN_4") (pintype "passive"))
    )
    (net (code "115") (name "Net-(LED104-DOUT)") (class "Default")
      (node (ref "LED104") (pin "2") (pinfunction "DOUT_2") (pintype "passive"))
      (node (ref "LED105") (pin "4") (pinfunction "DIN_4") (pintype "passive"))
    )
    (net (code "116") (name "Net-(LED105-DOUT)") (class "Default")
      (node (ref "LED105") (pin "2") (pinfunction "DOUT_2") (pintype "passive"))
      (node (ref "LED106") (pin "4") (pinfunction "DIN_4") (pintype "passive"))
    )
    (net (code "117") (name "Net-(LED106-DOUT)") (class "Default")
      (node (ref "LED106") (pin "2") (pinfunction "DOUT_2") (pintype "passive"))
      (node (ref "LED107") (pin "4") (pinfunction "DIN_4") (pintype "passive"))
    )
    (net (code "118") (name "Net-(LED107-DOUT)") (class "Default")
      (node (ref "LED107") (pin "2") (pinfunction "DOUT_2") (pintype "passive"))
      (node (ref "LED108") (pin "4") (pinfunction "DIN_4") (pintype "passive"))
    )
    (net (code "119") (name "Net-(LED108-DOUT)") (class "Default")
      (node (ref "LED108") (pin "2") (pinfunction "DOUT_2") (pintype "passive"))
      (node (ref "LED109") (pin "4") (pinfunction "DIN_4") (pintype "passive"))
    )
    (net (code "120") (name "Net-(LED109-DOUT)") (class "Default")
      (node (ref "LED109") (pin "2") (pinfunction "DOUT_2") (pintype "passive"))
      (node (ref "LED110") (pin "4") (pinfunction "DIN_4") (pintype "passive"))
    )
    (net (code "121") (name "Net-(LED110-DOUT)") (class "Default")
      (node (ref "LED110") (pin "2") (pinfunction "DOUT_2") (pintype "passive"))
      (node (ref "LED111") (pin "4") (pinfunction "DIN_4") (pintype "passive"))
    )
    (net (code "122") (name "Net-(LED111-DOUT)") (class "Default")
      (node (ref "LED111") (pin "2") (pinfunction "DOUT_2") (pintype "passive"))
      (node (ref "LED112") (pin "4") (pinfunction "DIN_4") (pintype "passive"))
    )
    (net (code "123") (name "Net-(LED113-DOUT)") (class "Default")
      (node (ref "LED113") (pin "2") (pinfunction "DOUT_2") (pintype "passive"))
      (node (ref "LED114") (pin "4") (pinfunction "DIN_4") (pintype "passive"))
    )
    (net (code "124") (name "Net-(LED114-DOUT)") (class "Default")
      (node (ref "LED114") (pin "2") (pinfunction "DOUT_2") (pintype "passive"))
      (node (ref "LED115") (pin "4") (pinfunction "DIN_4") (pintype "passive"))
    )
    (net (code "125") (name "Net-(LED115-DOUT)") (class "Default")
      (node (ref "LED115") (pin "2") (pinfunction "DOUT_2") (pintype "passive"))
      (node (ref "LED116") (pin "4") (pinfunction "DIN_4") (pintype "passive"))
    )
    (net (code "126") (name "Net-(LED116-DOUT)") (class "Default")
      (node (ref "LED116") (pin "2") (pinfunction "DOUT_2") (pintype "passive"))
      (node (ref "LED117") (pin "4") (pinfunction "DIN_4") (pintype "passive"))
    )
    (net (code "127") (name "Net-(LED117-DOUT)") (class "Default")
      (node (ref "LED117") (pin "2") (pinfunction "DOUT_2") (pintype "passive"))
      (node (ref "LED118") (pin "4") (pinfunction "DIN_4") (pintype "passive"))
    )
    (net (code "128") (name "Net-(LED118-DOUT)") (class "Default")
      (node (ref "LED118") (pin "2") (pinfunction "DOUT_2") (pintype "passive"))
      (node (ref "LED119") (pin "4") (pinfunction "DIN_4") (pintype "passive"))
    )
    (net (code "129") (name "Net-(LED119-DOUT)") (class "Default")
      (node (ref "LED119") (pin "2") (pinfunction "DOUT_2") (pintype "passive"))
      (node (ref "LED120") (pin "4") (pinfunction "DIN_4") (pintype "passive"))
    )
    (net (code "130") (name "Net-(LED120-DOUT)") (class "Default")
      (node (ref "LED120") (pin "2") (pinfunction "DOUT_2") (pintype "passive"))
      (node (ref "LED121") (pin "4") (pinfunction "DIN_4") (pintype "passive"))
    )
    (net (code "131") (name "Net-(LED121-DOUT)") (class "Default")
      (node (ref "LED121") (pin "2") (pinfunction "DOUT_2") (pintype "passive"))
      (node (ref "LED122") (pin "4") (pinfunction "DIN_4") (pintype "passive"))
    )
    (net (code "132") (name "Net-(LED122-DOUT)") (class "Default")
      (node (ref "LED122") (pin "2") (pinfunction "DOUT_2") (pintype "passive"))
      (node (ref "LED123") (pin "4") (pinfunction "DIN_4") (pintype "passive"))
    )
    (net (code "133") (name "Net-(LED123-DOUT)") (class "Default")
      (node (ref "LED123") (pin "2") (pinfunction "DOUT_2") (pintype "passive"))
      (node (ref "LED124") (pin "4") (pinfunction "DIN_4") (pintype "passive"))
    )
    (net (code "134") (name "Net-(LED124-DOUT)") (class "Default")
      (node (ref "LED124") (pin "2") (pinfunction "DOUT_2") (pintype "passive"))
      (node (ref "LED125") (pin "4") (pinfunction "DIN_4") (pintype "passive"))
    )
    (net (code "135") (name "Net-(LED125-DOUT)") (class "Default")
      (node (ref "LED125") (pin "2") (pinfunction "DOUT_2") (pintype "passive"))
      (node (ref "LED126") (pin "4") (pinfunction "DIN_4") (pintype "passive"))
    )
    (net (code "136") (name "Net-(LED126-DOUT)") (class "Default")
      (node (ref "LED126") (pin "2") (pinfunction "DOUT_2") (pintype "passive"))
      (node (ref "LED127") (pin "4") (pinfunction "DIN_4") (pintype "passive"))
    )
    (net (code "137") (name "Net-(LED127-DOUT)") (class "Default")
      (node (ref "LED127") (pin "2") (pinfunction "DOUT_2") (pintype "passive"))
      (node (ref "LED128") (pin "4") (pinfunction "DIN_4") (pintype "passive"))
    )
    (net (code "138") (name "Net-(LED129-DOUT)") (class "Default")
      (node (ref "LED129") (pin "2") (pinfunction "DOUT_2") (pintype "passive"))
      (node (ref "LED130") (pin "4") (pinfunction "DIN_4") (pintype "passive"))
    )
    (net (code "139") (name "Net-(LED130-DOUT)") (class "Default")
      (node (ref "LED130") (pin "2") (pinfunction "DOUT_2") (pintype "passive"))
      (node (ref "LED131") (pin "4") (pinfunction "DIN_4") (pintype "passive"))
    )
    (net (code "140") (name "Net-(LED131-DOUT)") (class "Default")
      (node (ref "LED131") (pin "2") (pinfunction "DOUT_2") (pintype "passive"))
      (node (ref "LED132") (pin "4") (pinfunction "DIN_4") (pintype "passive"))
    )
    (net (code "141") (name "Net-(LED132-DOUT)") (class "Default")
      (node (ref "LED132") (pin "2") (pinfunction "DOUT_2") (pintype "passive"))
      (node (ref "LED133") (pin "4") (pinfunction "DIN_4") (pintype "passive"))
    )
    (net (code "142") (name "Net-(LED133-DOUT)") (class "Default")
      (node (ref "LED133") (pin "2") (pinfunction "DOUT_2") (pintype "passive"))
      (node (ref "LED134") (pin "4") (pinfunction "DIN_4") (pintype "passive"))
    )
    (net (code "143") (name "Net-(LED134-DOUT)") (class "Default")
      (node (ref "LED134") (pin "2") (pinfunction "DOUT_2") (pintype "passive"))
      (node (ref "LED135") (pin "4") (pinfunction "DIN_4") (pintype "passive"))
    )
    (net (code "144") (name "Net-(LED135-DOUT)") (class "Default")
      (node (ref "LED135") (pin "2") (pinfunction "DOUT_2") (pintype "passive"))
      (node (ref "LED136") (pin "4") (pinfunction "DIN_4") (pintype "passive"))
    )
    (net (code "145") (name "Net-(LED136-DOUT)") (class "Default")
      (node (ref "LED136") (pin "2") (pinfunction "DOUT_2") (pintype "passive"))
      (node (ref "LED137") (pin "4") (pinfunction "DIN_4") (pintype "passive"))
    )
    (net (code "146") (name "Net-(LED137-DOUT)") (class "Default")
      (node (ref "LED137") (pin "2") (pinfunction "DOUT_2") (pintype "passive"))
      (node (ref "LED138") (pin "4") (pinfunction "DIN_4") (pintype "passive"))
    )
    (net (code "147") (name "Net-(LED138-DOUT)") (class "Default")
      (node (ref "LED138") (pin "2") (pinfunction "DOUT_2") (pintype "passive"))
      (node (ref "LED139") (pin "4") (pinfunction "DIN_4") (pintype "passive"))
    )
    (net (code "148") (name "Net-(LED139-DOUT)") (class "Default")
      (node (ref "LED139") (pin "2") (pinfunction "DOUT_2") (pintype "passive"))
      (node (ref "LED140") (pin "4") (pinfunction "DIN_4") (pintype "passive"))
    )
    (net (code "149") (name "Net-(LED140-DOUT)") (class "Default")
      (node (ref "LED140") (pin "2") (pinfunction "DOUT_2") (pintype "passive"))
      (node (ref "LED141") (pin "4") (pinfunction "DIN_4") (pintype "passive"))
    )
    (net (code "150") (name "Net-(LED141-DOUT)") (class "Default")
      (node (ref "LED141") (pin "2") (pinfunction "DOUT_2") (pintype "passive"))
      (node (ref "LED142") (pin "4") (pinfunction "DIN_4") (pintype "passive"))
    )
    (net (code "151") (name "Net-(LED142-DOUT)") (class "Default")
      (node (ref "LED142") (pin "2") (pinfunction "DOUT_2") (pintype "passive"))
      (node (ref "LED143") (pin "4") (pinfunction "DIN_4") (pintype "passive"))
    )
    (net (code "152") (name "Net-(LED143-DOUT)") (class "Default")
      (node (ref "LED143") (pin "2") (pinfunction "DOUT_2") (pintype "passive"))
      (node (ref "LED144") (pin "4") (pinfunction "DIN_4") (pintype "passive"))
    )
    (net (code "153") (name "Net-(LED145-DOUT)") (class "Default")
      (node (ref "LED145") (pin "2") (pinfunction "DOUT_2") (pintype "passive"))
      (node (ref "LED146") (pin "4") (pinfunction "DIN_4") (pintype "passive"))
    )
    (net (code "154") (name "Net-(LED146-DOUT)") (class "Default")
      (node (ref "LED146") (pin "2") (pinfunction "DOUT_2") (pintype "passive"))
      (node (ref "LED147") (pin "4") (pinfunction "DIN_4") (pintype "passive"))
    )
    (net (code "155") (name "Net-(LED147-DOUT)") (class "Default")
      (node (ref "LED147") (pin "2") (pinfunction "DOUT_2") (pintype "passive"))
      (node (ref "LED148") (pin "4") (pinfunction "DIN_4") (pintype "passive"))
    )
    (net (code "156") (name "Net-(LED148-DOUT)") (class "Default")
      (node (ref "LED148") (pin "2") (pinfunction "DOUT_2") (pintype "passive"))
      (node (ref "LED149") (pin "4") (pinfunction "DIN_4") (pintype "passive"))
    )
    (net (code "157") (name "Net-(LED149-DOUT)") (class "Default")
      (node (ref "LED149") (pin "2") (pinfunction "DOUT_2") (pintype "passive"))
      (node (ref "LED150") (pin "4") (pinfunction "DIN_4") (pintype "passive"))
    )
    (net (code "158") (name "Net-(LED150-DOUT)") (class "Default")
      (node (ref "LED150") (pin "2") (pinfunction "DOUT_2") (pintype "passive"))
      (node (ref "LED151") (pin "4") (pinfunction "DIN_4") (pintype "passive"))
    )
    (net (code "159") (name "Net-(LED151-DOUT)") (class "Default")
      (node (ref "LED151") (pin "2") (pinfunction "DOUT_2") (pintype "passive"))
      (node (ref "LED152") (pin "4") (pinfunction "DIN_4") (pintype "passive"))
    )
    (net (code "160") (name "Net-(LED152-DOUT)") (class "Default")
      (node (ref "LED152") (pin "2") (pinfunction "DOUT_2") (pintype "passive"))
      (node (ref "LED153") (pin "4") (pinfunction "DIN_4") (pintype "passive"))
    )
    (net (code "161") (name "Net-(LED153-DOUT)") (class "Default")
      (node (ref "LED153") (pin "2") (pinfunction "DOUT_2") (pintype "passive"))
      (node (ref "LED154") (pin "4") (pinfunction "DIN_4") (pintype "passive"))
    )
    (net (code "162") (name "Net-(LED154-DOUT)") (class "Default")
      (node (ref "LED154") (pin "2") (pinfunction "DOUT_2") (pintype "passive"))
      (node (ref "LED155") (pin "4") (pinfunction "DIN_4") (pintype "passive"))
    )
    (net (code "163") (name "Net-(LED155-DOUT)") (class "Default")
      (node (ref "LED155") (pin "2") (pinfunction "DOUT_2") (pintype "passive"))
      (node (ref "LED156") (pin "4") (pinfunction "DIN_4") (pintype "passive"))
    )
    (net (code "164") (name "Net-(LED156-DOUT)") (class "Default")
      (node (ref "LED156") (pin "2") (pinfunction "DOUT_2") (pintype "passive"))
      (node (ref "LED157") (pin "4") (pinfunction "DIN_4") (pintype "passive"))
    )
    (net (code "165") (name "Net-(LED157-DOUT)") (class "Default")
      (node (ref "LED157") (pin "2") (pinfunction "DOUT_2") (pintype "passive"))
      (node (ref "LED158") (pin "4") (pinfunction "DIN_4") (pintype "passive"))
    )
    (net (code "166") (name "Net-(LED158-DOUT)") (class "Default")
      (node (ref "LED158") (pin "2") (pinfunction "DOUT_2") (pintype "passive"))
      (node (ref "LED159") (pin "4") (pinfunction "DIN_4") (pintype "passive"))
    )
    (net (code "167") (name "Net-(LED159-DOUT)") (class "Default")
      (node (ref "LED159") (pin "2") (pinfunction "DOUT_2") (pintype "passive"))
      (node (ref "LED160") (pin "4") (pinfunction "DIN_4") (pintype "passive"))
    )
    (net (code "168") (name "Net-(LED161-DOUT)") (class "Default")
      (node (ref "LED161") (pin "2") (pinfunction "DOUT_2") (pintype "passive"))
      (node (ref "LED162") (pin "4") (pinfunction "DIN_4") (pintype "passive"))
    )
    (net (code "169") (name "Net-(LED162-DOUT)") (class "Default")
      (node (ref "LED162") (pin "2") (pinfunction "DOUT_2") (pintype "passive"))
      (node (ref "LED163") (pin "4") (pinfunction "DIN_4") (pintype "passive"))
    )
    (net (code "170") (name "Net-(LED163-DOUT)") (class "Default")
      (node (ref "LED163") (pin "2") (pinfunction "DOUT_2") (pintype "passive"))
      (node (ref "LED164") (pin "4") (pinfunction "DIN_4") (pintype "passive"))
    )
    (net (code "171") (name "Net-(LED164-DOUT)") (class "Default")
      (node (ref "LED164") (pin "2") (pinfunction "DOUT_2") (pintype "passive"))
      (node (ref "LED165") (pin "4") (pinfunction "DIN_4") (pintype "passive"))
    )
    (net (code "172") (name "Net-(LED165-DOUT)") (class "Default")
      (node (ref "LED165") (pin "2") (pinfunction "DOUT_2") (pintype "passive"))
      (node (ref "LED166") (pin "4") (pinfunction "DIN_4") (pintype "passive"))
    )
    (net (code "173") (name "Net-(LED166-DOUT)") (class "Default")
      (node (ref "LED166") (pin "2") (pinfunction "DOUT_2") (pintype "passive"))
      (node (ref "LED167") (pin "4") (pinfunction "DIN_4") (pintype "passive"))
    )
    (net (code "174") (name "Net-(LED167-DOUT)") (class "Default")
      (node (ref "LED167") (pin "2") (pinfunction "DOUT_2") (pintype "passive"))
      (node (ref "LED168") (pin "4") (pinfunction "DIN_4") (pintype "passive"))
    )
    (net (code "175") (name "Net-(LED168-DOUT)") (class "Default")
      (node (ref "LED168") (pin "2") (pinfunction "DOUT_2") (pintype "passive"))
      (node (ref "LED169") (pin "4") (pinfunction "DIN_4") (pintype "passive"))
    )
    (net (code "176") (name "Net-(LED169-DOUT)") (class "Default")
      (node (ref "LED169") (pin "2") (pinfunction "DOUT_2") (pintype "passive"))
      (node (ref "LED170") (pin "4") (pinfunction "DIN_4") (pintype "passive"))
    )
    (net (code "177") (name "Net-(LED170-DOUT)") (class "Default")
      (node (ref "LED170") (pin "2") (pinfunction "DOUT_2") (pintype "passive"))
      (node (ref "LED171") (pin "4") (pinfunction "DIN_4") (pintype "passive"))
    )
    (net (code "178") (name "Net-(LED171-DOUT)") (class "Default")
      (node (ref "LED171") (pin "2") (pinfunction "DOUT_2") (pintype "passive"))
      (node (ref "LED172") (pin "4") (pinfunction "DIN_4") (pintype "passive"))
    )
    (net (code "179") (name "Net-(LED172-DOUT)") (class "Default")
      (node (ref "LED172") (pin "2") (pinfunction "DOUT_2") (pintype "passive"))
      (node (ref "LED173") (pin "4") (pinfunction "DIN_4") (pintype "passive"))
    )
    (net (code "180") (name "Net-(LED173-DOUT)") (class "Default")
      (node (ref "LED173") (pin "2") (pinfunction "DOUT_2") (pintype "passive"))
      (node (ref "LED174") (pin "4") (pinfunction "DIN_4") (pintype "passive"))
    )
    (net (code "181") (name "Net-(LED174-DOUT)") (class "Default")
      (node (ref "LED174") (pin "2") (pinfunction "DOUT_2") (pintype "passive"))
      (node (ref "LED175") (pin "4") (pinfunction "DIN_4") (pintype "passive"))
    )
    (net (code "182") (name "Net-(LED175-DOUT)") (class "Default")
      (node (ref "LED175") (pin "2") (pinfunction "DOUT_2") (pintype "passive"))
      (node (ref "LED176") (pin "4") (pinfunction "DIN_4") (pintype "passive"))
    )
    (net (code "183") (name "Net-(LED177-DOUT)") (class "Default")
      (node (ref "LED177") (pin "2") (pinfunction "DOUT_2") (pintype "passive"))
      (node (ref "LED178") (pin "4") (pinfunction "DIN_4") (pintype "passive"))
    )
    (net (code "184") (name "Net-(LED178-DOUT)") (class "Default")
      (node (ref "LED178") (pin "2") (pinfunction "DOUT_2") (pintype "passive"))
      (node (ref "LED179") (pin "4") (pinfunction "DIN_4") (pintype "passive"))
    )
    (net (code "185") (name "Net-(LED179-DOUT)") (class "Default")
      (node (ref "LED179") (pin "2") (pinfunction "DOUT_2") (pintype "passive"))
      (node (ref "LED180") (pin "4") (pinfunction "DIN_4") (pintype "passive"))
    )
    (net (code "186") (name "Net-(LED180-DOUT)") (class "Default")
      (node (ref "LED180") (pin "2") (pinfunction "DOUT_2") (pintype "passive"))
      (node (ref "LED181") (pin "4") (pinfunction "DIN_4") (pintype "passive"))
    )
    (net (code "187") (name "Net-(LED181-DOUT)") (class "Default")
      (node (ref "LED181") (pin "2") (pinfunction "DOUT_2") (pintype "passive"))
      (node (ref "LED182") (pin "4") (pinfunction "DIN_4") (pintype "passive"))
    )
    (net (code "188") (name "Net-(LED182-DOUT)") (class "Default")
      (node (ref "LED182") (pin "2") (pinfunction "DOUT_2") (pintype "passive"))
      (node (ref "LED183") (pin "4") (pinfunction "DIN_4") (pintype "passive"))
    )
    (net (code "189") (name "Net-(LED183-DOUT)") (class "Default")
      (node (ref "LED183") (pin "2") (pinfunction "DOUT_2") (pintype "passive"))
      (node (ref "LED184") (pin "4") (pinfunction "DIN_4") (pintype "passive"))
    )
    (net (code "190") (name "Net-(LED184-DOUT)") (class "Default")
      (node (ref "LED184") (pin "2") (pinfunction "DOUT_2") (pintype "passive"))
      (node (ref "LED185") (pin "4") (pinfunction "DIN_4") (pintype "passive"))
    )
    (net (code "191") (name "Net-(LED185-DOUT)") (class "Default")
      (node (ref "LED185") (pin "2") (pinfunction "DOUT_2") (pintype "passive"))
      (node (ref "LED186") (pin "4") (pinfunction "DIN_4") (pintype "passive"))
    )
    (net (code "192") (name "Net-(LED186-DOUT)") (class "Default")
      (node (ref "LED186") (pin "2") (pinfunction "DOUT_2") (pintype "passive"))
      (node (ref "LED187") (pin "4") (pinfunction "DIN_4") (pintype "passive"))
    )
    (net (code "193") (name "Net-(LED187-DOUT)") (class "Default")
      (node (ref "LED187") (pin "2") (pinfunction "DOUT_2") (pintype "passive"))
      (node (ref "LED188") (pin "4") (pinfunction "DIN_4") (pintype "passive"))
    )
    (net (code "194") (name "Net-(LED188-DOUT)") (class "Default")
      (node (ref "LED188") (pin "2") (pinfunction "DOUT_2") (pintype "passive"))
      (node (ref "LED189") (pin "4") (pinfunction "DIN_4") (pintype "passive"))
    )
    (net (code "195") (name "Net-(LED189-DOUT)") (class "Default")
      (node (ref "LED189") (pin "2") (pinfunction "DOUT_2") (pintype "passive"))
      (node (ref "LED190") (pin "4") (pinfunction "DIN_4") (pintype "passive"))
    )
    (net (code "196") (name "Net-(LED190-DOUT)") (class "Default")
      (node (ref "LED190") (pin "2") (pinfunction "DOUT_2") (pintype "passive"))
      (node (ref "LED191") (pin "4") (pinfunction "DIN_4") (pintype "passive"))
    )
    (net (code "197") (name "Net-(LED191-DOUT)") (class "Default")
      (node (ref "LED191") (pin "2") (pinfunction "DOUT_2") (pintype "passive"))
      (node (ref "LED192") (pin "4") (pinfunction "DIN_4") (pintype "passive"))
    )
    (net (code "198") (name "Net-(LED193-DOUT)") (class "Default")
      (node (ref "LED193") (pin "2") (pinfunction "DOUT_2") (pintype "passive"))
      (node (ref "LED194") (pin "4") (pinfunction "DIN_4") (pintype "passive"))
    )
    (net (code "199") (name "Net-(LED194-DOUT)") (class "Default")
      (node (ref "LED194") (pin "2") (pinfunction "DOUT_2") (pintype "passive"))
      (node (ref "LED195") (pin "4") (pinfunction "DIN_4") (pintype "passive"))
    )
    (net (code "200") (name "Net-(LED195-DOUT)") (class "Default")
      (node (ref "LED195") (pin "2") (pinfunction "DOUT_2") (pintype "passive"))
      (node (ref "LED196") (pin "4") (pinfunction "DIN_4") (pintype "passive"))
    )
    (net (code "201") (name "Net-(LED196-DOUT)") (class "Default")
      (node (ref "LED196") (pin "2") (pinfunction "DOUT_2") (pintype "passive"))
      (node (ref "LED197") (pin "4") (pinfunction "DIN_4") (pintype "passive"))
    )
    (net (code "202") (name "Net-(LED197-DOUT)") (class "Default")
      (node (ref "LED197") (pin "2") (pinfunction "DOUT_2") (pintype "passive"))
      (node (ref "LED198") (pin "4") (pinfunction "DIN_4") (pintype "passive"))
    )
    (net (code "203") (name "Net-(LED198-DOUT)") (class "Default")
      (node (ref "LED198") (pin "2") (pinfunction "DOUT_2") (pintype "passive"))
      (node (ref "LED199") (pin "4") (pinfunction "DIN_4") (pintype "passive"))
    )
    (net (code "204") (name "Net-(LED199-DOUT)") (class "Default")
      (node (ref "LED199") (pin "2") (pinfunction "DOUT_2") (pintype "passive"))
      (node (ref "LED200") (pin "4") (pinfunction "DIN_4") (pintype "passive"))
    )
    (net (code "205") (name "Net-(LED200-DOUT)") (class "Default")
      (node (ref "LED200") (pin "2") (pinfunction "DOUT_2") (pintype "passive"))
      (node (ref "LED201") (pin "4") (pinfunction "DIN_4") (pintype "passive"))
    )
    (net (code "206") (name "Net-(LED201-DOUT)") (class "Default")
      (node (ref "LED201") (pin "2") (pinfunction "DOUT_2") (pintype "passive"))
      (node (ref "LED202") (pin "4") (pinfunction "DIN_4") (pintype "passive"))
    )
    (net (code "207") (name "Net-(LED202-DOUT)") (class "Default")
      (node (ref "LED202") (pin "2") (pinfunction "DOUT_2") (pintype "passive"))
      (node (ref "LED203") (pin "4") (pinfunction "DIN_4") (pintype "passive"))
    )
    (net (code "208") (name "Net-(LED203-DOUT)") (class "Default")
      (node (ref "LED203") (pin "2") (pinfunction "DOUT_2") (pintype "passive"))
      (node (ref "LED204") (pin "4") (pinfunction "DIN_4") (pintype "passive"))
    )
    (net (code "209") (name "Net-(LED204-DOUT)") (class "Default")
      (node (ref "LED204") (pin "2") (pinfunction "DOUT_2") (pintype "passive"))
      (node (ref "LED205") (pin "4") (pinfunction "DIN_4") (pintype "passive"))
    )
    (net (code "210") (name "Net-(LED205-DOUT)") (class "Default")
      (node (ref "LED205") (pin "2") (pinfunction "DOUT_2") (pintype "passive"))
      (node (ref "LED206") (pin "4") (pinfunction "DIN_4") (pintype "passive"))
    )
    (net (code "211") (name "Net-(LED206-DOUT)") (class "Default")
      (node (ref "LED206") (pin "2") (pinfunction "DOUT_2") (pintype "passive"))
      (node (ref "LED207") (pin "4") (pinfunction "DIN_4") (pintype "passive"))
    )
    (net (code "212") (name "Net-(LED207-DOUT)") (class "Default")
      (node (ref "LED207") (pin "2") (pinfunction "DOUT_2") (pintype "passive"))
      (node (ref "LED208") (pin "4") (pinfunction "DIN_4") (pintype "passive"))
    )
    (net (code "213") (name "Net-(LED209-DOUT)") (class "Default")
      (node (ref "LED209") (pin "2") (pinfunction "DOUT_2") (pintype "passive"))
      (node (ref "LED210") (pin "4") (pinfunction "DIN_4") (pintype "passive"))
    )
    (net (code "214") (name "Net-(LED210-DOUT)") (class "Default")
      (node (ref "LED210") (pin "2") (pinfunction "DOUT_2") (pintype "passive"))
      (node (ref "LED211") (pin "4") (pinfunction "DIN_4") (pintype "passive"))
    )
    (net (code "215") (name "Net-(LED211-DOUT)") (class "Default")
      (node (ref "LED211") (pin "2") (pinfunction "DOUT_2") (pintype "passive"))
      (node (ref "LED212") (pin "4") (pinfunction "DIN_4") (pintype "passive"))
    )
    (net (code "216") (name "Net-(LED212-DOUT)") (class "Default")
      (node (ref "LED212") (pin "2") (pinfunction "DOUT_2") (pintype "passive"))
      (node (ref "LED213") (pin "4") (pinfunction "DIN_4") (pintype "passive"))
    )
    (net (code "217") (name "Net-(LED213-DOUT)") (class "Default")
      (node (ref "LED213") (pin "2") (pinfunction "DOUT_2") (pintype "passive"))
      (node (ref "LED214") (pin "4") (pinfunction "DIN_4") (pintype "passive"))
    )
    (net (code "218") (name "Net-(LED214-DOUT)") (class "Default")
      (node (ref "LED214") (pin "2") (pinfunction "DOUT_2") (pintype "passive"))
      (node (ref "LED215") (pin "4") (pinfunction "DIN_4") (pintype "passive"))
    )
    (net (code "219") (name "Net-(LED215-DOUT)") (class "Default")
      (node (ref "LED215") (pin "2") (pinfunction "DOUT_2") (pintype "passive"))
      (node (ref "LED216") (pin "4") (pinfunction "DIN_4") (pintype "passive"))
    )
    (net (code "220") (name "Net-(LED216-DOUT)") (class "Default")
      (node (ref "LED216") (pin "2") (pinfunction "DOUT_2") (pintype "passive"))
      (node (ref "LED217") (pin "4") (pinfunction "DIN_4") (pintype "passive"))
    )
    (net (code "221") (name "Net-(LED217-DOUT)") (class "Default")
      (node (ref "LED217") (pin "2") (pinfunction "DOUT_2") (pintype "passive"))
      (node (ref "LED218") (pin "4") (pinfunction "DIN_4") (pintype "passive"))
    )
    (net (code "222") (name "Net-(LED218-DOUT)") (class "Default")
      (node (ref "LED218") (pin "2") (pinfunction "DOUT_2") (pintype "passive"))
      (node (ref "LED219") (pin "4") (pinfunction "DIN_4") (pintype "passive"))
    )
    (net (code "223") (name "Net-(LED219-DOUT)") (class "Default")
      (node (ref "LED219") (pin "2") (pinfunction "DOUT_2") (pintype "passive"))
      (node (ref "LED220") (pin "4") (pinfunction "DIN_4") (pintype "passive"))
    )
    (net (code "224") (name "Net-(LED220-DOUT)") (class "Default")
      (node (ref "LED220") (pin "2") (pinfunction "DOUT_2") (pintype "passive"))
      (node (ref "LED221") (pin "4") (pinfunction "DIN_4") (pintype "passive"))
    )
    (net (code "225") (name "Net-(LED221-DOUT)") (class "Default")
      (node (ref "LED221") (pin "2") (pinfunction "DOUT_2") (pintype "passive"))
      (node (ref "LED222") (pin "4") (pinfunction "DIN_4") (pintype "passive"))
    )
    (net (code "226") (name "Net-(LED222-DOUT)") (class "Default")
      (node (ref "LED222") (pin "2") (pinfunction "DOUT_2") (pintype "passive"))
      (node (ref "LED223") (pin "4") (pinfunction "DIN_4") (pintype "passive"))
    )
    (net (code "227") (name "Net-(LED223-DOUT)") (class "Default")
      (node (ref "LED223") (pin "2") (pinfunction "DOUT_2") (pintype "passive"))
      (node (ref "LED224") (pin "4") (pinfunction "DIN_4") (pintype "passive"))
    )
    (net (code "228") (name "Net-(LED225-DOUT)") (class "Default")
      (node (ref "LED225") (pin "2") (pinfunction "DOUT_2") (pintype "passive"))
      (node (ref "LED226") (pin "4") (pinfunction "DIN_4") (pintype "passive"))
    )
    (net (code "229") (name "Net-(LED226-DOUT)") (class "Default")
      (node (ref "LED226") (pin "2") (pinfunction "DOUT_2") (pintype "passive"))
      (node (ref "LED227") (pin "4") (pinfunction "DIN_4") (pintype "passive"))
    )
    (net (code "230") (name "Net-(LED227-DOUT)") (class "Default")
      (node (ref "LED227") (pin "2") (pinfunction "DOUT_2") (pintype "passive"))
      (node (ref "LED228") (pin "4") (pinfunction "DIN_4") (pintype "passive"))
    )
    (net (code "231") (name "Net-(LED228-DOUT)") (class "Default")
      (node (ref "LED228") (pin "2") (pinfunction "DOUT_2") (pintype "passive"))
      (node (ref "LED229") (pin "4") (pinfunction "DIN_4") (pintype "passive"))
    )
    (net (code "232") (name "Net-(LED229-DOUT)") (class "Default")
      (node (ref "LED229") (pin "2") (pinfunction "DOUT_2") (pintype "passive"))
      (node (ref "LED230") (pin "4") (pinfunction "DIN_4") (pintype "passive"))
    )
    (net (code "233") (name "Net-(LED230-DOUT)") (class "Default")
      (node (ref "LED230") (pin "2") (pinfunction "DOUT_2") (pintype "passive"))
      (node (ref "LED231") (pin "4") (pinfunction "DIN_4") (pintype "passive"))
    )
    (net (code "234") (name "Net-(LED231-DOUT)") (class "Default")
      (node (ref "LED231") (pin "2") (pinfunction "DOUT_2") (pintype "passive"))
      (node (ref "LED232") (pin "4") (pinfunction "DIN_4") (pintype "passive"))
    )
    (net (code "235") (name "Net-(LED232-DOUT)") (class "Default")
      (node (ref "LED232") (pin "2") (pinfunction "DOUT_2") (pintype "passive"))
      (node (ref "LED233") (pin "4") (pinfunction "DIN_4") (pintype "passive"))
    )
    (net (code "236") (name "Net-(LED233-DOUT)") (class "Default")
      (node (ref "LED233") (pin "2") (pinfunction "DOUT_2") (pintype "passive"))
      (node (ref "LED234") (pin "4") (pinfunction "DIN_4") (pintype "passive"))
    )
    (net (code "237") (name "Net-(LED234-DOUT)") (class "Default")
      (node (ref "LED234") (pin "2") (pinfunction "DOUT_2") (pintype "passive"))
      (node (ref "LED235") (pin "4") (pinfunction "DIN_4") (pintype "passive"))
    )
    (net (code "238") (name "Net-(LED235-DOUT)") (class "Default")
      (node (ref "LED235") (pin "2") (pinfunction "DOUT_2") (pintype "passive"))
      (node (ref "LED236") (pin "4") (pinfunction "DIN_4") (pintype "passive"))
    )
    (net (code "239") (name "Net-(LED236-DOUT)") (class "Default")
      (node (ref "LED236") (pin "2") (pinfunction "DOUT_2") (pintype "passive"))
      (node (ref "LED237") (pin "4") (pinfunction "DIN_4") (pintype "passive"))
    )
    (net (code "240") (name "Net-(LED237-DOUT)") (class "Default")
      (node (ref "LED237") (pin "2") (pinfunction "DOUT_2") (pintype "passive"))
      (node (ref "LED238") (pin "4") (pinfunction "DIN_4") (pintype "passive"))
    )
    (net (code "241") (name "Net-(LED238-DOUT)") (class "Default")
      (node (ref "LED238") (pin "2") (pinfunction "DOUT_2") (pintype "passive"))
      (node (ref "LED239") (pin "4") (pinfunction "DIN_4") (pintype "passive"))
    )
    (net (code "242") (name "Net-(LED239-DOUT)") (class "Default")
      (node (ref "LED239") (pin "2") (pinfunction "DOUT_2") (pintype "passive"))
      (node (ref "LED240") (pin "4") (pinfunction "DIN_4") (pintype "passive"))
    )
    (net (code "243") (name "Net-(LED241-DOUT)") (class "Default")
      (node (ref "LED241") (pin "2") (pinfunction "DOUT_2") (pintype "passive"))
      (node (ref "LED242") (pin "4") (pinfunction "DIN_4") (pintype "passive"))
    )
    (net (code "244") (name "Net-(LED242-DOUT)") (class "Default")
      (node (ref "LED242") (pin "2") (pinfunction "DOUT_2") (pintype "passive"))
      (node (ref "LED243") (pin "4") (pinfunction "DIN_4") (pintype "passive"))
    )
    (net (code "245") (name "Net-(LED243-DOUT)") (class "Default")
      (node (ref "LED243") (pin "2") (pinfunction "DOUT_2") (pintype "passive"))
      (node (ref "LED244") (pin "4") (pinfunction "DIN_4") (pintype "passive"))
    )
    (net (code "246") (name "Net-(LED244-DOUT)") (class "Default")
      (node (ref "LED244") (pin "2") (pinfunction "DOUT_2") (pintype "passive"))
      (node (ref "LED245") (pin "4") (pinfunction "DIN_4") (pintype "passive"))
    )
    (net (code "247") (name "Net-(LED245-DOUT)") (class "Default")
      (node (ref "LED245") (pin "2") (pinfunction "DOUT_2") (pintype "passive"))
      (node (ref "LED246") (pin "4") (pinfunction "DIN_4") (pintype "passive"))
    )
    (net (code "248") (name "Net-(LED246-DOUT)") (class "Default")
      (node (ref "LED246") (pin "2") (pinfunction "DOUT_2") (pintype "passive"))
      (node (ref "LED247") (pin "4") (pinfunction "DIN_4") (pintype "passive"))
    )
    (net (code "249") (name "Net-(LED247-DOUT)") (class "Default")
      (node (ref "LED247") (pin "2") (pinfunction "DOUT_2") (pintype "passive"))
      (node (ref "LED248") (pin "4") (pinfunction "DIN_4") (pintype "passive"))
    )
    (net (code "250") (name "Net-(LED248-DOUT)") (class "Default")
      (node (ref "LED248") (pin "2") (pinfunction "DOUT_2") (pintype "passive"))
      (node (ref "LED249") (pin "4") (pinfunction "DIN_4") (pintype "passive"))
    )
    (net (code "251") (name "Net-(LED249-DOUT)") (class "Default")
      (node (ref "LED249") (pin "2") (pinfunction "DOUT_2") (pintype "passive"))
      (node (ref "LED250") (pin "4") (pinfunction "DIN_4") (pintype "passive"))
    )
    (net (code "252") (name "Net-(LED250-DOUT)") (class "Default")
      (node (ref "LED250") (pin "2") (pinfunction "DOUT_2") (pintype "passive"))
      (node (ref "LED251") (pin "4") (pinfunction "DIN_4") (pintype "passive"))
    )
    (net (code "253") (name "Net-(LED251-DOUT)") (class "Default")
      (node (ref "LED251") (pin "2") (pinfunction "DOUT_2") (pintype "passive"))
      (node (ref "LED252") (pin "4") (pinfunction "DIN_4") (pintype "passive"))
    )
    (net (code "254") (name "Net-(LED252-DOUT)") (class "Default")
      (node (ref "LED252") (pin "2") (pinfunction "DOUT_2") (pintype "passive"))
      (node (ref "LED253") (pin "4") (pinfunction "DIN_4") (pintype "passive"))
    )
    (net (code "255") (name "Net-(LED253-DOUT)") (class "Default")
      (node (ref "LED253") (pin "2") (pinfunction "DOUT_2") (pintype "passive"))
      (node (ref "LED254") (pin "4") (pinfunction "DIN_4") (pintype "passive"))
    )
    (net (code "256") (name "Net-(LED254-DOUT)") (class "Default")
      (node (ref "LED254") (pin "2") (pinfunction "DOUT_2") (pintype "passive"))
      (node (ref "LED255") (pin "4") (pinfunction "DIN_4") (pintype "passive"))
    )
    (net (code "257") (name "Net-(LED255-DOUT)") (class "Default")
      (node (ref "LED255") (pin "2") (pinfunction "DOUT_2") (pintype "passive"))
      (node (ref "LED256") (pin "4") (pinfunction "DIN_4") (pintype "passive"))
    )
    (net (code "258") (name "VCC") (class "Default")
      (node (ref "LED1") (pin "1") (pinfunction "VDD_1") (pintype "passive"))
      (node (ref "LED10") (pin "1") (pinfunction "VDD_1") (pintype "passive"))
      (node (ref "LED100") (pin "1") (pinfunction "VDD_1") (pintype "passive"))
      (node (ref "LED101") (pin "1") (pinfunction "VDD_1") (pintype "passive"))
      (node (ref "LED102") (pin "1") (pinfunction "VDD_1") (pintype "passive"))
      (node (ref "LED103") (pin "1") (pinfunction "VDD_1") (pintype "passive"))
      (node (ref "LED104") (pin "1") (pinfunction "VDD_1") (pintype "passive"))
      (node (ref "LED105") (pin "1") (pinfunction "VDD_1") (pintype "passive"))
      (node (ref "LED106") (pin "1") (pinfunction "VDD_1") (pintype "passive"))
      (node (ref "LED107") (pin "1") (pinfunction "VDD_1") (pintype "passive"))
      (node (ref "LED108") (pin "1") (pinfunction "VDD_1") (pintype "passive"))
      (node (ref "LED109") (pin "1") (pinfunction "VDD_1") (pintype "passive"))
      (node (ref "LED11") (pin "1") (pinfunction "VDD_1") (pintype "passive"))
      (node (ref "LED110") (pin "1") (pinfunction "VDD_1") (pintype "passive"))
      (node (ref "LED111") (pin "1") (pinfunction "VDD_1") (pintype "passive"))
      (node (ref "LED112") (pin "1") (pinfunction "VDD_1") (pintype "passive"))
      (node (ref "LED113") (pin "1") (pinfunction "VDD_1") (pintype "passive"))
      (node (ref "LED114") (pin "1") (pinfunction "VDD_1") (pintype "passive"))
      (node (ref "LED115") (pin "1") (pinfunction "VDD_1") (pintype "passive"))
      (node (ref "LED116") (pin "1") (pinfunction "VDD_1") (pintype "passive"))
      (node (ref "LED117") (pin "1") (pinfunction "VDD_1") (pintype "passive"))
      (node (ref "LED118") (pin "1") (pinfunction "VDD_1") (pintype "passive"))
      (node (ref "LED119") (pin "1") (pinfunction "VDD_1") (pintype "passive"))
      (node (ref "LED12") (pin "1") (pinfunction "VDD_1") (pintype "passive"))
      (node (ref "LED120") (pin "1") (pinfunction "VDD_1") (pintype "passive"))
      (node (ref "LED121") (pin "1") (pinfunction "VDD_1") (pintype "passive"))
      (node (ref "LED122") (pin "1") (pinfunction "VDD_1") (pintype "passive"))
      (node (ref "LED123") (pin "1") (pinfunction "VDD_1") (pintype "passive"))
      (node (ref "LED124") (pin "1") (pinfunction "VDD_1") (pintype "passive"))
      (node (ref "LED125") (pin "1") (pinfunction "VDD_1") (pintype "passive"))
      (node (ref "LED126") (pin "1") (pinfunction "VDD_1") (pintype "passive"))
      (node (ref "LED127") (pin "1") (pinfunction "VDD_1") (pintype "passive"))
      (node (ref "LED128") (pin "1") (pinfunction "VDD_1") (pintype "passive"))
      (node (ref "LED129") (pin "1") (pinfunction "VDD_1") (pintype "passive"))
      (node (ref "LED13") (pin "1") (pinfunction "VDD_1") (pintype "passive"))
      (node (ref "LED130") (pin "1") (pinfunction "VDD_1") (pintype "passive"))
      (node (ref "LED131") (pin "1") (pinfunction "VDD_1") (pintype "passive"))
      (node (ref "LED132") (pin "1") (pinfunction "VDD_1") (pintype "passive"))
      (node (ref "LED133") (pin "1") (pinfunction "VDD_1") (pintype "passive"))
      (node (ref "LED134") (pin "1") (pinfunction "VDD_1") (pintype "passive"))
      (node (ref "LED135") (pin "1") (pinfunction "VDD_1") (pintype "passive"))
      (node (ref "LED136") (pin "1") (pinfunction "VDD_1") (pintype "passive"))
      (node (ref "LED137") (pin "1") (pinfunction "VDD_1") (pintype "passive"))
      (node (ref "LED138") (pin "1") (pinfunction "VDD_1") (pintype "passive"))
      (node (ref "LED139") (pin "1") (pinfunction "VDD_1") (pintype "passive"))
      (node (ref "LED14") (pin "1") (pinfunction "VDD_1") (pintype "passive"))
      (node (ref "LED140") (pin "1") (pinfunction "VDD_1") (pintype "passive"))
      (node (ref "LED141") (pin "1") (pinfunction "VDD_1") (pintype "passive"))
      (node (ref "LED142") (pin "1") (pinfunction "VDD_1") (pintype "passive"))
      (node (ref "LED143") (pin "1") (pinfunction "VDD_1") (pintype "passive"))
      (node (ref "LED144") (pin "1") (pinfunction "VDD_1") (pintype "passive"))
      (node (ref "LED145") (pin "1") (pinfunction "VDD_1") (pintype "passive"))
      (node (ref "LED146") (pin "1") (pinfunction "VDD_1") (pintype "passive"))
      (node (ref "LED147") (pin "1") (pinfunction "VDD_1") (pintype "passive"))
      (node (ref "LED148") (pin "1") (pinfunction "VDD_1") (pintype "passive"))
      (node (ref "LED149") (pin "1") (pinfunction "VDD_1") (pintype "passive"))
      (node (ref "LED15") (pin "1") (pinfunction "VDD_1") (pintype "passive"))
      (node (ref "LED150") (pin "1") (pinfunction "VDD_1") (pintype "passive"))
      (node (ref "LED151") (pin "1") (pinfunction "VDD_1") (pintype "passive"))
      (node (ref "LED152") (pin "1") (pinfunction "VDD_1") (pintype "passive"))
      (node (ref "LED153") (pin "1") (pinfunction "VDD_1") (pintype "passive"))
      (node (ref "LED154") (pin "1") (pinfunction "VDD_1") (pintype "passive"))
      (node (ref "LED155") (pin "1") (pinfunction "VDD_1") (pintype "passive"))
      (node (ref "LED156") (pin "1") (pinfunction "VDD_1") (pintype "passive"))
      (node (ref "LED157") (pin "1") (pinfunction "VDD_1") (pintype "passive"))
      (node (ref "LED158") (pin "1") (pinfunction "VDD_1") (pintype "passive"))
      (node (ref "LED159") (pin "1") (pinfunction "VDD_1") (pintype "passive"))
      (node (ref "LED16") (pin "1") (pinfunction "VDD_1") (pintype "passive"))
      (node (ref "LED160") (pin "1") (pinfunction "VDD_1") (pintype "passive"))
      (node (ref "LED161") (pin "1") (pinfunction "VDD_1") (pintype "passive"))
      (node (ref "LED162") (pin "1") (pinfunction "VDD_1") (pintype "passive"))
      (node (ref "LED163") (pin "1") (pinfunction "VDD_1") (pintype "passive"))
      (node (ref "LED164") (pin "1") (pinfunction "VDD_1") (pintype "passive"))
      (node (ref "LED165") (pin "1") (pinfunction "VDD_1") (pintype "passive"))
      (node (ref "LED166") (pin "1") (pinfunction "VDD_1") (pintype "passive"))
      (node (ref "LED167") (pin "1") (pinfunction "VDD_1") (pintype "passive"))
      (node (ref "LED168") (pin "1") (pinfunction "VDD_1") (pintype "passive"))
      (node (ref "LED169") (pin "1") (pinfunction "VDD_1") (pintype "passive"))
      (node (ref "LED17") (pin "1") (pinfunction "VDD_1") (pintype "passive"))
      (node (ref "LED170") (pin "1") (pinfunction "VDD_1") (pintype "passive"))
      (node (ref "LED171") (pin "1") (pinfunction "VDD_1") (pintype "passive"))
      (node (ref "LED172") (pin "1") (pinfunction "VDD_1") (pintype "passive"))
      (node (ref "LED173") (pin "1") (pinfunction "VDD_1") (pintype "passive"))
      (node (ref "LED174") (pin "1") (pinfunction "VDD_1") (pintype "passive"))
      (node (ref "LED175") (pin "1") (pinfunction "VDD_1") (pintype "passive"))
      (node (ref "LED176") (pin "1") (pinfunction "VDD_1") (pintype "passive"))
      (node (ref "LED177") (pin "1") (pinfunction "VDD_1") (pintype "passive"))
      (node (ref "LED178") (pin "1") (pinfunction "VDD_1") (pintype "passive"))
      (node (ref "LED179") (pin "1") (pinfunction "VDD_1") (pintype "passive"))
      (node (ref "LED18") (pin "1") (pinfunction "VDD_1") (pintype "passive"))
      (node (ref "LED180") (pin "1") (pinfunction "VDD_1") (pintype "passive"))
      (node (ref "LED181") (pin "1") (pinfunction "VDD_1") (pintype "passive"))
      (node (ref "LED182") (pin "1") (pinfunction "VDD_1") (pintype "passive"))
      (node (ref "LED183") (pin "1") (pinfunction "VDD_1") (pintype "passive"))
      (node (ref "LED184") (pin "1") (pinfunction "VDD_1") (pintype "passive"))
      (node (ref "LED185") (pin "1") (pinfunction "VDD_1") (pintype "passive"))
      (node (ref "LED186") (pin "1") (pinfunction "VDD_1") (pintype "passive"))
      (node (ref "LED187") (pin "1") (pinfunction "VDD_1") (pintype "passive"))
      (node (ref "LED188") (pin "1") (pinfunction "VDD_1") (pintype "passive"))
      (node (ref "LED189") (pin "1") (pinfunction "VDD_1") (pintype "passive"))
      (node (ref "LED19") (pin "1") (pinfunction "VDD_1") (pintype "passive"))
      (node (ref "LED190") (pin "1") (pinfunction "VDD_1") (pintype "passive"))
      (node (ref "LED191") (pin "1") (pinfunction "VDD_1") (pintype "passive"))
      (node (ref "LED192") (pin "1") (pinfunction "VDD_1") (pintype "passive"))
      (node (ref "LED193") (pin "1") (pinfunction "VDD_1") (pintype "passive"))
      (node (ref "LED194") (pin "1") (pinfunction "VDD_1") (pintype "passive"))
      (node (ref "LED195") (pin "1") (pinfunction "VDD_1") (pintype "passive"))
      (node (ref "LED196") (pin "1") (pinfunction "VDD_1") (pintype "passive"))
      (node (ref "LED197") (pin "1") (pinfunction "VDD_1") (pintype "passive"))
      (node (ref "LED198") (pin "1") (pinfunction "VDD_1") (pintype "passive"))
      (node (ref "LED199") (pin "1") (pinfunction "VDD_1") (pintype "passive"))
      (node (ref "LED2") (pin "1") (pinfunction "VDD_1") (pintype "passive"))
      (node (ref "LED20") (pin "1") (pinfunction "VDD_1") (pintype "passive"))
      (node (ref "LED200") (pin "1") (pinfunction "VDD_1") (pintype "passive"))
      (node (ref "LED201") (pin "1") (pinfunction "VDD_1") (pintype "passive"))
      (node (ref "LED202") (pin "1") (pinfunction "VDD_1") (pintype "passive"))
      (node (ref "LED203") (pin "1") (pinfunction "VDD_1") (pintype "passive"))
      (node (ref "LED204") (pin "1") (pinfunction "VDD_1") (pintype "passive"))
      (node (ref "LED205") (pin "1") (pinfunction "VDD_1") (pintype "passive"))
      (node (ref "LED206") (pin "1") (pinfunction "VDD_1") (pintype "passive"))
      (node (ref "LED207") (pin "1") (pinfunction "VDD_1") (pintype "passive"))
      (node (ref "LED208") (pin "1") (pinfunction "VDD_1") (pintype "passive"))
      (node (ref "LED209") (pin "1") (pinfunction "VDD_1") (pintype "passive"))
      (node (ref "LED21") (pin "1") (pinfunction "VDD_1") (pintype "passive"))
      (node (ref "LED210") (pin "1") (pinfunction "VDD_1") (pintype "passive"))
      (node (ref "LED211") (pin "1") (pinfunction "VDD_1") (pintype "passive"))
      (node (ref "LED212") (pin "1") (pinfunction "VDD_1") (pintype "passive"))
      (node (ref "LED213") (pin "1") (pinfunction "VDD_1") (pintype "passive"))
      (node (ref "LED214") (pin "1") (pinfunction "VDD_1") (pintype "passive"))
      (node (ref "LED215") (pin "1") (pinfunction "VDD_1") (pintype "passive"))
      (node (ref "LED216") (pin "1") (pinfunction "VDD_1") (pintype "passive"))
      (node (ref "LED217") (pin "1") (pinfunction "VDD_1") (pintype "passive"))
      (node (ref "LED218") (pin "1") (pinfunction "VDD_1") (pintype "passive"))
      (node (ref "LED219") (pin "1") (pinfunction "VDD_1") (pintype "passive"))
      (node (ref "LED22") (pin "1") (pinfunction "VDD_1") (pintype "passive"))
      (node (ref "LED220") (pin "1") (pinfunction "VDD_1") (pintype "passive"))
      (node (ref "LED221") (pin "1") (pinfunction "VDD_1") (pintype "passive"))
      (node (ref "LED222") (pin "1") (pinfunction "VDD_1") (pintype "passive"))
      (node (ref "LED223") (pin "1") (pinfunction "VDD_1") (pintype "passive"))
      (node (ref "LED224") (pin "1") (pinfunction "VDD_1") (pintype "passive"))
      (node (ref "LED225") (pin "1") (pinfunction "VDD_1") (pintype "passive"))
      (node (ref "LED226") (pin "1") (pinfunction "VDD_1") (pintype "passive"))
      (node (ref "LED227") (pin "1") (pinfunction "VDD_1") (pintype "passive"))
      (node (ref "LED228") (pin "1") (pinfunction "VDD_1") (pintype "passive"))
      (node (ref "LED229") (pin "1") (pinfunction "VDD_1") (pintype "passive"))
      (node (ref "LED23") (pin "1") (pinfunction "VDD_1") (pintype "passive"))
      (node (ref "LED230") (pin "1") (pinfunction "VDD_1") (pintype "passive"))
      (node (ref "LED231") (pin "1") (pinfunction "VDD_1") (pintype "passive"))
      (node (ref "LED232") (pin "1") (pinfunction "VDD_1") (pintype "passive"))
      (node (ref "LED233") (pin "1") (pinfunction "VDD_1") (pintype "passive"))
      (node (ref "LED234") (pin "1") (pinfunction "VDD_1") (pintype "passive"))
      (node (ref "LED235") (pin "1") (pinfunction "VDD_1") (pintype "passive"))
      (node (ref "LED236") (pin "1") (pinfunction "VDD_1") (pintype "passive"))
      (node (ref "LED237") (pin "1") (pinfunction "VDD_1") (pintype "passive"))
      (node (ref "LED238") (pin "1") (pinfunction "VDD_1") (pintype "passive"))
      (node (ref "LED239") (pin "1") (pinfunction "VDD_1") (pintype "passive"))
      (node (ref "LED24") (pin "1") (pinfunction "VDD_1") (pintype "passive"))
      (node (ref "LED240") (pin "1") (pinfunction "VDD_1") (pintype "passive"))
      (node (ref "LED241") (pin "1") (pinfunction "VDD_1") (pintype "passive"))
      (node (ref "LED242") (pin "1") (pinfunction "VDD_1") (pintype "passive"))
      (node (ref "LED243") (pin "1") (pinfunction "VDD_1") (pintype "passive"))
      (node (ref "LED244") (pin "1") (pinfunction "VDD_1") (pintype "passive"))
      (node (ref "LED245") (pin "1") (pinfunction "VDD_1") (pintype "passive"))
      (node (ref "LED246") (pin "1") (pinfunction "VDD_1") (pintype "passive"))
      (node (ref "LED247") (pin "1") (pinfunction "VDD_1") (pintype "passive"))
      (node (ref "LED248") (pin "1") (pinfunction "VDD_1") (pintype "passive"))
      (node (ref "LED249") (pin "1") (pinfunction "VDD_1") (pintype "passive"))
      (node (ref "LED25") (pin "1") (pinfunction "VDD_1") (pintype "passive"))
      (node (ref "LED250") (pin "1") (pinfunction "VDD_1") (pintype "passive"))
      (node (ref "LED251") (pin "1") (pinfunction "VDD_1") (pintype "passive"))
      (node (ref "LED252") (pin "1") (pinfunction "VDD_1") (pintype "passive"))
      (node (ref "LED253") (pin "1") (pinfunction "VDD_1") (pintype "passive"))
      (node (ref "LED254") (pin "1") (pinfunction "VDD_1") (pintype "passive"))
      (node (ref "LED255") (pin "1") (pinfunction "VDD_1") (pintype "passive"))
      (node (ref "LED256") (pin "1") (pinfunction "VDD_1") (pintype "passive"))
      (node (ref "LED26") (pin "1") (pinfunction "VDD_1") (pintype "passive"))
      (node (ref "LED27") (pin "1") (pinfunction "VDD_1") (pintype "passive"))
      (node (ref "LED28") (pin "1") (pinfunction "VDD_1") (pintype "passive"))
      (node (ref "LED29") (pin "1") (pinfunction "VDD_1") (pintype "passive"))
      (node (ref "LED3") (pin "1") (pinfunction "VDD_1") (pintype "passive"))
      (node (ref "LED30") (pin "1") (pinfunction "VDD_1") (pintype "passive"))
      (node (ref "LED31") (pin "1") (pinfunction "VDD_1") (pintype "passive"))
      (node (ref "LED32") (pin "1") (pinfunction "VDD_1") (pintype "passive"))
      (node (ref "LED33") (pin "1") (pinfunction "VDD_1") (pintype "passive"))
      (node (ref "LED34") (pin "1") (pinfunction "VDD_1") (pintype "passive"))
      (node (ref "LED35") (pin "1") (pinfunction "VDD_1") (pintype "passive"))
      (node (ref "LED36") (pin "1") (pinfunction "VDD_1") (pintype "passive"))
      (node (ref "LED37") (pin "1") (pinfunction "VDD_1") (pintype "passive"))
      (node (ref "LED38") (pin "1") (pinfunction "VDD_1") (pintype "passive"))
      (node (ref "LED39") (pin "1") (pinfunction "VDD_1") (pintype "passive"))
      (node (ref "LED4") (pin "1") (pinfunction "VDD_1") (pintype "passive"))
      (node (ref "LED40") (pin "1") (pinfunction "VDD_1") (pintype "passive"))
      (node (ref "LED41") (pin "1") (pinfunction "VDD_1") (pintype "passive"))
      (node (ref "LED42") (pin "1") (pinfunction "VDD_1") (pintype "passive"))
      (node (ref "LED43") (pin "1") (pinfunction "VDD_1") (pintype "passive"))
      (node (ref "LED44") (pin "1") (pinfunction "VDD_1") (pintype "passive"))
      (node (ref "LED45") (pin "1") (pinfunction "VDD_1") (pintype "passive"))
      (node (ref "LED46") (pin "1") (pinfunction "VDD_1") (pintype "passive"))
      (node (ref "LED47") (pin "1") (pinfunction "VDD_1") (pintype "passive"))
      (node (ref "LED48") (pin "1") (pinfunction "VDD_1") (pintype "passive"))
      (node (ref "LED49") (pin "1") (pinfunction "VDD_1") (pintype "passive"))
      (node (ref "LED5") (pin "1") (pinfunction "VDD_1") (pintype "passive"))
      (node (ref "LED50") (pin "1") (pinfunction "VDD_1") (pintype "passive"))
      (node (ref "LED51") (pin "1") (pinfunction "VDD_1") (pintype "passive"))
      (node (ref "LED52") (pin "1") (pinfunction "VDD_1") (pintype "passive"))
      (node (ref "LED53") (pin "1") (pinfunction "VDD_1") (pintype "passive"))
      (node (ref "LED54") (pin "1") (pinfunction "VDD_1") (pintype "passive"))
      (node (ref "LED55") (pin "1") (pinfunction "VDD_1") (pintype "passive"))
      (node (ref "LED56") (pin "1") (pinfunction "VDD_1") (pintype "passive"))
      (node (ref "LED57") (pin "1") (pinfunction "VDD_1") (pintype "passive"))
      (node (ref "LED58") (pin "1") (pinfunction "VDD_1") (pintype "passive"))
      (node (ref "LED59") (pin "1") (pinfunction "VDD_1") (pintype "passive"))
      (node (ref "LED6") (pin "1") (pinfunction "VDD_1") (pintype "passive"))
      (node (ref "LED60") (pin "1") (pinfunction "VDD_1") (pintype "passive"))
      (node (ref "LED61") (pin "1") (pinfunction "VDD_1") (pintype "passive"))
      (node (ref "LED62") (pin "1") (pinfunction "VDD_1") (pintype "passive"))
      (node (ref "LED63") (pin "1") (pinfunction "VDD_1") (pintype "passive"))
      (node (ref "LED64") (pin "1") (pinfunction "VDD_1") (pintype "passive"))
      (node (ref "LED65") (pin "1") (pinfunction "VDD_1") (pintype "passive"))
      (node (ref "LED66") (pin "1") (pinfunction "VDD_1") (pintype "passive"))
      (node (ref "LED67") (pin "1") (pinfunction "VDD_1") (pintype "passive"))
      (node (ref "LED68") (pin "1") (pinfunction "VDD_1") (pintype "passive"))
      (node (ref "LED69") (pin "1") (pinfunction "VDD_1") (pintype "passive"))
      (node (ref "LED7") (pin "1") (pinfunction "VDD_1") (pintype "passive"))
      (node (ref "LED70") (pin "1") (pinfunction "VDD_1") (pintype "passive"))
      (node (ref "LED71") (pin "1") (pinfunction "VDD_1") (pintype "passive"))
      (node (ref "LED72") (pin "1") (pinfunction "VDD_1") (pintype "passive"))
      (node (ref "LED73") (pin "1") (pinfunction "VDD_1") (pintype "passive"))
      (node (ref "LED74") (pin "1") (pinfunction "VDD_1") (pintype "passive"))
      (node (ref "LED75") (pin "1") (pinfunction "VDD_1") (pintype "passive"))
      (node (ref "LED76") (pin "1") (pinfunction "VDD_1") (pintype "passive"))
      (node (ref "LED77") (pin "1") (pinfunction "VDD_1") (pintype "passive"))
      (node (ref "LED78") (pin "1") (pinfunction "VDD_1") (pintype "passive"))
      (node (ref "LED79") (pin "1") (pinfunction "VDD_1") (pintype "passive"))
      (node (ref "LED8") (pin "1") (pinfunction "VDD_1") (pintype "passive"))
      (node (ref "LED80") (pin "1") (pinfunction "VDD_1") (pintype "passive"))
      (node (ref "LED81") (pin "1") (pinfunction "VDD_1") (pintype "passive"))
      (node (ref "LED82") (pin "1") (pinfunction "VDD_1") (pintype "passive"))
      (node (ref "LED83") (pin "1") (pinfunction "VDD_1") (pintype "passive"))
      (node (ref "LED84") (pin "1") (pinfunction "VDD_1") (pintype "passive"))
      (node (ref "LED85") (pin "1") (pinfunction "VDD_1") (pintype "passive"))
      (node (ref "LED86") (pin "1") (pinfunction "VDD_1") (pintype "passive"))
      (node (ref "LED87") (pin "1") (pinfunction "VDD_1") (pintype "passive"))
      (node (ref "LED88") (pin "1") (pinfunction "VDD_1") (pintype "passive"))
      (node (ref "LED89") (pin "1") (pinfunction "VDD_1") (pintype "passive"))
      (node (ref "LED9") (pin "1") (pinfunction "VDD_1") (pintype "passive"))
      (node (ref "LED90") (pin "1") (pinfunction "VDD_1") (pintype "passive"))
      (node (ref "LED91") (pin "1") (pinfunction "VDD_1") (pintype "passive"))
      (node (ref "LED92") (pin "1") (pinfunction "VDD_1") (pintype "passive"))
      (node (ref "LED93") (pin "1") (pinfunction "VDD_1") (pintype "passive"))
      (node (ref "LED94") (pin "1") (pinfunction "VDD_1") (pintype "passive"))
      (node (ref "LED95") (pin "1") (pinfunction "VDD_1") (pintype "passive"))
      (node (ref "LED96") (pin "1") (pinfunction "VDD_1") (pintype "passive"))
      (node (ref "LED97") (pin "1") (pinfunction "VDD_1") (pintype "passive"))
      (node (ref "LED98") (pin "1") (pinfunction "VDD_1") (pintype "passive"))
      (node (ref "LED99") (pin "1") (pinfunction "VDD_1") (pintype "passive"))
    )
    (net (code "259") (name "unconnected-(LED256-DOUT-Pad2)") (class "Default")
      (node (ref "LED256") (pin "2") (pinfunction "DOUT_2") (pintype "passive"))
    )
  )
)
